# board.net
KiCad netlist of a schematic drawn in EAGLE
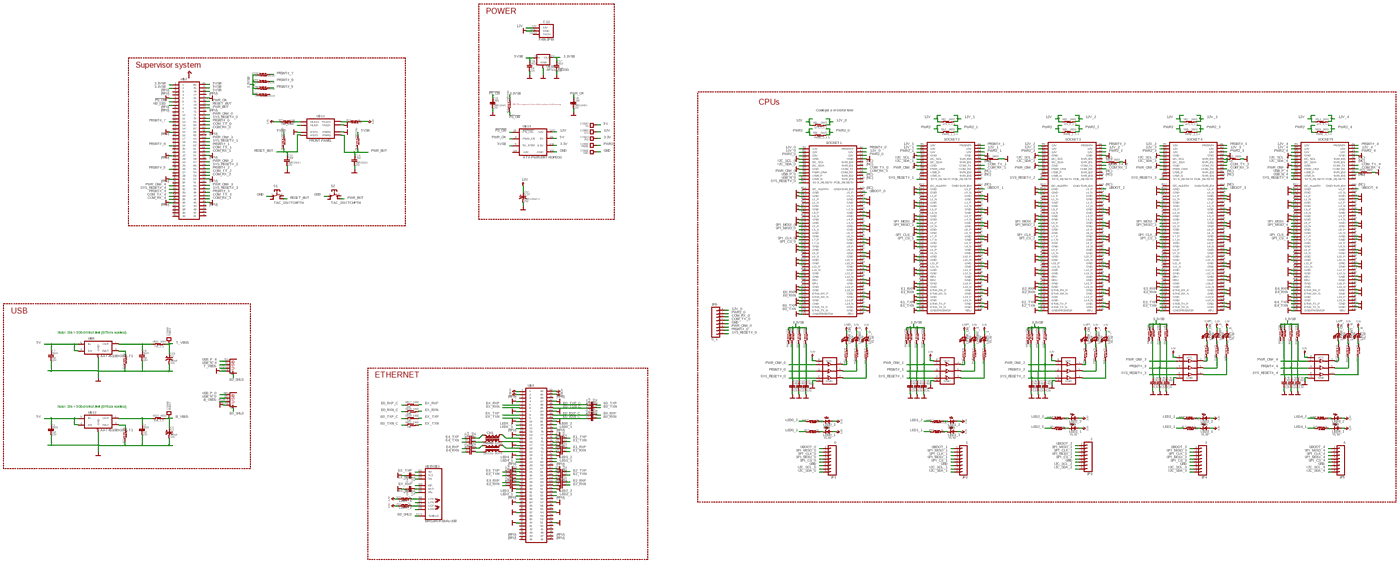
[diagram p0: schematic, sheet 1, overview]
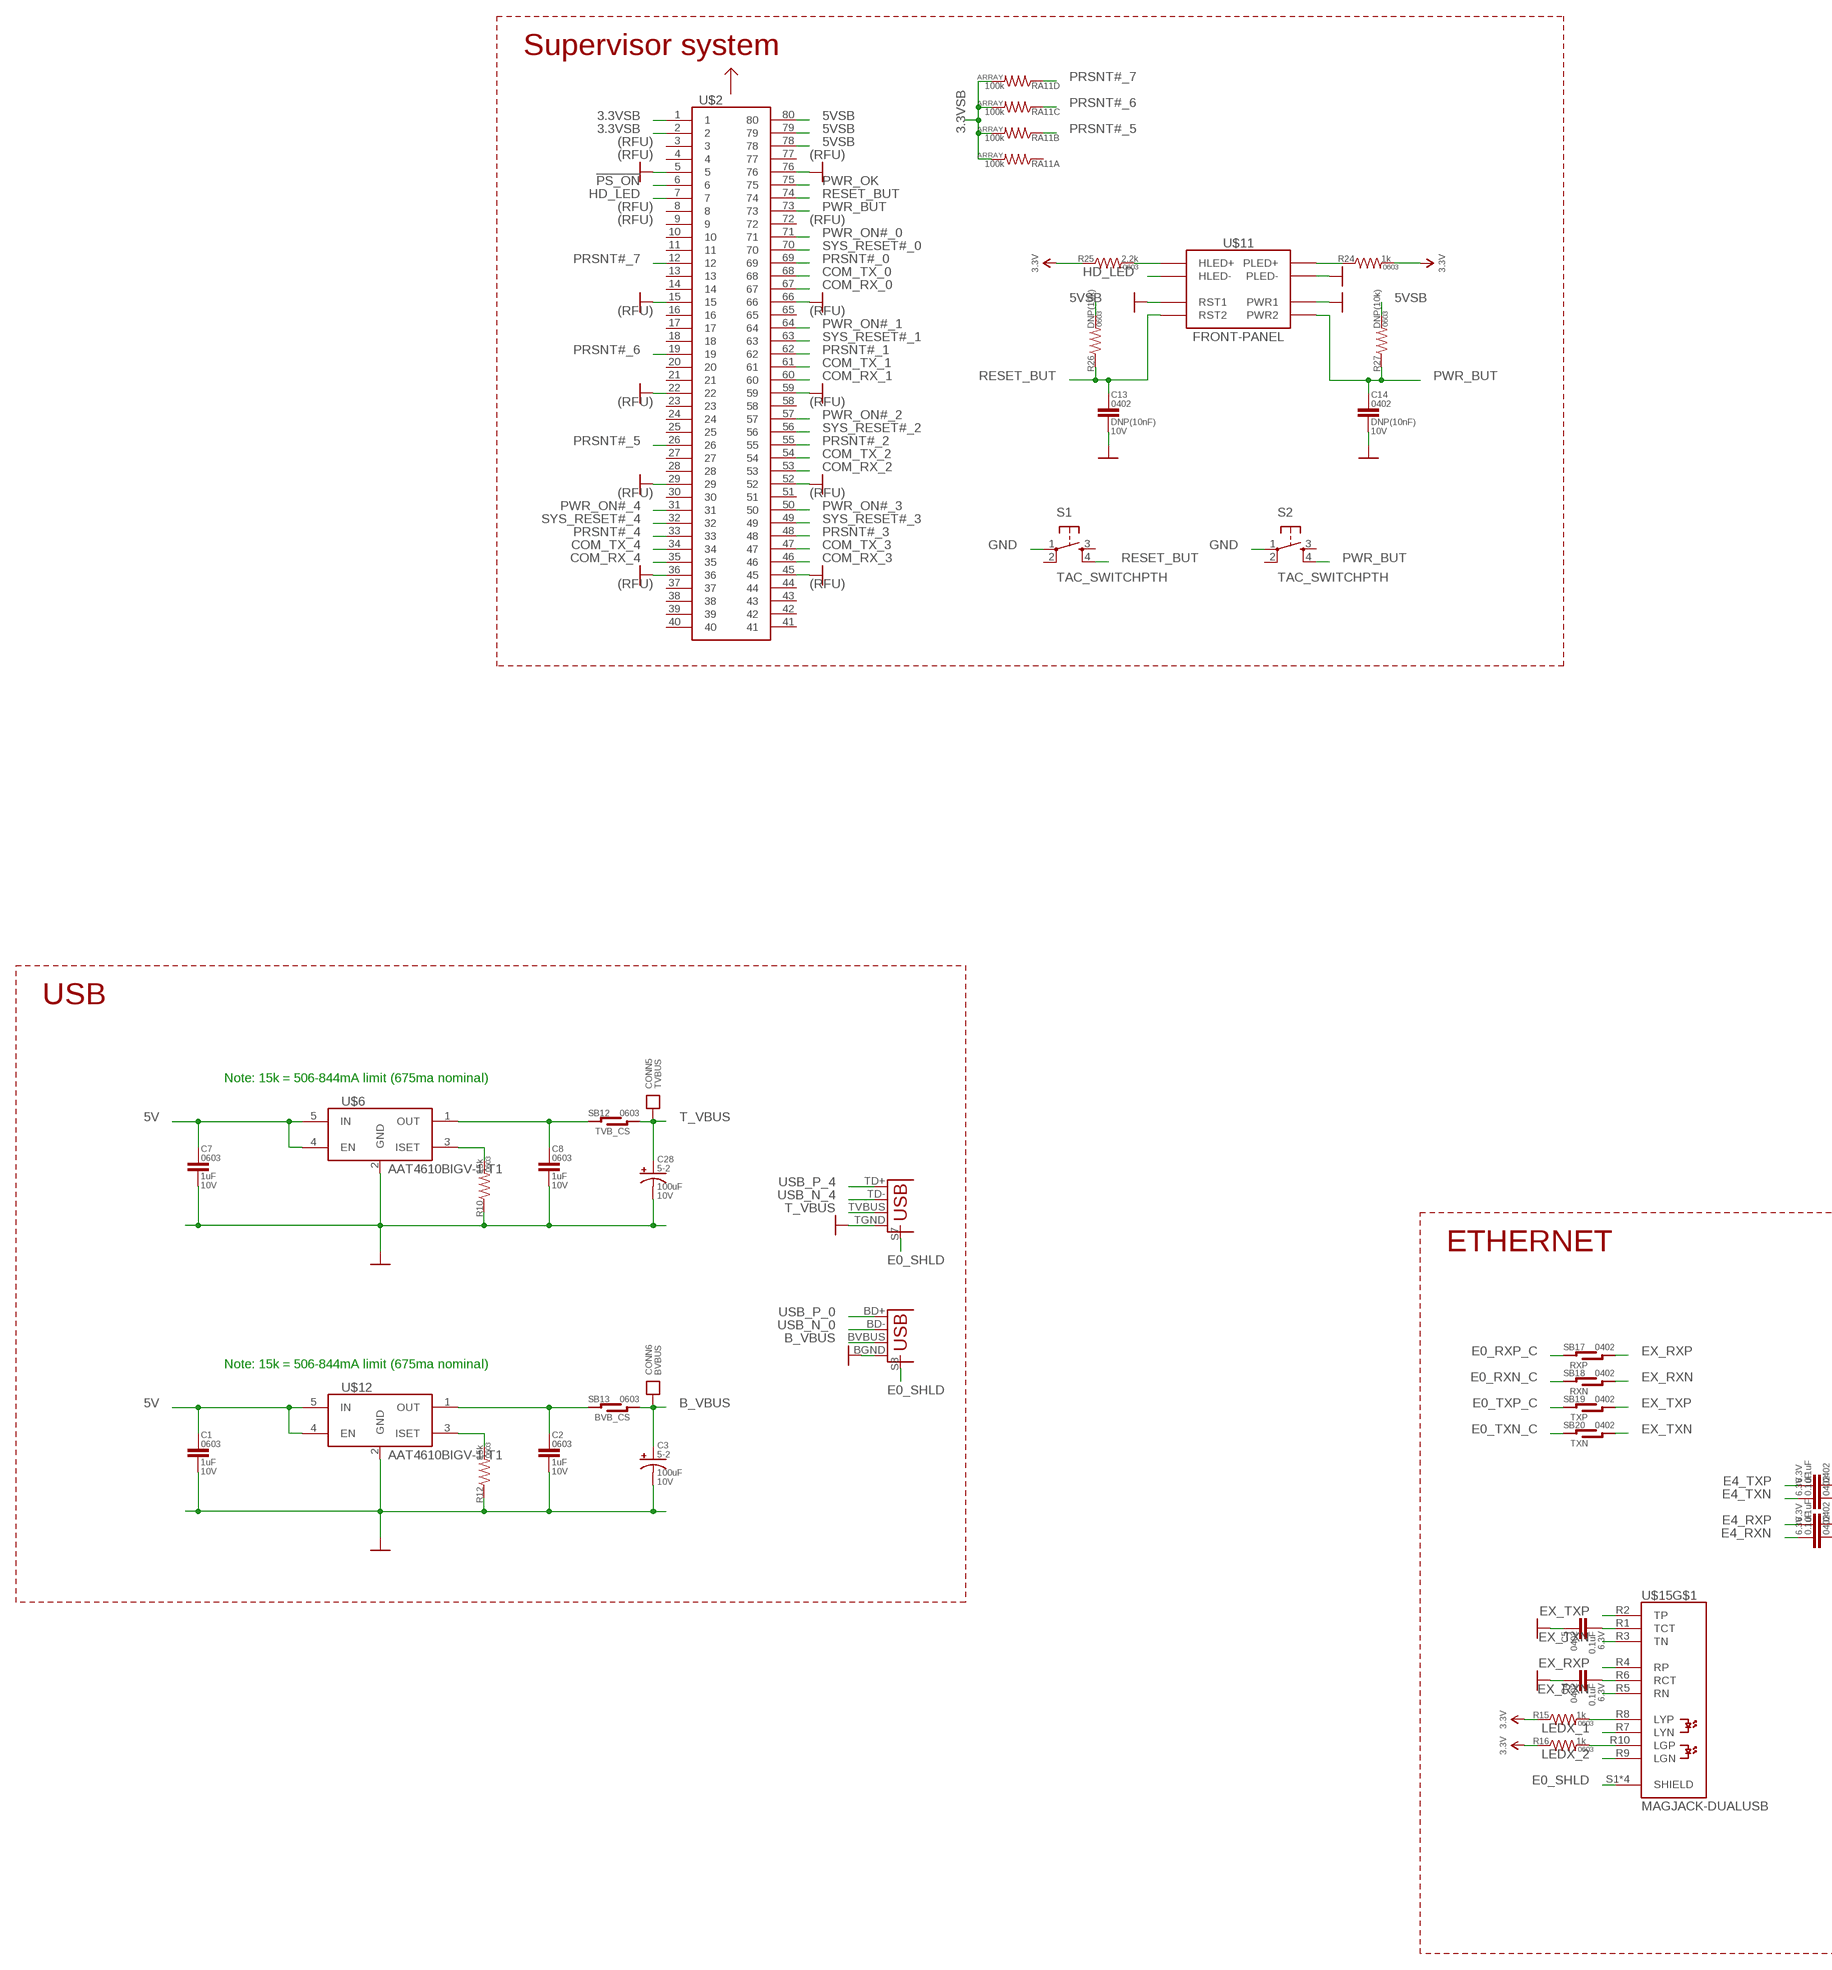
[diagram p1: schematic, sheet 1, part 1 of 4]
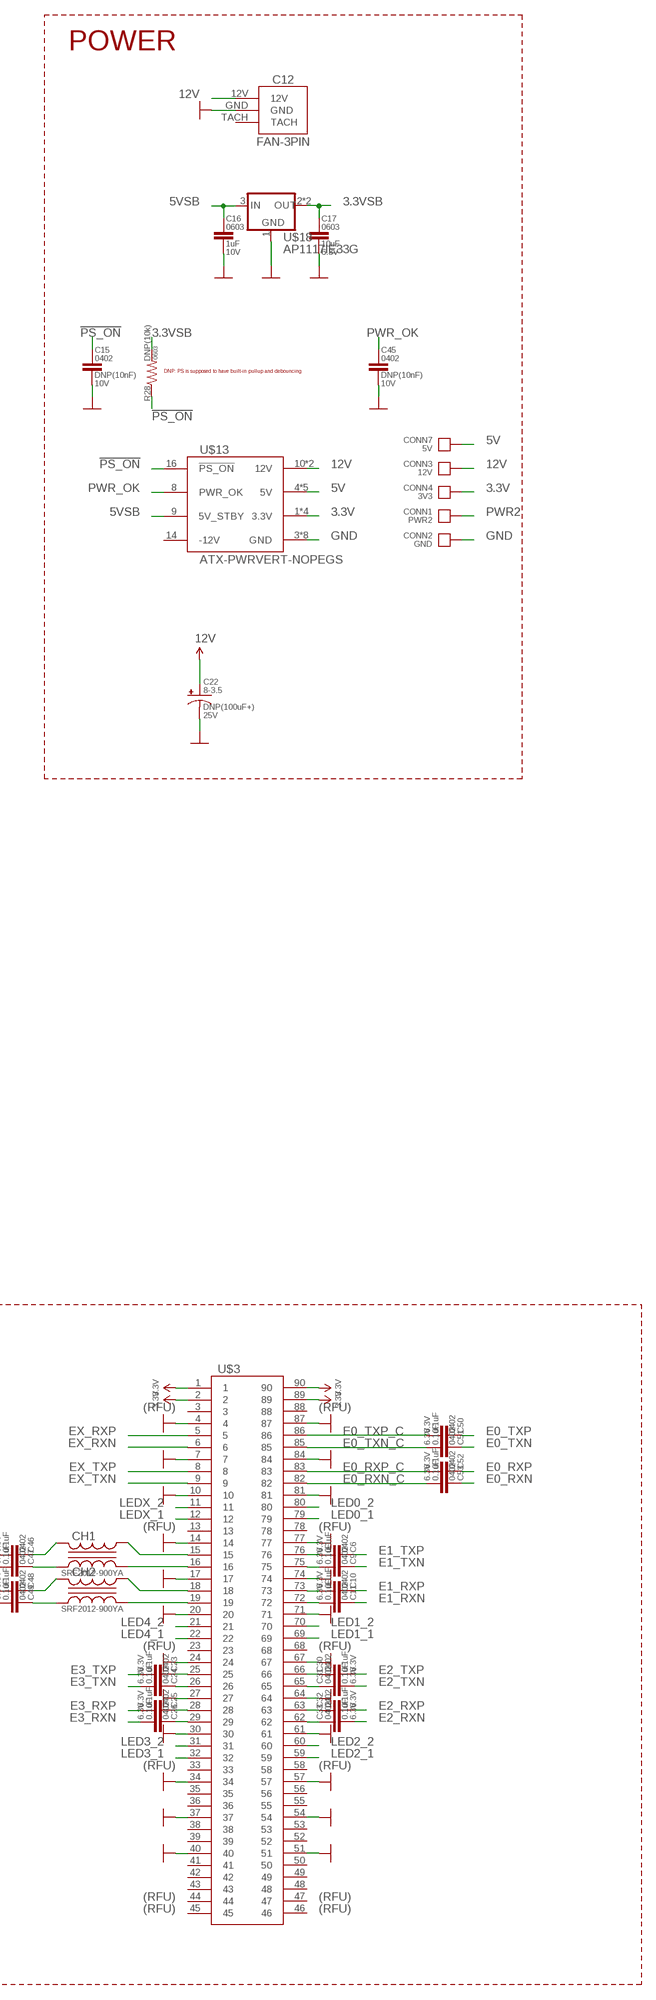
[diagram p2: schematic, sheet 1, part 2 of 4]
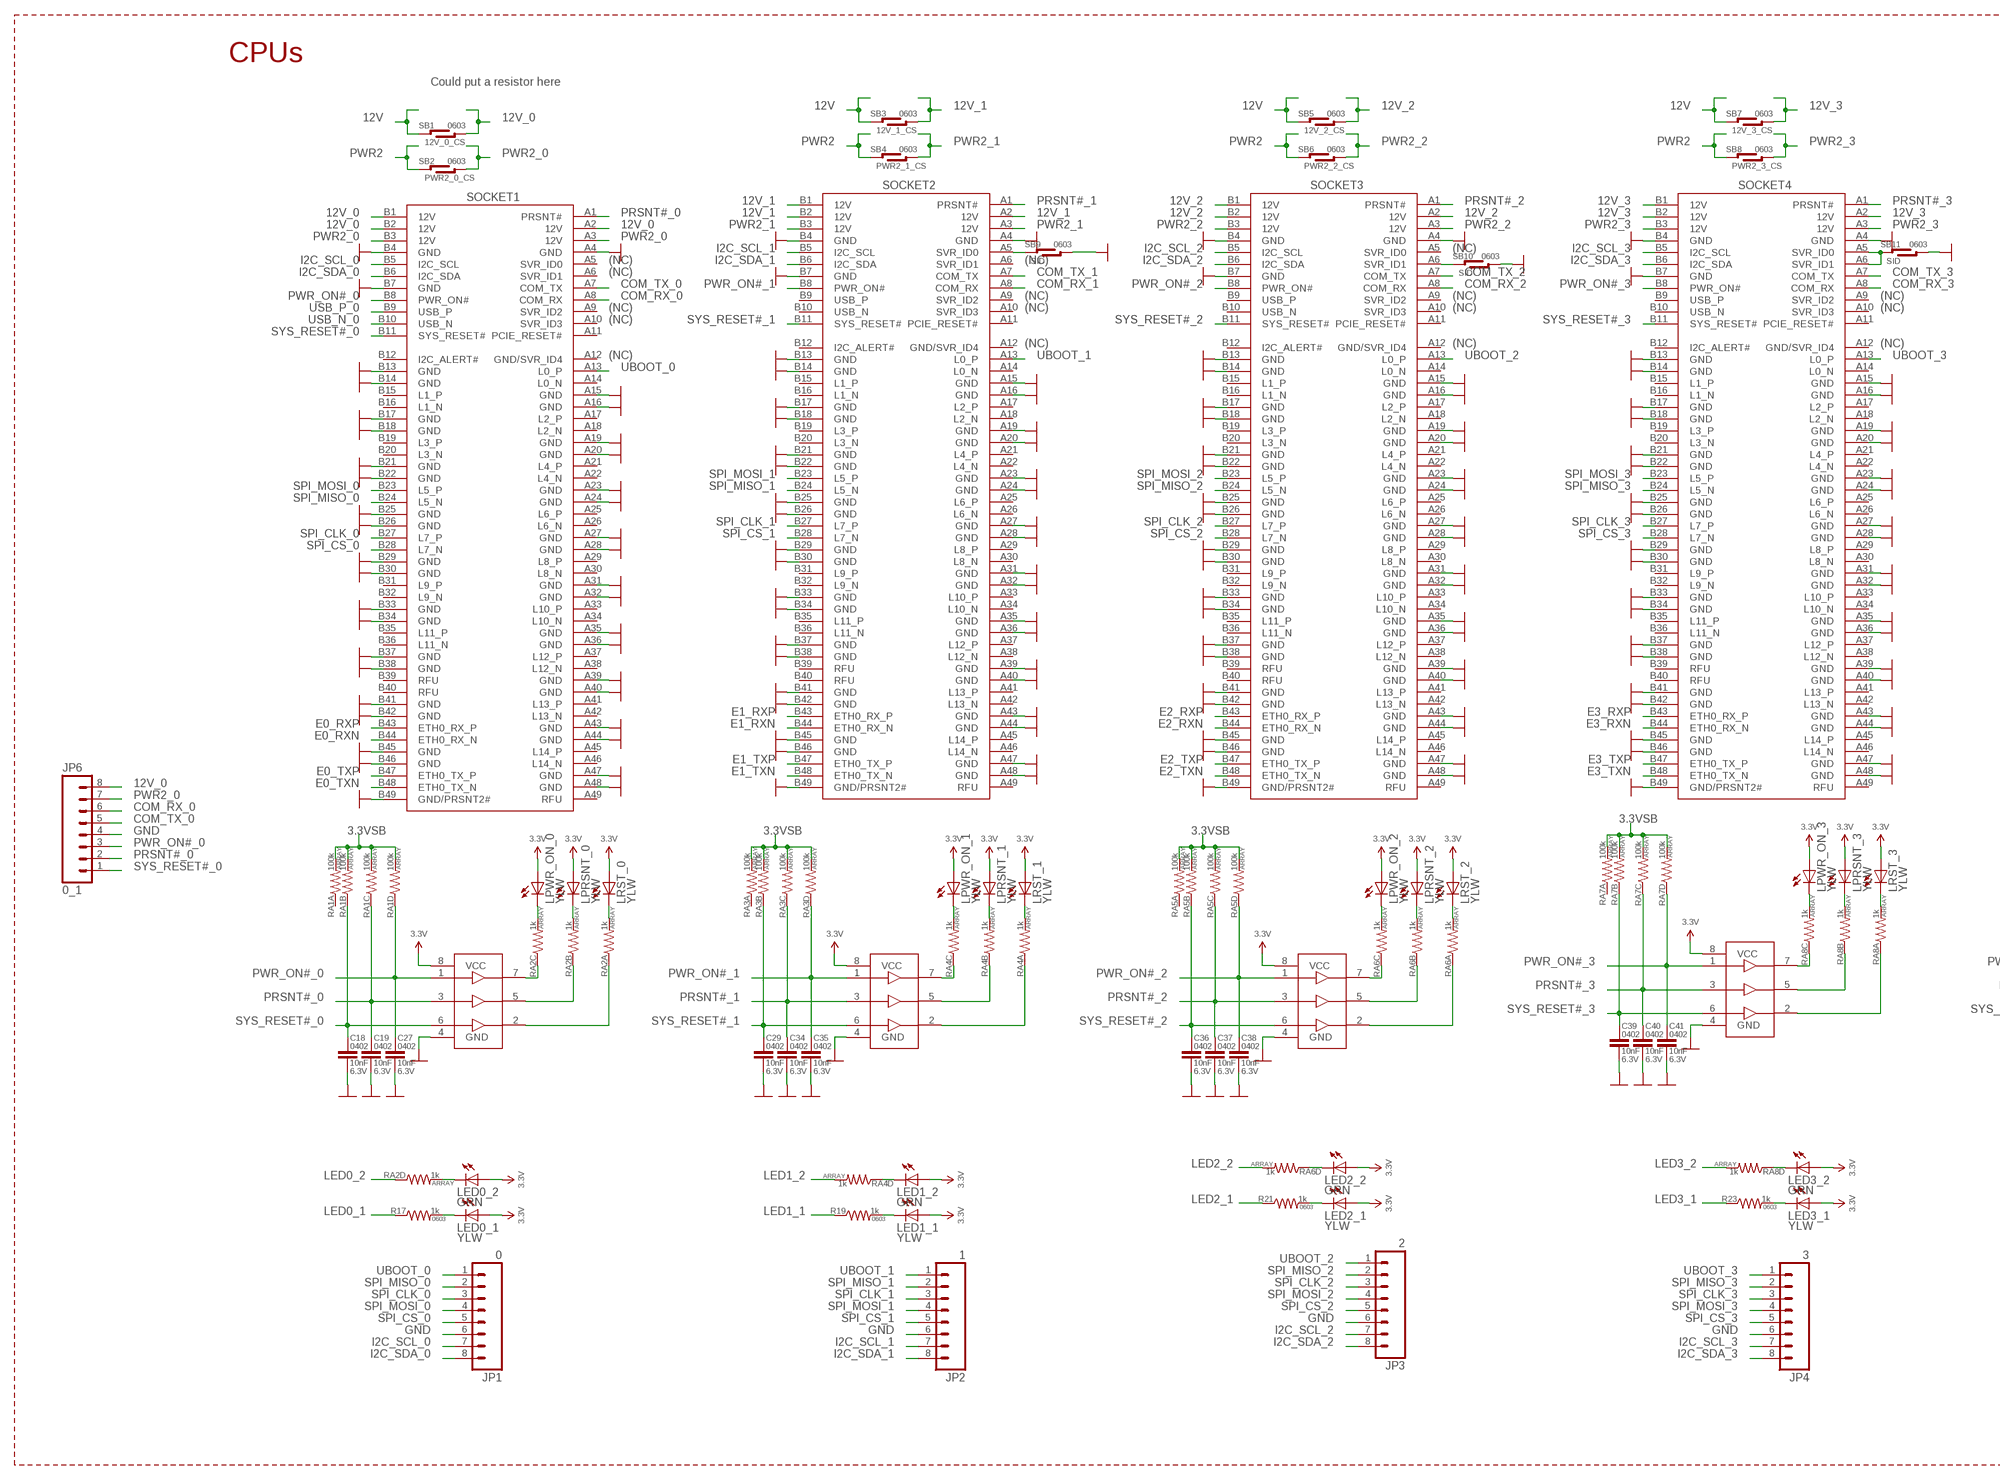
[diagram p3: schematic, sheet 1, part 3 of 4]
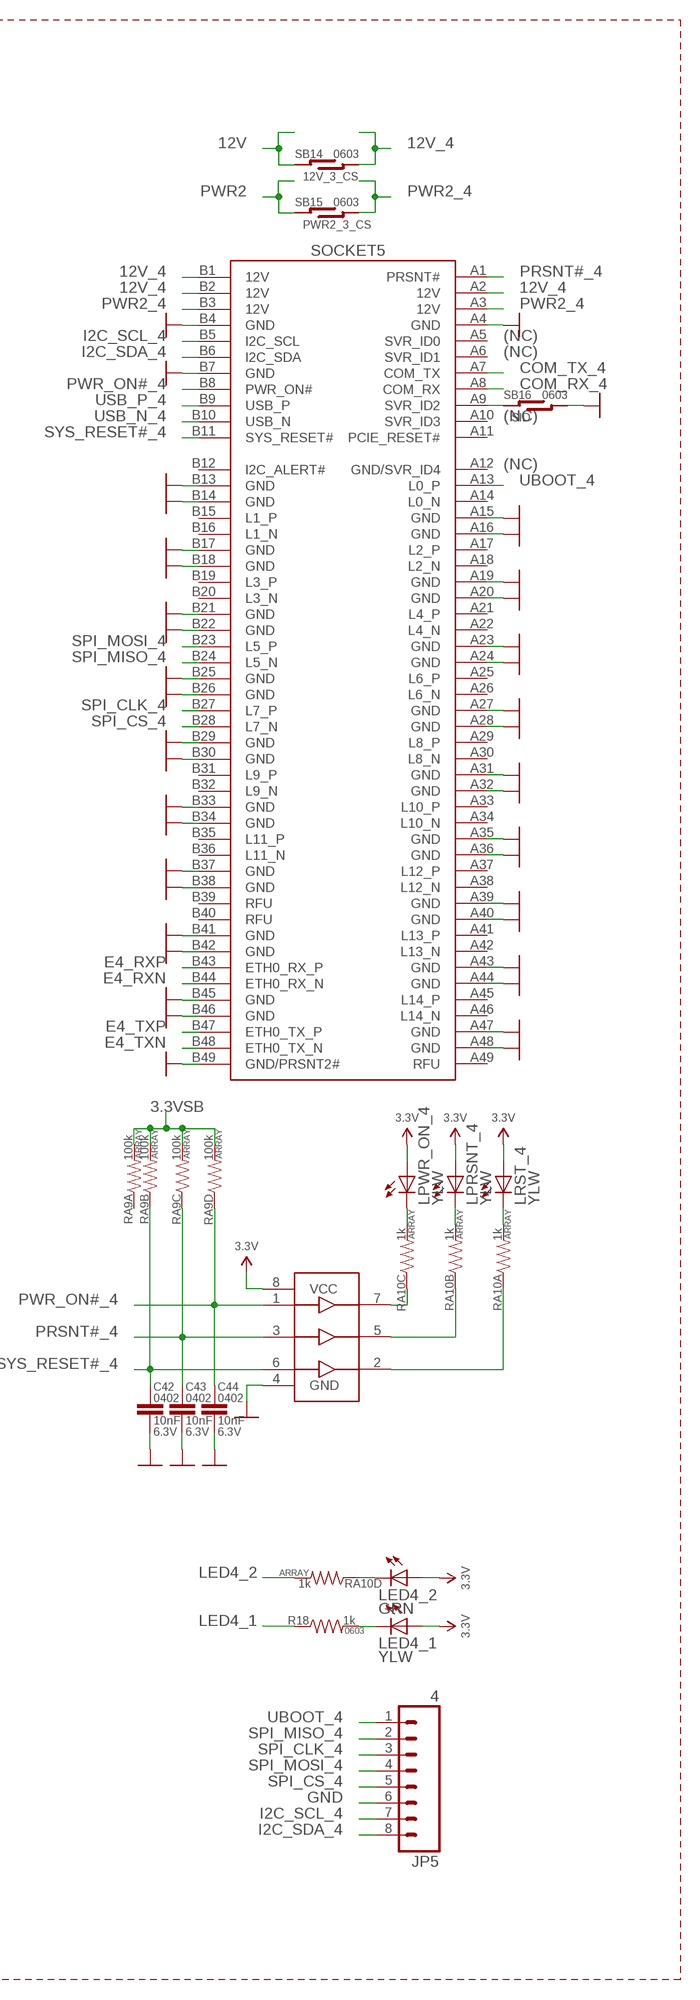
[diagram p4: schematic, sheet 1, part 4 of 4]

(export (version "E")
  (design (tool "Eeschema 10.0.6"))
  (components
    (comp (ref "C1")
      (value "1uF")
      (footprint "eagle-import:0603-CAP")
      (fields (field (name "VOLTAGE") "6.3V") (field (name "VOLTAGE_1") "10V"))
      (libsource (lib "eagle-import") (part "CAP0603"))
    )
    (comp (ref "C2")
      (value "1uF")
      (footprint "eagle-import:0603-CAP")
      (fields (field (name "VOLTAGE") "6.3V") (field (name "VOLTAGE_1") "10V"))
      (libsource (lib "eagle-import") (part "CAP0603"))
    )
    (comp (ref "C3")
      (value "100uF")
      (footprint "eagle-import:CAP-5-2")
      (fields (field (name "VOLTAGE") "6.3V") (field (name "VOLTAGE_1") "10V"))
      (libsource (lib "eagle-import") (part "CAP_POLPTH-5-2"))
    )
    (comp (ref "C4")
      (value "0.1uF")
      (footprint "eagle-import:0402-CAP")
      (fields (field (name "VOLTAGE") "6.3V"))
      (libsource (lib "eagle-import") (part "CAP0402-CAP"))
    )
    (comp (ref "C5")
      (value "0.1uF")
      (footprint "eagle-import:0402-CAP")
      (fields (field (name "VOLTAGE") "6.3V"))
      (libsource (lib "eagle-import") (part "CAP0402-CAP"))
    )
    (comp (ref "C6")
      (value "0.1uF")
      (footprint "eagle-import:0402-CAP")
      (fields (field (name "VOLTAGE") "6.3V"))
      (libsource (lib "eagle-import") (part "CAP0402-CAP"))
    )
    (comp (ref "C7")
      (value "1uF")
      (footprint "eagle-import:0603-CAP")
      (fields (field (name "VOLTAGE") "6.3V") (field (name "VOLTAGE_1") "10V"))
      (libsource (lib "eagle-import") (part "CAP0603"))
    )
    (comp (ref "C8")
      (value "1uF")
      (footprint "eagle-import:0603-CAP")
      (fields (field (name "VOLTAGE") "6.3V") (field (name "VOLTAGE_1") "10V"))
      (libsource (lib "eagle-import") (part "CAP0603"))
    )
    (comp (ref "C9")
      (value "0.1uF")
      (footprint "eagle-import:0402-CAP")
      (fields (field (name "VOLTAGE") "6.3V"))
      (libsource (lib "eagle-import") (part "CAP0402-CAP"))
    )
    (comp (ref "C10")
      (value "0.1uF")
      (footprint "eagle-import:0402-CAP")
      (fields (field (name "VOLTAGE") "6.3V"))
      (libsource (lib "eagle-import") (part "CAP0402-CAP"))
    )
    (comp (ref "C11")
      (value "0.1uF")
      (footprint "eagle-import:0402-CAP")
      (fields (field (name "VOLTAGE") "6.3V"))
      (libsource (lib "eagle-import") (part "CAP0402-CAP"))
    )
    (comp (ref "C12")
      (value "FAN-3PIN")
      (footprint "eagle-import:FAN-3PIN")
      (libsource (lib "eagle-import") (part "FAN-3PIN"))
    )
    (comp (ref "C13")
      (value "DNP(10nF)")
      (footprint "eagle-import:0402-CAP")
      (fields (field (name "VOLTAGE") "6.3V") (field (name "VOLTAGE_1") "10V"))
      (libsource (lib "eagle-import") (part "CAP0402-CAP"))
    )
    (comp (ref "C14")
      (value "DNP(10nF)")
      (footprint "eagle-import:0402-CAP")
      (fields (field (name "VOLTAGE") "6.3V") (field (name "VOLTAGE_1") "10V"))
      (libsource (lib "eagle-import") (part "CAP0402-CAP"))
    )
    (comp (ref "C15")
      (value "DNP(10nF)")
      (footprint "eagle-import:0402-CAP")
      (fields (field (name "VOLTAGE") "6.3V") (field (name "VOLTAGE_1") "10V"))
      (libsource (lib "eagle-import") (part "CAP0402-CAP"))
    )
    (comp (ref "C16")
      (value "1uF")
      (footprint "eagle-import:0603-CAP")
      (fields (field (name "VOLTAGE") "6.3V") (field (name "VOLTAGE_1") "10V"))
      (libsource (lib "eagle-import") (part "CAP0603"))
    )
    (comp (ref "C17")
      (value "10uF")
      (footprint "eagle-import:0603-CAP")
      (fields (field (name "VOLTAGE") "6.3V"))
      (libsource (lib "eagle-import") (part "CAP0603"))
    )
    (comp (ref "C18")
      (value "10nF")
      (footprint "eagle-import:0402-CAP")
      (fields (field (name "VOLTAGE") "6.3V"))
      (libsource (lib "eagle-import") (part "CAP0402-CAP"))
    )
    (comp (ref "C19")
      (value "10nF")
      (footprint "eagle-import:0402-CAP")
      (fields (field (name "VOLTAGE") "6.3V"))
      (libsource (lib "eagle-import") (part "CAP0402-CAP"))
    )
    (comp (ref "C22")
      (value "DNP(100uF+)")
      (footprint "eagle-import:CAP-8-3.5")
      (fields (field (name "VOLTAGE") "6.3V") (field (name "VOLTAGE_1") "25V"))
      (libsource (lib "eagle-import") (part "CAP_POLPTH-8-3.5"))
    )
    (comp (ref "C23")
      (value "0.1uF")
      (footprint "eagle-import:0402-CAP")
      (fields (field (name "VOLTAGE") "6.3V"))
      (libsource (lib "eagle-import") (part "CAP0402-CAP"))
    )
    (comp (ref "C24")
      (value "0.1uF")
      (footprint "eagle-import:0402-CAP")
      (fields (field (name "VOLTAGE") "6.3V"))
      (libsource (lib "eagle-import") (part "CAP0402-CAP"))
    )
    (comp (ref "C25")
      (value "0.1uF")
      (footprint "eagle-import:0402-CAP")
      (fields (field (name "VOLTAGE") "6.3V"))
      (libsource (lib "eagle-import") (part "CAP0402-CAP"))
    )
    (comp (ref "C26")
      (value "0.1uF")
      (footprint "eagle-import:0402-CAP")
      (fields (field (name "VOLTAGE") "6.3V"))
      (libsource (lib "eagle-import") (part "CAP0402-CAP"))
    )
    (comp (ref "C27")
      (value "10nF")
      (footprint "eagle-import:0402-CAP")
      (fields (field (name "VOLTAGE") "6.3V"))
      (libsource (lib "eagle-import") (part "CAP0402-CAP"))
    )
    (comp (ref "C28")
      (value "100uF")
      (footprint "eagle-import:CAP-5-2")
      (fields (field (name "VOLTAGE") "6.3V") (field (name "VOLTAGE_1") "10V"))
      (libsource (lib "eagle-import") (part "CAP_POLPTH-5-2"))
    )
    (comp (ref "C29")
      (value "10nF")
      (footprint "eagle-import:0402-CAP")
      (fields (field (name "VOLTAGE") "6.3V"))
      (libsource (lib "eagle-import") (part "CAP0402-CAP"))
    )
    (comp (ref "C30")
      (value "0.1uF")
      (footprint "eagle-import:0402-CAP")
      (fields (field (name "VOLTAGE") "6.3V"))
      (libsource (lib "eagle-import") (part "CAP0402-CAP"))
    )
    (comp (ref "C31")
      (value "0.1uF")
      (footprint "eagle-import:0402-CAP")
      (fields (field (name "VOLTAGE") "6.3V"))
      (libsource (lib "eagle-import") (part "CAP0402-CAP"))
    )
    (comp (ref "C32")
      (value "0.1uF")
      (footprint "eagle-import:0402-CAP")
      (fields (field (name "VOLTAGE") "6.3V"))
      (libsource (lib "eagle-import") (part "CAP0402-CAP"))
    )
    (comp (ref "C33")
      (value "0.1uF")
      (footprint "eagle-import:0402-CAP")
      (fields (field (name "VOLTAGE") "6.3V"))
      (libsource (lib "eagle-import") (part "CAP0402-CAP"))
    )
    (comp (ref "C34")
      (value "10nF")
      (footprint "eagle-import:0402-CAP")
      (fields (field (name "VOLTAGE") "6.3V"))
      (libsource (lib "eagle-import") (part "CAP0402-CAP"))
    )
    (comp (ref "C35")
      (value "10nF")
      (footprint "eagle-import:0402-CAP")
      (fields (field (name "VOLTAGE") "6.3V"))
      (libsource (lib "eagle-import") (part "CAP0402-CAP"))
    )
    (comp (ref "C36")
      (value "10nF")
      (footprint "eagle-import:0402-CAP")
      (fields (field (name "VOLTAGE") "6.3V"))
      (libsource (lib "eagle-import") (part "CAP0402-CAP"))
    )
    (comp (ref "C37")
      (value "10nF")
      (footprint "eagle-import:0402-CAP")
      (fields (field (name "VOLTAGE") "6.3V"))
      (libsource (lib "eagle-import") (part "CAP0402-CAP"))
    )
    (comp (ref "C38")
      (value "10nF")
      (footprint "eagle-import:0402-CAP")
      (fields (field (name "VOLTAGE") "6.3V"))
      (libsource (lib "eagle-import") (part "CAP0402-CAP"))
    )
    (comp (ref "C39")
      (value "10nF")
      (footprint "eagle-import:0402-CAP")
      (fields (field (name "VOLTAGE") "6.3V"))
      (libsource (lib "eagle-import") (part "CAP0402-CAP"))
    )
    (comp (ref "C40")
      (value "10nF")
      (footprint "eagle-import:0402-CAP")
      (fields (field (name "VOLTAGE") "6.3V"))
      (libsource (lib "eagle-import") (part "CAP0402-CAP"))
    )
    (comp (ref "C41")
      (value "10nF")
      (footprint "eagle-import:0402-CAP")
      (fields (field (name "VOLTAGE") "6.3V"))
      (libsource (lib "eagle-import") (part "CAP0402-CAP"))
    )
    (comp (ref "C42")
      (value "10nF")
      (footprint "eagle-import:0402-CAP")
      (fields (field (name "VOLTAGE") "6.3V"))
      (libsource (lib "eagle-import") (part "CAP0402-CAP"))
    )
    (comp (ref "C43")
      (value "10nF")
      (footprint "eagle-import:0402-CAP")
      (fields (field (name "VOLTAGE") "6.3V"))
      (libsource (lib "eagle-import") (part "CAP0402-CAP"))
    )
    (comp (ref "C44")
      (value "10nF")
      (footprint "eagle-import:0402-CAP")
      (fields (field (name "VOLTAGE") "6.3V"))
      (libsource (lib "eagle-import") (part "CAP0402-CAP"))
    )
    (comp (ref "C45")
      (value "DNP(10nF)")
      (footprint "eagle-import:0402-CAP")
      (fields (field (name "VOLTAGE") "6.3V") (field (name "VOLTAGE_1") "10V"))
      (libsource (lib "eagle-import") (part "CAP0402-CAP"))
    )
    (comp (ref "C46")
      (value "0.1uF")
      (footprint "eagle-import:0402-CAP")
      (fields (field (name "VOLTAGE") "6.3V"))
      (libsource (lib "eagle-import") (part "CAP0402-CAP"))
    )
    (comp (ref "C47")
      (value "0.1uF")
      (footprint "eagle-import:0402-CAP")
      (fields (field (name "VOLTAGE") "6.3V"))
      (libsource (lib "eagle-import") (part "CAP0402-CAP"))
    )
    (comp (ref "C48")
      (value "0.1uF")
      (footprint "eagle-import:0402-CAP")
      (fields (field (name "VOLTAGE") "6.3V"))
      (libsource (lib "eagle-import") (part "CAP0402-CAP"))
    )
    (comp (ref "C49")
      (value "0.1uF")
      (footprint "eagle-import:0402-CAP")
      (fields (field (name "VOLTAGE") "6.3V"))
      (libsource (lib "eagle-import") (part "CAP0402-CAP"))
    )
    (comp (ref "C50")
      (value "0.1uF")
      (footprint "eagle-import:0402-CAP")
      (fields (field (name "VOLTAGE") "6.3V"))
      (libsource (lib "eagle-import") (part "CAP0402-CAP"))
    )
    (comp (ref "C51")
      (value "0.1uF")
      (footprint "eagle-import:0402-CAP")
      (fields (field (name "VOLTAGE") "6.3V"))
      (libsource (lib "eagle-import") (part "CAP0402-CAP"))
    )
    (comp (ref "C52")
      (value "0.1uF")
      (footprint "eagle-import:0402-CAP")
      (fields (field (name "VOLTAGE") "6.3V"))
      (libsource (lib "eagle-import") (part "CAP0402-CAP"))
    )
    (comp (ref "C53")
      (value "0.1uF")
      (footprint "eagle-import:0402-CAP")
      (fields (field (name "VOLTAGE") "6.3V"))
      (libsource (lib "eagle-import") (part "CAP0402-CAP"))
    )
    (comp (ref "CH1")
      (value "SRF2012-900YA")
      (footprint "eagle-import:SRF2012A")
      (libsource (lib "eagle-import") (part "COMMON_MODE_CHOKE"))
    )
    (comp (ref "CH2")
      (value "SRF2012-900YA")
      (footprint "eagle-import:SRF2012A")
      (libsource (lib "eagle-import") (part "COMMON_MODE_CHOKE"))
    )
    (comp (ref "CONN1")
      (value "PWR2")
      (footprint "eagle-import:HOLE_18AWG")
      (libsource (lib "eagle-import") (part "CONNECTOR18AWG"))
    )
    (comp (ref "CONN2")
      (value "GND")
      (footprint "eagle-import:HOLE_18AWG")
      (libsource (lib "eagle-import") (part "CONNECTOR18AWG"))
    )
    (comp (ref "CONN3")
      (value "12V")
      (footprint "eagle-import:HOLE_18AWG")
      (libsource (lib "eagle-import") (part "CONNECTOR18AWG"))
    )
    (comp (ref "CONN4")
      (value "3V3")
      (footprint "eagle-import:HOLE_18AWG")
      (libsource (lib "eagle-import") (part "CONNECTOR18AWG"))
    )
    (comp (ref "CONN5")
      (value "TVBUS")
      (footprint "eagle-import:HOLE_22AWG")
      (libsource (lib "eagle-import") (part "CONNECTOR22AWG"))
    )
    (comp (ref "CONN6")
      (value "BVBUS")
      (footprint "eagle-import:HOLE_22AWG")
      (libsource (lib "eagle-import") (part "CONNECTOR22AWG"))
    )
    (comp (ref "CONN7")
      (value "5V")
      (footprint "eagle-import:HOLE_18AWG")
      (libsource (lib "eagle-import") (part "CONNECTOR18AWG"))
    )
    (comp (ref "IC1")
      (value "74X3G34")
      (footprint "eagle-import:TSSOP8")
      (libsource (lib "eagle-import") (part "74X3G34"))
    )
    (comp (ref "IC2")
      (value "74X3G34")
      (footprint "eagle-import:TSSOP8")
      (libsource (lib "eagle-import") (part "74X3G34"))
    )
    (comp (ref "IC3")
      (value "74X3G34")
      (footprint "eagle-import:TSSOP8")
      (libsource (lib "eagle-import") (part "74X3G34"))
    )
    (comp (ref "IC4")
      (value "74X3G34")
      (footprint "eagle-import:TSSOP8")
      (libsource (lib "eagle-import") (part "74X3G34"))
    )
    (comp (ref "IC5")
      (value "74X3G34")
      (footprint "eagle-import:TSSOP8")
      (libsource (lib "eagle-import") (part "74X3G34"))
    )
    (comp (ref "JP1")
      (value "0")
      (footprint "eagle-import:1X08")
      (libsource (lib "eagle-import") (part "M081X08"))
    )
    (comp (ref "JP2")
      (value "1")
      (footprint "eagle-import:1X08")
      (libsource (lib "eagle-import") (part "M081X08"))
    )
    (comp (ref "JP3")
      (value "2")
      (footprint "eagle-import:1X08")
      (libsource (lib "eagle-import") (part "M081X08"))
    )
    (comp (ref "JP4")
      (value "3")
      (footprint "eagle-import:1X08")
      (libsource (lib "eagle-import") (part "M081X08"))
    )
    (comp (ref "JP5")
      (value "4")
      (footprint "eagle-import:1X08")
      (libsource (lib "eagle-import") (part "M081X08"))
    )
    (comp (ref "JP6")
      (value "0_1")
      (footprint "eagle-import:1X08")
      (libsource (lib "eagle-import") (part "M081X08"))
    )
    (comp (ref "LED0_1")
      (value "YLW")
      (footprint "eagle-import:0603_LED")
      (libsource (lib "eagle-import") (part "LED0603"))
    )
    (comp (ref "LED0_2")
      (value "GRN")
      (footprint "eagle-import:0603_LED")
      (libsource (lib "eagle-import") (part "LED0603"))
    )
    (comp (ref "LED1_1")
      (value "YLW")
      (footprint "eagle-import:0603_LED")
      (libsource (lib "eagle-import") (part "LED0603"))
    )
    (comp (ref "LED1_2")
      (value "GRN")
      (footprint "eagle-import:0603_LED")
      (libsource (lib "eagle-import") (part "LED0603"))
    )
    (comp (ref "LED2_1")
      (value "YLW")
      (footprint "eagle-import:0603_LED")
      (libsource (lib "eagle-import") (part "LED0603"))
    )
    (comp (ref "LED2_2")
      (value "GRN")
      (footprint "eagle-import:0603_LED")
      (libsource (lib "eagle-import") (part "LED0603"))
    )
    (comp (ref "LED3_1")
      (value "YLW")
      (footprint "eagle-import:0603_LED")
      (libsource (lib "eagle-import") (part "LED0603"))
    )
    (comp (ref "LED3_2")
      (value "GRN")
      (footprint "eagle-import:0603_LED")
      (libsource (lib "eagle-import") (part "LED0603"))
    )
    (comp (ref "LED4_1")
      (value "YLW")
      (footprint "eagle-import:0603_LED")
      (libsource (lib "eagle-import") (part "LED0603"))
    )
    (comp (ref "LED4_2")
      (value "GRN")
      (footprint "eagle-import:0603_LED")
      (libsource (lib "eagle-import") (part "LED0603"))
    )
    (comp (ref "LPRSNT_0")
      (value "YLW")
      (footprint "eagle-import:0603_LED")
      (libsource (lib "eagle-import") (part "LED0603"))
    )
    (comp (ref "LPRSNT_1")
      (value "YLW")
      (footprint "eagle-import:0603_LED")
      (libsource (lib "eagle-import") (part "LED0603"))
    )
    (comp (ref "LPRSNT_2")
      (value "YLW")
      (footprint "eagle-import:0603_LED")
      (libsource (lib "eagle-import") (part "LED0603"))
    )
    (comp (ref "LPRSNT_3")
      (value "YLW")
      (footprint "eagle-import:0603_LED")
      (libsource (lib "eagle-import") (part "LED0603"))
    )
    (comp (ref "LPRSNT_4")
      (value "YLW")
      (footprint "eagle-import:0603_LED")
      (libsource (lib "eagle-import") (part "LED0603"))
    )
    (comp (ref "LPWR_ON_0")
      (value "YLW")
      (footprint "eagle-import:0603_LED")
      (libsource (lib "eagle-import") (part "LED0603"))
    )
    (comp (ref "LPWR_ON_1")
      (value "YLW")
      (footprint "eagle-import:0603_LED")
      (libsource (lib "eagle-import") (part "LED0603"))
    )
    (comp (ref "LPWR_ON_2")
      (value "YLW")
      (footprint "eagle-import:0603_LED")
      (libsource (lib "eagle-import") (part "LED0603"))
    )
    (comp (ref "LPWR_ON_3")
      (value "YLW")
      (footprint "eagle-import:0603_LED")
      (libsource (lib "eagle-import") (part "LED0603"))
    )
    (comp (ref "LPWR_ON_4")
      (value "YLW")
      (footprint "eagle-import:0603_LED")
      (libsource (lib "eagle-import") (part "LED0603"))
    )
    (comp (ref "LRST_0")
      (value "YLW")
      (footprint "eagle-import:0603_LED")
      (libsource (lib "eagle-import") (part "LED0603"))
    )
    (comp (ref "LRST_1")
      (value "YLW")
      (footprint "eagle-import:0603_LED")
      (libsource (lib "eagle-import") (part "LED0603"))
    )
    (comp (ref "LRST_2")
      (value "YLW")
      (footprint "eagle-import:0603_LED")
      (libsource (lib "eagle-import") (part "LED0603"))
    )
    (comp (ref "LRST_3")
      (value "YLW")
      (footprint "eagle-import:0603_LED")
      (libsource (lib "eagle-import") (part "LED0603"))
    )
    (comp (ref "LRST_4")
      (value "YLW")
      (footprint "eagle-import:0603_LED")
      (libsource (lib "eagle-import") (part "LED0603"))
    )
    (comp (ref "R10")
      (value "15k")
      (footprint "eagle-import:0603-RES")
      (libsource (lib "eagle-import") (part "RESISTOR0603"))
    )
    (comp (ref "R12")
      (value "15k")
      (footprint "eagle-import:0603-RES")
      (libsource (lib "eagle-import") (part "RESISTOR0603"))
    )
    (comp (ref "R15")
      (value "1k")
      (footprint "eagle-import:0603-RES")
      (libsource (lib "eagle-import") (part "RESISTOR0603"))
    )
    (comp (ref "R16")
      (value "1k")
      (footprint "eagle-import:0603-RES")
      (libsource (lib "eagle-import") (part "RESISTOR0603"))
    )
    (comp (ref "R17")
      (value "1k")
      (footprint "eagle-import:0603-RES")
      (libsource (lib "eagle-import") (part "RESISTOR0603"))
    )
    (comp (ref "R18")
      (value "1k")
      (footprint "eagle-import:0603-RES")
      (libsource (lib "eagle-import") (part "RESISTOR0603"))
    )
    (comp (ref "R19")
      (value "1k")
      (footprint "eagle-import:0603-RES")
      (libsource (lib "eagle-import") (part "RESISTOR0603"))
    )
    (comp (ref "R21")
      (value "1k")
      (footprint "eagle-import:0603-RES")
      (libsource (lib "eagle-import") (part "RESISTOR0603"))
    )
    (comp (ref "R23")
      (value "1k")
      (footprint "eagle-import:0603-RES")
      (libsource (lib "eagle-import") (part "RESISTOR0603"))
    )
    (comp (ref "R24")
      (value "1k")
      (footprint "eagle-import:0603-RES")
      (libsource (lib "eagle-import") (part "RESISTOR0603"))
    )
    (comp (ref "R25")
      (value "2.2k")
      (footprint "eagle-import:0603-RES")
      (libsource (lib "eagle-import") (part "RESISTOR0603"))
    )
    (comp (ref "R26")
      (value "DNP(10k)")
      (footprint "eagle-import:0603-RES")
      (libsource (lib "eagle-import") (part "RESISTOR0603"))
    )
    (comp (ref "R27")
      (value "DNP(10k)")
      (footprint "eagle-import:0603-RES")
      (libsource (lib "eagle-import") (part "RESISTOR0603"))
    )
    (comp (ref "R28")
      (value "DNP(10k)")
      (footprint "eagle-import:0603-RES")
      (libsource (lib "eagle-import") (part "RESISTOR0603"))
    )
    (comp (ref "RA1")
      (value "100k")
      (footprint "eagle-import:0603-ARV")
      (libsource (lib "eagle-import") (part "RESISTOR_ARRAY0603_X4"))
    )
    (comp (ref "RA2")
      (value "1k")
      (footprint "eagle-import:0603-ARV")
      (libsource (lib "eagle-import") (part "RESISTOR_ARRAY0603_X4"))
    )
    (comp (ref "RA3")
      (value "100k")
      (footprint "eagle-import:0603-ARV")
      (libsource (lib "eagle-import") (part "RESISTOR_ARRAY0603_X4"))
    )
    (comp (ref "RA4")
      (value "1k")
      (footprint "eagle-import:0603-ARV")
      (libsource (lib "eagle-import") (part "RESISTOR_ARRAY0603_X4"))
    )
    (comp (ref "RA5")
      (value "100k")
      (footprint "eagle-import:0603-ARV")
      (libsource (lib "eagle-import") (part "RESISTOR_ARRAY0603_X4"))
    )
    (comp (ref "RA6")
      (value "1k")
      (footprint "eagle-import:0603-ARV")
      (libsource (lib "eagle-import") (part "RESISTOR_ARRAY0603_X4"))
    )
    (comp (ref "RA7")
      (value "100k")
      (footprint "eagle-import:0603-ARV")
      (libsource (lib "eagle-import") (part "RESISTOR_ARRAY0603_X4"))
    )
    (comp (ref "RA8")
      (value "1k")
      (footprint "eagle-import:0603-ARV")
      (libsource (lib "eagle-import") (part "RESISTOR_ARRAY0603_X4"))
    )
    (comp (ref "RA9")
      (value "100k")
      (footprint "eagle-import:0603-ARV")
      (libsource (lib "eagle-import") (part "RESISTOR_ARRAY0603_X4"))
    )
    (comp (ref "RA10")
      (value "1k")
      (footprint "eagle-import:0603-ARV")
      (libsource (lib "eagle-import") (part "RESISTOR_ARRAY0603_X4"))
    )
    (comp (ref "RA11")
      (value "100k")
      (footprint "eagle-import:0603-ARV")
      (libsource (lib "eagle-import") (part "RESISTOR_ARRAY0603_X4"))
    )
    (comp (ref "S1")
      (value "TAC_SWITCHPTH")
      (footprint "eagle-import:TACTILE-PTH")
      (libsource (lib "eagle-import") (part "TAC_SWITCHPTH"))
    )
    (comp (ref "S2")
      (value "TAC_SWITCHPTH")
      (footprint "eagle-import:TACTILE-PTH")
      (libsource (lib "eagle-import") (part "TAC_SWITCHPTH"))
    )
    (comp (ref "SB1")
      (value "12V_0_CS")
      (footprint "eagle-import:SB-0603")
      (libsource (lib "eagle-import") (part "SOLDER-BRIDGE0603"))
    )
    (comp (ref "SB2")
      (value "PWR2_0_CS")
      (footprint "eagle-import:SB-0603")
      (libsource (lib "eagle-import") (part "SOLDER-BRIDGE0603"))
    )
    (comp (ref "SB3")
      (value "12V_1_CS")
      (footprint "eagle-import:SB-0603")
      (libsource (lib "eagle-import") (part "SOLDER-BRIDGE0603"))
    )
    (comp (ref "SB4")
      (value "PWR2_1_CS")
      (footprint "eagle-import:SB-0603")
      (libsource (lib "eagle-import") (part "SOLDER-BRIDGE0603"))
    )
    (comp (ref "SB5")
      (value "12V_2_CS")
      (footprint "eagle-import:SB-0603")
      (libsource (lib "eagle-import") (part "SOLDER-BRIDGE0603"))
    )
    (comp (ref "SB6")
      (value "PWR2_2_CS")
      (footprint "eagle-import:SB-0603")
      (libsource (lib "eagle-import") (part "SOLDER-BRIDGE0603"))
    )
    (comp (ref "SB7")
      (value "12V_3_CS")
      (footprint "eagle-import:SB-0603")
      (libsource (lib "eagle-import") (part "SOLDER-BRIDGE0603"))
    )
    (comp (ref "SB8")
      (value "PWR2_3_CS")
      (footprint "eagle-import:SB-0603")
      (libsource (lib "eagle-import") (part "SOLDER-BRIDGE0603"))
    )
    (comp (ref "SB9")
      (value "SID")
      (footprint "eagle-import:SB-0603")
      (libsource (lib "eagle-import") (part "SOLDER-BRIDGE0603"))
    )
    (comp (ref "SB10")
      (value "SID")
      (footprint "eagle-import:SB-0603")
      (libsource (lib "eagle-import") (part "SOLDER-BRIDGE0603"))
    )
    (comp (ref "SB11")
      (value "SID")
      (footprint "eagle-import:SB-0603")
      (libsource (lib "eagle-import") (part "SOLDER-BRIDGE0603"))
    )
    (comp (ref "SB12")
      (value "TVB_CS")
      (footprint "eagle-import:SB-0603")
      (libsource (lib "eagle-import") (part "SOLDER-BRIDGE0603"))
    )
    (comp (ref "SB13")
      (value "BVB_CS")
      (footprint "eagle-import:SB-0603")
      (libsource (lib "eagle-import") (part "SOLDER-BRIDGE0603"))
    )
    (comp (ref "SB14")
      (value "12V_3_CS")
      (footprint "eagle-import:SB-0603")
      (libsource (lib "eagle-import") (part "SOLDER-BRIDGE0603"))
    )
    (comp (ref "SB15")
      (value "PWR2_3_CS")
      (footprint "eagle-import:SB-0603")
      (libsource (lib "eagle-import") (part "SOLDER-BRIDGE0603"))
    )
    (comp (ref "SB16")
      (value "SID")
      (footprint "eagle-import:SB-0603")
      (libsource (lib "eagle-import") (part "SOLDER-BRIDGE0603"))
    )
    (comp (ref "SB17")
      (value "RXP")
      (footprint "eagle-import:SB-0402")
      (libsource (lib "eagle-import") (part "SOLDER-BRIDGE0402"))
    )
    (comp (ref "SB18")
      (value "RXN")
      (footprint "eagle-import:SB-0402")
      (libsource (lib "eagle-import") (part "SOLDER-BRIDGE0402"))
    )
    (comp (ref "SB19")
      (value "TXP")
      (footprint "eagle-import:SB-0402")
      (libsource (lib "eagle-import") (part "SOLDER-BRIDGE0402"))
    )
    (comp (ref "SB20")
      (value "TXN")
      (footprint "eagle-import:SB-0402")
      (libsource (lib "eagle-import") (part "SOLDER-BRIDGE0402"))
    )
    (comp (ref "SOCKET1")
      (value "COVEN-V1CONN")
      (footprint "eagle-import:CVN-V1-CONN")
      (libsource (lib "eagle-import") (part "COVEN-V1CONN"))
    )
    (comp (ref "SOCKET2")
      (value "COVEN-V1CONN")
      (footprint "eagle-import:CVN-V1-CONN")
      (libsource (lib "eagle-import") (part "COVEN-V1CONN"))
    )
    (comp (ref "SOCKET3")
      (value "COVEN-V1CONN")
      (footprint "eagle-import:CVN-V1-CONN")
      (libsource (lib "eagle-import") (part "COVEN-V1CONN"))
    )
    (comp (ref "SOCKET4")
      (value "COVEN-V1CONN")
      (footprint "eagle-import:CVN-V1-CONN")
      (libsource (lib "eagle-import") (part "COVEN-V1CONN"))
    )
    (comp (ref "SOCKET5")
      (value "COVEN-V1CONN")
      (footprint "eagle-import:CVN-V1-CONN")
      (libsource (lib "eagle-import") (part "COVEN-V1CONN"))
    )
    (comp (ref "U$2")
      (value "DF40-80RCP")
      (footprint "eagle-import:DF40-RCP-80")
      (libsource (lib "eagle-import") (part "DF40-80RCP"))
    )
    (comp (ref "U$3")
      (value "DF40-90RCP")
      (footprint "eagle-import:DF40-RCP-90")
      (libsource (lib "eagle-import") (part "DF40-90RCP"))
    )
    (comp (ref "U$6")
      (value "AAT4610BIGV-1-T1")
      (footprint "eagle-import:SOT23-5")
      (libsource (lib "eagle-import") (part "LOAD_SWITCH_ILIMIT"))
    )
    (comp (ref "U$11")
      (value "FRONT-PANEL")
      (footprint "eagle-import:FRONT-PANEL")
      (libsource (lib "eagle-import") (part "FRONT-PANEL"))
    )
    (comp (ref "U$12")
      (value "AAT4610BIGV-1-T1")
      (footprint "eagle-import:SOT23-5")
      (libsource (lib "eagle-import") (part "LOAD_SWITCH_ILIMIT"))
    )
    (comp (ref "U$13")
      (value "ATX-PWRVERT-NOPEGS")
      (footprint "eagle-import:ATX-24-VERT-NOPEGS")
      (libsource (lib "eagle-import") (part "ATX-PWRVERT-NOPEGS"))
    )
    (comp (ref "U$15")
      (value "MAGJACK-DUALUSB")
      (footprint "eagle-import:MAGJACK-DUALUSB")
      (libsource (lib "eagle-import") (part "MAGJACK-DUALUSB"))
    )
    (comp (ref "U$18")
      (value "AP1117IE33G")
      (footprint "eagle-import:SOT223")
      (libsource (lib "eagle-import") (part "VREGSOT223"))
    )
  )
  (nets
    (net (code "1") (name "/3.3VSB") (class "Default")
      (node (ref "C17") (pin "1") (pinfunction "1_1") (pintype "passive"))
      (node (ref "R28") (pin "2") (pinfunction "2_2") (pintype "passive"))
      (node (ref "RA1") (pin "5") (pinfunction "2_5") (pintype "passive"))
      (node (ref "RA1") (pin "6") (pinfunction "2_6") (pintype "passive"))
      (node (ref "RA1") (pin "7") (pinfunction "2_7") (pintype "passive"))
      (node (ref "RA1") (pin "8") (pinfunction "2_8") (pintype "passive"))
      (node (ref "RA11") (pin "5") (pinfunction "2_5") (pintype "passive"))
      (node (ref "RA11") (pin "6") (pinfunction "2_6") (pintype "passive"))
      (node (ref "RA11") (pin "7") (pinfunction "2_7") (pintype "passive"))
      (node (ref "RA11") (pin "8") (pinfunction "2_8") (pintype "passive"))
      (node (ref "RA3") (pin "5") (pinfunction "2_5") (pintype "passive"))
      (node (ref "RA3") (pin "6") (pinfunction "2_6") (pintype "passive"))
      (node (ref "RA3") (pin "7") (pinfunction "2_7") (pintype "passive"))
      (node (ref "RA3") (pin "8") (pinfunction "2_8") (pintype "passive"))
      (node (ref "RA5") (pin "5") (pinfunction "2_5") (pintype "passive"))
      (node (ref "RA5") (pin "6") (pinfunction "2_6") (pintype "passive"))
      (node (ref "RA5") (pin "7") (pinfunction "2_7") (pintype "passive"))
      (node (ref "RA5") (pin "8") (pinfunction "2_8") (pintype "passive"))
      (node (ref "RA7") (pin "5") (pinfunction "2_5") (pintype "passive"))
      (node (ref "RA7") (pin "6") (pinfunction "2_6") (pintype "passive"))
      (node (ref "RA7") (pin "7") (pinfunction "2_7") (pintype "passive"))
      (node (ref "RA7") (pin "8") (pinfunction "2_8") (pintype "passive"))
      (node (ref "RA9") (pin "5") (pinfunction "2_5") (pintype "passive"))
      (node (ref "RA9") (pin "6") (pinfunction "2_6") (pintype "passive"))
      (node (ref "RA9") (pin "7") (pinfunction "2_7") (pintype "passive"))
      (node (ref "RA9") (pin "8") (pinfunction "2_8") (pintype "passive"))
      (node (ref "U$18") (pin "2") (pinfunction "OUT_2") (pintype "passive"))
      (node (ref "U$18") (pin "4") (pinfunction "OUT_4") (pintype "passive"))
      (node (ref "U$2") (pin "1") (pinfunction "1_1") (pintype "bidirectional"))
      (node (ref "U$2") (pin "2") (pinfunction "2_2") (pintype "bidirectional"))
    )
    (net (code "2") (name "/5V") (class "Default")
      (node (ref "C1") (pin "1") (pinfunction "1_1") (pintype "passive"))
      (node (ref "C7") (pin "1") (pinfunction "1_1") (pintype "passive"))
      (node (ref "CONN7") (pin "P$1") (pinfunction "P_P$1") (pintype "bidirectional"))
      (node (ref "U$12") (pin "4") (pinfunction "EN_4") (pintype "bidirectional"))
      (node (ref "U$12") (pin "5") (pinfunction "IN_5") (pintype "bidirectional"))
      (node (ref "U$13") (pin "21") (pinfunction "5V_21") (pintype "bidirectional"))
      (node (ref "U$13") (pin "22") (pinfunction "5V_22") (pintype "bidirectional"))
      (node (ref "U$13") (pin "23") (pinfunction "5V_23") (pintype "bidirectional"))
      (node (ref "U$13") (pin "4") (pinfunction "5V_4") (pintype "bidirectional"))
      (node (ref "U$13") (pin "6") (pinfunction "5V_6") (pintype "bidirectional"))
      (node (ref "U$6") (pin "4") (pinfunction "EN_4") (pintype "bidirectional"))
      (node (ref "U$6") (pin "5") (pinfunction "IN_5") (pintype "bidirectional"))
    )
    (net (code "3") (name "/5VSB") (class "Default")
      (node (ref "C16") (pin "1") (pinfunction "1_1") (pintype "passive"))
      (node (ref "R26") (pin "2") (pinfunction "2_2") (pintype "passive"))
      (node (ref "R27") (pin "2") (pinfunction "2_2") (pintype "passive"))
      (node (ref "U$13") (pin "9") (pinfunction "5V_STBY_9") (pintype "bidirectional"))
      (node (ref "U$18") (pin "3") (pinfunction "IN_3") (pintype "input"))
      (node (ref "U$2") (pin "78") (pinfunction "78_78") (pintype "bidirectional"))
      (node (ref "U$2") (pin "79") (pinfunction "79_79") (pintype "bidirectional"))
      (node (ref "U$2") (pin "80") (pinfunction "80_80") (pintype "bidirectional"))
    )
    (net (code "4") (name "/12V_0") (class "Default")
      (node (ref "JP6") (pin "8") (pinfunction "8_8") (pintype "passive"))
      (node (ref "SB1") (pin "R1") (pinfunction "P$2_R1") (pintype "passive"))
      (node (ref "SB1") (pin "R2") (pinfunction "P$2_R2") (pintype "passive"))
      (node (ref "SOCKET1") (pin "A2") (pinfunction "12V_A2") (pintype "input"))
      (node (ref "SOCKET1") (pin "B1") (pinfunction "12V_B1") (pintype "input"))
      (node (ref "SOCKET1") (pin "B2") (pinfunction "12V_B2") (pintype "input"))
    )
    (net (code "5") (name "/12V_1") (class "Default")
      (node (ref "SB3") (pin "R1") (pinfunction "P$2_R1") (pintype "passive"))
      (node (ref "SB3") (pin "R2") (pinfunction "P$2_R2") (pintype "passive"))
      (node (ref "SOCKET2") (pin "A2") (pinfunction "12V_A2") (pintype "input"))
      (node (ref "SOCKET2") (pin "B1") (pinfunction "12V_B1") (pintype "input"))
      (node (ref "SOCKET2") (pin "B2") (pinfunction "12V_B2") (pintype "input"))
    )
    (net (code "6") (name "/12V_2") (class "Default")
      (node (ref "SB5") (pin "R1") (pinfunction "P$2_R1") (pintype "passive"))
      (node (ref "SB5") (pin "R2") (pinfunction "P$2_R2") (pintype "passive"))
      (node (ref "SOCKET3") (pin "A2") (pinfunction "12V_A2") (pintype "input"))
      (node (ref "SOCKET3") (pin "B1") (pinfunction "12V_B1") (pintype "input"))
      (node (ref "SOCKET3") (pin "B2") (pinfunction "12V_B2") (pintype "input"))
    )
    (net (code "7") (name "/12V_3") (class "Default")
      (node (ref "SB7") (pin "R1") (pinfunction "P$2_R1") (pintype "passive"))
      (node (ref "SB7") (pin "R2") (pinfunction "P$2_R2") (pintype "passive"))
      (node (ref "SOCKET4") (pin "A2") (pinfunction "12V_A2") (pintype "input"))
      (node (ref "SOCKET4") (pin "B1") (pinfunction "12V_B1") (pintype "input"))
      (node (ref "SOCKET4") (pin "B2") (pinfunction "12V_B2") (pintype "input"))
    )
    (net (code "8") (name "/12V_4") (class "Default")
      (node (ref "SB14") (pin "R1") (pinfunction "P$2_R1") (pintype "passive"))
      (node (ref "SB14") (pin "R2") (pinfunction "P$2_R2") (pintype "passive"))
      (node (ref "SOCKET5") (pin "A2") (pinfunction "12V_A2") (pintype "input"))
      (node (ref "SOCKET5") (pin "B1") (pinfunction "12V_B1") (pintype "input"))
      (node (ref "SOCKET5") (pin "B2") (pinfunction "12V_B2") (pintype "input"))
    )
    (net (code "9") (name "/B_VBUS") (class "Default")
      (node (ref "C3") (pin "1") (pinfunction "+_1") (pintype "passive"))
      (node (ref "CONN6") (pin "P") (pinfunction "P_P") (pintype "bidirectional"))
      (node (ref "SB13") (pin "R1") (pinfunction "P$2_R1") (pintype "passive"))
      (node (ref "SB13") (pin "R2") (pinfunction "P$2_R2") (pintype "passive"))
      (node (ref "U$15") (pin "BVBUS") (pinfunction "VBUS_BVBUS") (pintype "bidirectional"))
    )
    (net (code "10") (name "/COM_RX_0") (class "Default")
      (node (ref "JP6") (pin "6") (pinfunction "6_6") (pintype "passive"))
      (node (ref "SOCKET1") (pin "A8") (pinfunction "COM_RX_A8") (pintype "bidirectional"))
      (node (ref "U$2") (pin "67") (pinfunction "67_67") (pintype "bidirectional"))
    )
    (net (code "11") (name "/COM_RX_1") (class "Default")
      (node (ref "SOCKET2") (pin "A8") (pinfunction "COM_RX_A8") (pintype "bidirectional"))
      (node (ref "U$2") (pin "60") (pinfunction "60_60") (pintype "bidirectional"))
    )
    (net (code "12") (name "/COM_RX_2") (class "Default")
      (node (ref "SOCKET3") (pin "A8") (pinfunction "COM_RX_A8") (pintype "bidirectional"))
      (node (ref "U$2") (pin "53") (pinfunction "53_53") (pintype "bidirectional"))
    )
    (net (code "13") (name "/COM_RX_3") (class "Default")
      (node (ref "SOCKET4") (pin "A8") (pinfunction "COM_RX_A8") (pintype "bidirectional"))
      (node (ref "U$2") (pin "46") (pinfunction "46_46") (pintype "bidirectional"))
    )
    (net (code "14") (name "/COM_RX_4") (class "Default")
      (node (ref "SOCKET5") (pin "A8") (pinfunction "COM_RX_A8") (pintype "bidirectional"))
      (node (ref "U$2") (pin "35") (pinfunction "35_35") (pintype "bidirectional"))
    )
    (net (code "15") (name "/COM_TX_0") (class "Default")
      (node (ref "JP6") (pin "5") (pinfunction "5_5") (pintype "passive"))
      (node (ref "SOCKET1") (pin "A7") (pinfunction "COM_TX_A7") (pintype "bidirectional"))
      (node (ref "U$2") (pin "68") (pinfunction "68_68") (pintype "bidirectional"))
    )
    (net (code "16") (name "/COM_TX_1") (class "Default")
      (node (ref "SOCKET2") (pin "A7") (pinfunction "COM_TX_A7") (pintype "bidirectional"))
      (node (ref "U$2") (pin "61") (pinfunction "61_61") (pintype "bidirectional"))
    )
    (net (code "17") (name "/COM_TX_2") (class "Default")
      (node (ref "SOCKET3") (pin "A7") (pinfunction "COM_TX_A7") (pintype "bidirectional"))
      (node (ref "U$2") (pin "54") (pinfunction "54_54") (pintype "bidirectional"))
    )
    (net (code "18") (name "/COM_TX_3") (class "Default")
      (node (ref "SOCKET4") (pin "A7") (pinfunction "COM_TX_A7") (pintype "bidirectional"))
      (node (ref "U$2") (pin "47") (pinfunction "47_47") (pintype "bidirectional"))
    )
    (net (code "19") (name "/COM_TX_4") (class "Default")
      (node (ref "SOCKET5") (pin "A7") (pinfunction "COM_TX_A7") (pintype "bidirectional"))
      (node (ref "U$2") (pin "34") (pinfunction "34_34") (pintype "bidirectional"))
    )
    (net (code "20") (name "/E0_RXN") (class "Default")
      (node (ref "C53") (pin "1") (pinfunction "1_1") (pintype "passive"))
      (node (ref "SOCKET1") (pin "B44") (pinfunction "ETH0_RX_N_B44") (pintype "bidirectional"))
    )
    (net (code "21") (name "/E0_RXN_C") (class "Default")
      (node (ref "C53") (pin "2") (pinfunction "2_2") (pintype "passive"))
      (node (ref "SB18") (pin "L1") (pinfunction "P$1_L1") (pintype "passive"))
      (node (ref "SB18") (pin "L2") (pinfunction "P$1_L2") (pintype "passive"))
      (node (ref "U$3") (pin "82") (pinfunction "82_82") (pintype "bidirectional"))
    )
    (net (code "22") (name "/E0_RXP") (class "Default")
      (node (ref "C52") (pin "1") (pinfunction "1_1") (pintype "passive"))
      (node (ref "SOCKET1") (pin "B43") (pinfunction "ETH0_RX_P_B43") (pintype "bidirectional"))
    )
    (net (code "23") (name "/E0_RXP_C") (class "Default")
      (node (ref "C52") (pin "2") (pinfunction "2_2") (pintype "passive"))
      (node (ref "SB17") (pin "L1") (pinfunction "P$1_L1") (pintype "passive"))
      (node (ref "SB17") (pin "L2") (pinfunction "P$1_L2") (pintype "passive"))
      (node (ref "U$3") (pin "83") (pinfunction "83_83") (pintype "bidirectional"))
    )
    (net (code "24") (name "/E0_SHLD") (class "Default")
      (node (ref "U$15") (pin "S1") (pinfunction "SHIELD_S1") (pintype "bidirectional"))
      (node (ref "U$15") (pin "S2") (pinfunction "SHIELD_S2") (pintype "bidirectional"))
      (node (ref "U$15") (pin "S3") (pinfunction "SHIELD_S3") (pintype "bidirectional"))
      (node (ref "U$15") (pin "S4") (pinfunction "SHIELD_S4") (pintype "bidirectional"))
      (node (ref "U$15") (pin "S7") (pinfunction "SHELL_S7") (pintype "bidirectional"))
      (node (ref "U$15") (pin "S8") (pinfunction "SHELL_S8") (pintype "bidirectional"))
    )
    (net (code "25") (name "/E0_TXN") (class "Default")
      (node (ref "C51") (pin "1") (pinfunction "1_1") (pintype "passive"))
      (node (ref "SOCKET1") (pin "B48") (pinfunction "ETH0_TX_N_B48") (pintype "bidirectional"))
    )
    (net (code "26") (name "/E0_TXN_C") (class "Default")
      (node (ref "C51") (pin "2") (pinfunction "2_2") (pintype "passive"))
      (node (ref "SB20") (pin "L1") (pinfunction "P$1_L1") (pintype "passive"))
      (node (ref "SB20") (pin "L2") (pinfunction "P$1_L2") (pintype "passive"))
      (node (ref "U$3") (pin "85") (pinfunction "85_85") (pintype "bidirectional"))
    )
    (net (code "27") (name "/E0_TXP") (class "Default")
      (node (ref "C50") (pin "1") (pinfunction "1_1") (pintype "passive"))
      (node (ref "SOCKET1") (pin "B47") (pinfunction "ETH0_TX_P_B47") (pintype "bidirectional"))
    )
    (net (code "28") (name "/E0_TXP_C") (class "Default")
      (node (ref "C50") (pin "2") (pinfunction "2_2") (pintype "passive"))
      (node (ref "SB19") (pin "L1") (pinfunction "P$1_L1") (pintype "passive"))
      (node (ref "SB19") (pin "L2") (pinfunction "P$1_L2") (pintype "passive"))
      (node (ref "U$3") (pin "86") (pinfunction "86_86") (pintype "bidirectional"))
    )
    (net (code "29") (name "/E1_RXN") (class "Default")
      (node (ref "C11") (pin "1") (pinfunction "1_1") (pintype "passive"))
      (node (ref "SOCKET2") (pin "B44") (pinfunction "ETH0_RX_N_B44") (pintype "bidirectional"))
    )
    (net (code "30") (name "/E1_RXP") (class "Default")
      (node (ref "C10") (pin "1") (pinfunction "1_1") (pintype "passive"))
      (node (ref "SOCKET2") (pin "B43") (pinfunction "ETH0_RX_P_B43") (pintype "bidirectional"))
    )
    (net (code "31") (name "/E1_TXN") (class "Default")
      (node (ref "C9") (pin "1") (pinfunction "1_1") (pintype "passive"))
      (node (ref "SOCKET2") (pin "B48") (pinfunction "ETH0_TX_N_B48") (pintype "bidirectional"))
    )
    (net (code "32") (name "/E1_TXP") (class "Default")
      (node (ref "C6") (pin "1") (pinfunction "1_1") (pintype "passive"))
      (node (ref "SOCKET2") (pin "B47") (pinfunction "ETH0_TX_P_B47") (pintype "bidirectional"))
    )
    (net (code "33") (name "/E2_RXN") (class "Default")
      (node (ref "C33") (pin "2") (pinfunction "2_2") (pintype "passive"))
      (node (ref "SOCKET3") (pin "B44") (pinfunction "ETH0_RX_N_B44") (pintype "bidirectional"))
    )
    (net (code "34") (name "/E2_RXP") (class "Default")
      (node (ref "C32") (pin "2") (pinfunction "2_2") (pintype "passive"))
      (node (ref "SOCKET3") (pin "B43") (pinfunction "ETH0_RX_P_B43") (pintype "bidirectional"))
    )
    (net (code "35") (name "/E2_TXN") (class "Default")
      (node (ref "C31") (pin "2") (pinfunction "2_2") (pintype "passive"))
      (node (ref "SOCKET3") (pin "B48") (pinfunction "ETH0_TX_N_B48") (pintype "bidirectional"))
    )
    (net (code "36") (name "/E2_TXP") (class "Default")
      (node (ref "C30") (pin "2") (pinfunction "2_2") (pintype "passive"))
      (node (ref "SOCKET3") (pin "B47") (pinfunction "ETH0_TX_P_B47") (pintype "bidirectional"))
    )
    (net (code "37") (name "/E3_RXN") (class "Default")
      (node (ref "C26") (pin "2") (pinfunction "2_2") (pintype "passive"))
      (node (ref "SOCKET4") (pin "B44") (pinfunction "ETH0_RX_N_B44") (pintype "bidirectional"))
    )
    (net (code "38") (name "/E3_RXP") (class "Default")
      (node (ref "C25") (pin "2") (pinfunction "2_2") (pintype "passive"))
      (node (ref "SOCKET4") (pin "B43") (pinfunction "ETH0_RX_P_B43") (pintype "bidirectional"))
    )
    (net (code "39") (name "/E3_TXN") (class "Default")
      (node (ref "C24") (pin "2") (pinfunction "2_2") (pintype "passive"))
      (node (ref "SOCKET4") (pin "B48") (pinfunction "ETH0_TX_N_B48") (pintype "bidirectional"))
    )
    (net (code "40") (name "/E3_TXP") (class "Default")
      (node (ref "C23") (pin "2") (pinfunction "2_2") (pintype "passive"))
      (node (ref "SOCKET4") (pin "B47") (pinfunction "ETH0_TX_P_B47") (pintype "bidirectional"))
    )
    (net (code "41") (name "/E4_RXN") (class "Default")
      (node (ref "C49") (pin "2") (pinfunction "2_2") (pintype "passive"))
      (node (ref "SOCKET5") (pin "B44") (pinfunction "ETH0_RX_N_B44") (pintype "bidirectional"))
    )
    (net (code "42") (name "/E4_RXP") (class "Default")
      (node (ref "C48") (pin "2") (pinfunction "2_2") (pintype "passive"))
      (node (ref "SOCKET5") (pin "B43") (pinfunction "ETH0_RX_P_B43") (pintype "bidirectional"))
    )
    (net (code "43") (name "/E4_TXN") (class "Default")
      (node (ref "C47") (pin "2") (pinfunction "2_2") (pintype "passive"))
      (node (ref "SOCKET5") (pin "B48") (pinfunction "ETH0_TX_N_B48") (pintype "bidirectional"))
    )
    (net (code "44") (name "/E4_TXP") (class "Default")
      (node (ref "C46") (pin "2") (pinfunction "2_2") (pintype "passive"))
      (node (ref "SOCKET5") (pin "B47") (pinfunction "ETH0_TX_P_B47") (pintype "bidirectional"))
    )
    (net (code "45") (name "/EX_RXN") (class "Default")
      (node (ref "SB18") (pin "R1") (pinfunction "P$2_R1") (pintype "passive"))
      (node (ref "SB18") (pin "R2") (pinfunction "P$2_R2") (pintype "passive"))
      (node (ref "U$15") (pin "R5") (pinfunction "RN_R5") (pintype "bidirectional"))
      (node (ref "U$3") (pin "6") (pinfunction "6_6") (pintype "bidirectional"))
    )
    (net (code "46") (name "/EX_RXP") (class "Default")
      (node (ref "SB17") (pin "R1") (pinfunction "P$2_R1") (pintype "passive"))
      (node (ref "SB17") (pin "R2") (pinfunction "P$2_R2") (pintype "passive"))
      (node (ref "U$15") (pin "R4") (pinfunction "RP_R4") (pintype "bidirectional"))
      (node (ref "U$3") (pin "5") (pinfunction "5_5") (pintype "bidirectional"))
    )
    (net (code "47") (name "/EX_TXN") (class "Default")
      (node (ref "SB20") (pin "R1") (pinfunction "P$2_R1") (pintype "passive"))
      (node (ref "SB20") (pin "R2") (pinfunction "P$2_R2") (pintype "passive"))
      (node (ref "U$15") (pin "R3") (pinfunction "TN_R3") (pintype "bidirectional"))
      (node (ref "U$3") (pin "9") (pinfunction "9_9") (pintype "bidirectional"))
    )
    (net (code "48") (name "/EX_TXP") (class "Default")
      (node (ref "SB19") (pin "R1") (pinfunction "P$2_R1") (pintype "passive"))
      (node (ref "SB19") (pin "R2") (pinfunction "P$2_R2") (pintype "passive"))
      (node (ref "U$15") (pin "R2") (pinfunction "TP_R2") (pintype "bidirectional"))
      (node (ref "U$3") (pin "8") (pinfunction "8_8") (pintype "bidirectional"))
    )
    (net (code "49") (name "/HD_LED") (class "Default")
      (node (ref "U$11") (pin "HDLED-") (pinfunction "HLED-_HDLED-") (pintype "bidirectional"))
      (node (ref "U$2") (pin "7") (pinfunction "7_7") (pintype "bidirectional"))
    )
    (net (code "50") (name "/I2C_SCL_0") (class "Default")
      (node (ref "JP1") (pin "7") (pinfunction "7_7") (pintype "passive"))
      (node (ref "SOCKET1") (pin "B5") (pinfunction "I2C_SCL_B5") (pintype "bidirectional"))
    )
    (net (code "51") (name "/I2C_SCL_1") (class "Default")
      (node (ref "JP2") (pin "7") (pinfunction "7_7") (pintype "passive"))
      (node (ref "SOCKET2") (pin "B5") (pinfunction "I2C_SCL_B5") (pintype "bidirectional"))
    )
    (net (code "52") (name "/I2C_SCL_2") (class "Default")
      (node (ref "JP3") (pin "7") (pinfunction "7_7") (pintype "passive"))
      (node (ref "SOCKET3") (pin "B5") (pinfunction "I2C_SCL_B5") (pintype "bidirectional"))
    )
    (net (code "53") (name "/I2C_SCL_3") (class "Default")
      (node (ref "JP4") (pin "7") (pinfunction "7_7") (pintype "passive"))
      (node (ref "SOCKET4") (pin "B5") (pinfunction "I2C_SCL_B5") (pintype "bidirectional"))
    )
    (net (code "54") (name "/I2C_SCL_4") (class "Default")
      (node (ref "JP5") (pin "7") (pinfunction "7_7") (pintype "passive"))
      (node (ref "SOCKET5") (pin "B5") (pinfunction "I2C_SCL_B5") (pintype "bidirectional"))
    )
    (net (code "55") (name "/I2C_SDA_0") (class "Default")
      (node (ref "JP1") (pin "8") (pinfunction "8_8") (pintype "passive"))
      (node (ref "SOCKET1") (pin "B6") (pinfunction "I2C_SDA_B6") (pintype "bidirectional"))
    )
    (net (code "56") (name "/I2C_SDA_1") (class "Default")
      (node (ref "JP2") (pin "8") (pinfunction "8_8") (pintype "passive"))
      (node (ref "SOCKET2") (pin "B6") (pinfunction "I2C_SDA_B6") (pintype "bidirectional"))
    )
    (net (code "57") (name "/I2C_SDA_2") (class "Default")
      (node (ref "JP3") (pin "8") (pinfunction "8_8") (pintype "passive"))
      (node (ref "SOCKET3") (pin "B6") (pinfunction "I2C_SDA_B6") (pintype "bidirectional"))
    )
    (net (code "58") (name "/I2C_SDA_3") (class "Default")
      (node (ref "JP4") (pin "8") (pinfunction "8_8") (pintype "passive"))
      (node (ref "SOCKET4") (pin "B6") (pinfunction "I2C_SDA_B6") (pintype "bidirectional"))
    )
    (net (code "59") (name "/I2C_SDA_4") (class "Default")
      (node (ref "JP5") (pin "8") (pinfunction "8_8") (pintype "passive"))
      (node (ref "SOCKET5") (pin "B6") (pinfunction "I2C_SDA_B6") (pintype "bidirectional"))
    )
    (net (code "60") (name "/LED0_1") (class "Default")
      (node (ref "R17") (pin "1") (pinfunction "1_1") (pintype "passive"))
      (node (ref "U$3") (pin "79") (pinfunction "79_79") (pintype "bidirectional"))
    )
    (net (code "61") (name "/LED0_2") (class "Default")
      (node (ref "RA2") (pin "4") (pinfunction "1_4") (pintype "passive"))
      (node (ref "U$3") (pin "80") (pinfunction "80_80") (pintype "bidirectional"))
    )
    (net (code "62") (name "/LED1_1") (class "Default")
      (node (ref "R19") (pin "1") (pinfunction "1_1") (pintype "passive"))
      (node (ref "U$3") (pin "69") (pinfunction "69_69") (pintype "bidirectional"))
    )
    (net (code "63") (name "/LED1_2") (class "Default")
      (node (ref "RA4") (pin "5") (pinfunction "2_5") (pintype "passive"))
      (node (ref "U$3") (pin "70") (pinfunction "70_70") (pintype "bidirectional"))
    )
    (net (code "64") (name "/LED2_1") (class "Default")
      (node (ref "R21") (pin "1") (pinfunction "1_1") (pintype "passive"))
      (node (ref "U$3") (pin "59") (pinfunction "59_59") (pintype "bidirectional"))
    )
    (net (code "65") (name "/LED2_2") (class "Default")
      (node (ref "RA6") (pin "5") (pinfunction "2_5") (pintype "passive"))
      (node (ref "U$3") (pin "60") (pinfunction "60_60") (pintype "bidirectional"))
    )
    (net (code "66") (name "/LED3_1") (class "Default")
      (node (ref "R23") (pin "1") (pinfunction "1_1") (pintype "passive"))
      (node (ref "U$3") (pin "32") (pinfunction "32_32") (pintype "bidirectional"))
    )
    (net (code "67") (name "/LED3_2") (class "Default")
      (node (ref "RA8") (pin "5") (pinfunction "2_5") (pintype "passive"))
      (node (ref "U$3") (pin "31") (pinfunction "31_31") (pintype "bidirectional"))
    )
    (net (code "68") (name "/LED4_1") (class "Default")
      (node (ref "R18") (pin "1") (pinfunction "1_1") (pintype "passive"))
      (node (ref "U$3") (pin "22") (pinfunction "22_22") (pintype "bidirectional"))
    )
    (net (code "69") (name "/LED4_2") (class "Default")
      (node (ref "RA10") (pin "5") (pinfunction "2_5") (pintype "passive"))
      (node (ref "U$3") (pin "21") (pinfunction "21_21") (pintype "bidirectional"))
    )
    (net (code "70") (name "/LEDX_1") (class "Default")
      (node (ref "U$15") (pin "R7") (pinfunction "LYN_R7") (pintype "bidirectional"))
      (node (ref "U$3") (pin "12") (pinfunction "12_12") (pintype "bidirectional"))
    )
    (net (code "71") (name "/LEDX_2") (class "Default")
      (node (ref "U$15") (pin "R9") (pinfunction "LGN_R9") (pintype "bidirectional"))
      (node (ref "U$3") (pin "11") (pinfunction "11_11") (pintype "bidirectional"))
    )
    (net (code "72") (name "/PRSNT#_0") (class "Default")
      (node (ref "C19") (pin "1") (pinfunction "1_1") (pintype "passive"))
      (node (ref "IC1") (pin "3") (pinfunction "2A_3") (pintype "bidirectional"))
      (node (ref "JP6") (pin "2") (pinfunction "2_2") (pintype "passive"))
      (node (ref "RA1") (pin "3") (pinfunction "1_3") (pintype "passive"))
      (node (ref "SOCKET1") (pin "A1") (pinfunction "PRSNT#_A1") (pintype "bidirectional"))
      (node (ref "U$2") (pin "69") (pinfunction "69_69") (pintype "bidirectional"))
    )
    (net (code "73") (name "/PRSNT#_1") (class "Default")
      (node (ref "C34") (pin "1") (pinfunction "1_1") (pintype "passive"))
      (node (ref "IC2") (pin "3") (pinfunction "2A_3") (pintype "bidirectional"))
      (node (ref "RA3") (pin "3") (pinfunction "1_3") (pintype "passive"))
      (node (ref "SOCKET2") (pin "A1") (pinfunction "PRSNT#_A1") (pintype "bidirectional"))
      (node (ref "U$2") (pin "62") (pinfunction "62_62") (pintype "bidirectional"))
    )
    (net (code "74") (name "/PRSNT#_2") (class "Default")
      (node (ref "C37") (pin "1") (pinfunction "1_1") (pintype "passive"))
      (node (ref "IC3") (pin "3") (pinfunction "2A_3") (pintype "bidirectional"))
      (node (ref "RA5") (pin "3") (pinfunction "1_3") (pintype "passive"))
      (node (ref "SOCKET3") (pin "A1") (pinfunction "PRSNT#_A1") (pintype "bidirectional"))
      (node (ref "U$2") (pin "55") (pinfunction "55_55") (pintype "bidirectional"))
    )
    (net (code "75") (name "/PRSNT#_3") (class "Default")
      (node (ref "C40") (pin "1") (pinfunction "1_1") (pintype "passive"))
      (node (ref "IC4") (pin "3") (pinfunction "2A_3") (pintype "bidirectional"))
      (node (ref "RA7") (pin "3") (pinfunction "1_3") (pintype "passive"))
      (node (ref "SOCKET4") (pin "A1") (pinfunction "PRSNT#_A1") (pintype "bidirectional"))
      (node (ref "U$2") (pin "48") (pinfunction "48_48") (pintype "bidirectional"))
    )
    (net (code "76") (name "/PRSNT#_4") (class "Default")
      (node (ref "C43") (pin "1") (pinfunction "1_1") (pintype "passive"))
      (node (ref "IC5") (pin "3") (pinfunction "2A_3") (pintype "bidirectional"))
      (node (ref "RA9") (pin "3") (pinfunction "1_3") (pintype "passive"))
      (node (ref "SOCKET5") (pin "A1") (pinfunction "PRSNT#_A1") (pintype "bidirectional"))
      (node (ref "U$2") (pin "33") (pinfunction "33_33") (pintype "bidirectional"))
    )
    (net (code "77") (name "/PRSNT#_5") (class "Default")
      (node (ref "RA11") (pin "2") (pinfunction "1_2") (pintype "passive"))
      (node (ref "U$2") (pin "26") (pinfunction "26_26") (pintype "bidirectional"))
    )
    (net (code "78") (name "/PRSNT#_6") (class "Default")
      (node (ref "RA11") (pin "3") (pinfunction "1_3") (pintype "passive"))
      (node (ref "U$2") (pin "19") (pinfunction "19_19") (pintype "bidirectional"))
    )
    (net (code "79") (name "/PRSNT#_7") (class "Default")
      (node (ref "RA11") (pin "4") (pinfunction "1_4") (pintype "passive"))
      (node (ref "U$2") (pin "12") (pinfunction "12_12") (pintype "bidirectional"))
    )
    (net (code "80") (name "/PWR2") (class "Default")
      (node (ref "CONN1") (pin "P$1") (pinfunction "P_P$1") (pintype "bidirectional"))
      (node (ref "SB15") (pin "L1") (pinfunction "P$1_L1") (pintype "passive"))
      (node (ref "SB15") (pin "L2") (pinfunction "P$1_L2") (pintype "passive"))
      (node (ref "SB2") (pin "L1") (pinfunction "P$1_L1") (pintype "passive"))
      (node (ref "SB2") (pin "L2") (pinfunction "P$1_L2") (pintype "passive"))
      (node (ref "SB4") (pin "L1") (pinfunction "P$1_L1") (pintype "passive"))
      (node (ref "SB4") (pin "L2") (pinfunction "P$1_L2") (pintype "passive"))
      (node (ref "SB6") (pin "L1") (pinfunction "P$1_L1") (pintype "passive"))
      (node (ref "SB6") (pin "L2") (pinfunction "P$1_L2") (pintype "passive"))
      (node (ref "SB8") (pin "L1") (pinfunction "P$1_L1") (pintype "passive"))
      (node (ref "SB8") (pin "L2") (pinfunction "P$1_L2") (pintype "passive"))
    )
    (net (code "81") (name "/PWR2_0") (class "Default")
      (node (ref "JP6") (pin "7") (pinfunction "7_7") (pintype "passive"))
      (node (ref "SB2") (pin "R1") (pinfunction "P$2_R1") (pintype "passive"))
      (node (ref "SB2") (pin "R2") (pinfunction "P$2_R2") (pintype "passive"))
      (node (ref "SOCKET1") (pin "A3") (pinfunction "12V_A3") (pintype "input"))
      (node (ref "SOCKET1") (pin "B3") (pinfunction "12V_B3") (pintype "input"))
    )
    (net (code "82") (name "/PWR2_1") (class "Default")
      (node (ref "SB4") (pin "R1") (pinfunction "P$2_R1") (pintype "passive"))
      (node (ref "SB4") (pin "R2") (pinfunction "P$2_R2") (pintype "passive"))
      (node (ref "SOCKET2") (pin "A3") (pinfunction "12V_A3") (pintype "input"))
      (node (ref "SOCKET2") (pin "B3") (pinfunction "12V_B3") (pintype "input"))
    )
    (net (code "83") (name "/PWR2_2") (class "Default")
      (node (ref "SB6") (pin "R1") (pinfunction "P$2_R1") (pintype "passive"))
      (node (ref "SB6") (pin "R2") (pinfunction "P$2_R2") (pintype "passive"))
      (node (ref "SOCKET3") (pin "A3") (pinfunction "12V_A3") (pintype "input"))
      (node (ref "SOCKET3") (pin "B3") (pinfunction "12V_B3") (pintype "input"))
    )
    (net (code "84") (name "/PWR2_3") (class "Default")
      (node (ref "SB8") (pin "R1") (pinfunction "P$2_R1") (pintype "passive"))
      (node (ref "SB8") (pin "R2") (pinfunction "P$2_R2") (pintype "passive"))
      (node (ref "SOCKET4") (pin "A3") (pinfunction "12V_A3") (pintype "input"))
      (node (ref "SOCKET4") (pin "B3") (pinfunction "12V_B3") (pintype "input"))
    )
    (net (code "85") (name "/PWR2_4") (class "Default")
      (node (ref "SB15") (pin "R1") (pinfunction "P$2_R1") (pintype "passive"))
      (node (ref "SB15") (pin "R2") (pinfunction "P$2_R2") (pintype "passive"))
      (node (ref "SOCKET5") (pin "A3") (pinfunction "12V_A3") (pintype "input"))
      (node (ref "SOCKET5") (pin "B3") (pinfunction "12V_B3") (pintype "input"))
    )
    (net (code "86") (name "/PWR_BUT") (class "Default")
      (node (ref "C14") (pin "1") (pinfunction "1_1") (pintype "passive"))
      (node (ref "R27") (pin "1") (pinfunction "1_1") (pintype "passive"))
      (node (ref "S2") (pin "4") (pinfunction "4_4") (pintype "passive"))
      (node (ref "U$11") (pin "PWR_2") (pinfunction "PWR2_PWR_2") (pintype "bidirectional"))
      (node (ref "U$2") (pin "73") (pinfunction "73_73") (pintype "bidirectional"))
    )
    (net (code "87") (name "/PWR_OK") (class "Default")
      (node (ref "C45") (pin "1") (pinfunction "1_1") (pintype "passive"))
      (node (ref "U$13") (pin "8") (pinfunction "PWR_OK_8") (pintype "bidirectional"))
      (node (ref "U$2") (pin "75") (pinfunction "75_75") (pintype "bidirectional"))
    )
    (net (code "88") (name "/PWR_ON#_0") (class "Default")
      (node (ref "C27") (pin "1") (pinfunction "1_1") (pintype "passive"))
      (node (ref "IC1") (pin "1") (pinfunction "1A_1") (pintype "bidirectional"))
      (node (ref "JP6") (pin "3") (pinfunction "3_3") (pintype "passive"))
      (node (ref "RA1") (pin "4") (pinfunction "1_4") (pintype "passive"))
      (node (ref "SOCKET1") (pin "B8") (pinfunction "PWR_ON#_B8") (pintype "bidirectional"))
      (node (ref "U$2") (pin "71") (pinfunction "71_71") (pintype "bidirectional"))
    )
    (net (code "89") (name "/PWR_ON#_1") (class "Default")
      (node (ref "C35") (pin "1") (pinfunction "1_1") (pintype "passive"))
      (node (ref "IC2") (pin "1") (pinfunction "1A_1") (pintype "bidirectional"))
      (node (ref "RA3") (pin "4") (pinfunction "1_4") (pintype "passive"))
      (node (ref "SOCKET2") (pin "B8") (pinfunction "PWR_ON#_B8") (pintype "bidirectional"))
      (node (ref "U$2") (pin "64") (pinfunction "64_64") (pintype "bidirectional"))
    )
    (net (code "90") (name "/PWR_ON#_2") (class "Default")
      (node (ref "C38") (pin "1") (pinfunction "1_1") (pintype "passive"))
      (node (ref "IC3") (pin "1") (pinfunction "1A_1") (pintype "bidirectional"))
      (node (ref "RA5") (pin "4") (pinfunction "1_4") (pintype "passive"))
      (node (ref "SOCKET3") (pin "B8") (pinfunction "PWR_ON#_B8") (pintype "bidirectional"))
      (node (ref "U$2") (pin "57") (pinfunction "57_57") (pintype "bidirectional"))
    )
    (net (code "91") (name "/PWR_ON#_3") (class "Default")
      (node (ref "C41") (pin "1") (pinfunction "1_1") (pintype "passive"))
      (node (ref "IC4") (pin "1") (pinfunction "1A_1") (pintype "bidirectional"))
      (node (ref "RA7") (pin "4") (pinfunction "1_4") (pintype "passive"))
      (node (ref "SOCKET4") (pin "B8") (pinfunction "PWR_ON#_B8") (pintype "bidirectional"))
      (node (ref "U$2") (pin "50") (pinfunction "50_50") (pintype "bidirectional"))
    )
    (net (code "92") (name "/PWR_ON#_4") (class "Default")
      (node (ref "C44") (pin "1") (pinfunction "1_1") (pintype "passive"))
      (node (ref "IC5") (pin "1") (pinfunction "1A_1") (pintype "bidirectional"))
      (node (ref "RA9") (pin "4") (pinfunction "1_4") (pintype "passive"))
      (node (ref "SOCKET5") (pin "B8") (pinfunction "PWR_ON#_B8") (pintype "bidirectional"))
      (node (ref "U$2") (pin "31") (pinfunction "31_31") (pintype "bidirectional"))
    )
    (net (code "93") (name "/RESET_BUT") (class "Default")
      (node (ref "C13") (pin "1") (pinfunction "1_1") (pintype "passive"))
      (node (ref "R26") (pin "1") (pinfunction "1_1") (pintype "passive"))
      (node (ref "S1") (pin "4") (pinfunction "4_4") (pintype "passive"))
      (node (ref "U$11") (pin "RST_2") (pinfunction "RST2_RST_2") (pintype "bidirectional"))
      (node (ref "U$2") (pin "74") (pinfunction "74_74") (pintype "bidirectional"))
    )
    (net (code "94") (name "/SPI_CLK_0") (class "Default")
      (node (ref "JP1") (pin "3") (pinfunction "3_3") (pintype "passive"))
      (node (ref "SOCKET1") (pin "B27") (pinfunction "L7_P_B27") (pintype "bidirectional"))
    )
    (net (code "95") (name "/SPI_CLK_1") (class "Default")
      (node (ref "JP2") (pin "3") (pinfunction "3_3") (pintype "passive"))
      (node (ref "SOCKET2") (pin "B27") (pinfunction "L7_P_B27") (pintype "bidirectional"))
    )
    (net (code "96") (name "/SPI_CLK_2") (class "Default")
      (node (ref "JP3") (pin "3") (pinfunction "3_3") (pintype "passive"))
      (node (ref "SOCKET3") (pin "B27") (pinfunction "L7_P_B27") (pintype "bidirectional"))
    )
    (net (code "97") (name "/SPI_CLK_3") (class "Default")
      (node (ref "JP4") (pin "3") (pinfunction "3_3") (pintype "passive"))
      (node (ref "SOCKET4") (pin "B27") (pinfunction "L7_P_B27") (pintype "bidirectional"))
    )
    (net (code "98") (name "/SPI_CLK_4") (class "Default")
      (node (ref "JP5") (pin "3") (pinfunction "3_3") (pintype "passive"))
      (node (ref "SOCKET5") (pin "B27") (pinfunction "L7_P_B27") (pintype "bidirectional"))
    )
    (net (code "99") (name "/SPI_CS_0") (class "Default")
      (node (ref "JP1") (pin "5") (pinfunction "5_5") (pintype "passive"))
      (node (ref "SOCKET1") (pin "B28") (pinfunction "L7_N_B28") (pintype "bidirectional"))
    )
    (net (code "100") (name "/SPI_CS_1") (class "Default")
      (node (ref "JP2") (pin "5") (pinfunction "5_5") (pintype "passive"))
      (node (ref "SOCKET2") (pin "B28") (pinfunction "L7_N_B28") (pintype "bidirectional"))
    )
    (net (code "101") (name "/SPI_CS_2") (class "Default")
      (node (ref "JP3") (pin "5") (pinfunction "5_5") (pintype "passive"))
      (node (ref "SOCKET3") (pin "B28") (pinfunction "L7_N_B28") (pintype "bidirectional"))
    )
    (net (code "102") (name "/SPI_CS_3") (class "Default")
      (node (ref "JP4") (pin "5") (pinfunction "5_5") (pintype "passive"))
      (node (ref "SOCKET4") (pin "B28") (pinfunction "L7_N_B28") (pintype "bidirectional"))
    )
    (net (code "103") (name "/SPI_CS_4") (class "Default")
      (node (ref "JP5") (pin "5") (pinfunction "5_5") (pintype "passive"))
      (node (ref "SOCKET5") (pin "B28") (pinfunction "L7_N_B28") (pintype "bidirectional"))
    )
    (net (code "104") (name "/SPI_MISO_0") (class "Default")
      (node (ref "JP1") (pin "2") (pinfunction "2_2") (pintype "passive"))
      (node (ref "SOCKET1") (pin "B24") (pinfunction "L5_N_B24") (pintype "bidirectional"))
    )
    (net (code "105") (name "/SPI_MISO_1") (class "Default")
      (node (ref "JP2") (pin "2") (pinfunction "2_2") (pintype "passive"))
      (node (ref "SOCKET2") (pin "B24") (pinfunction "L5_N_B24") (pintype "bidirectional"))
    )
    (net (code "106") (name "/SPI_MISO_2") (class "Default")
      (node (ref "JP3") (pin "2") (pinfunction "2_2") (pintype "passive"))
      (node (ref "SOCKET3") (pin "B24") (pinfunction "L5_N_B24") (pintype "bidirectional"))
    )
    (net (code "107") (name "/SPI_MISO_3") (class "Default")
      (node (ref "JP4") (pin "2") (pinfunction "2_2") (pintype "passive"))
      (node (ref "SOCKET4") (pin "B24") (pinfunction "L5_N_B24") (pintype "bidirectional"))
    )
    (net (code "108") (name "/SPI_MISO_4") (class "Default")
      (node (ref "JP5") (pin "2") (pinfunction "2_2") (pintype "passive"))
      (node (ref "SOCKET5") (pin "B24") (pinfunction "L5_N_B24") (pintype "bidirectional"))
    )
    (net (code "109") (name "/SPI_MOSI_0") (class "Default")
      (node (ref "JP1") (pin "4") (pinfunction "4_4") (pintype "passive"))
      (node (ref "SOCKET1") (pin "B23") (pinfunction "L5_P_B23") (pintype "bidirectional"))
    )
    (net (code "110") (name "/SPI_MOSI_1") (class "Default")
      (node (ref "JP2") (pin "4") (pinfunction "4_4") (pintype "passive"))
      (node (ref "SOCKET2") (pin "B23") (pinfunction "L5_P_B23") (pintype "bidirectional"))
    )
    (net (code "111") (name "/SPI_MOSI_2") (class "Default")
      (node (ref "JP3") (pin "4") (pinfunction "4_4") (pintype "passive"))
      (node (ref "SOCKET3") (pin "B23") (pinfunction "L5_P_B23") (pintype "bidirectional"))
    )
    (net (code "112") (name "/SPI_MOSI_3") (class "Default")
      (node (ref "JP4") (pin "4") (pinfunction "4_4") (pintype "passive"))
      (node (ref "SOCKET4") (pin "B23") (pinfunction "L5_P_B23") (pintype "bidirectional"))
    )
    (net (code "113") (name "/SPI_MOSI_4") (class "Default")
      (node (ref "JP5") (pin "4") (pinfunction "4_4") (pintype "passive"))
      (node (ref "SOCKET5") (pin "B23") (pinfunction "L5_P_B23") (pintype "bidirectional"))
    )
    (net (code "114") (name "/SYS_RESET#_0") (class "Default")
      (node (ref "C18") (pin "1") (pinfunction "1_1") (pintype "passive"))
      (node (ref "IC1") (pin "6") (pinfunction "3A_6") (pintype "bidirectional"))
      (node (ref "JP6") (pin "1") (pinfunction "1_1") (pintype "passive"))
      (node (ref "RA1") (pin "2") (pinfunction "1_2") (pintype "passive"))
      (node (ref "SOCKET1") (pin "B11") (pinfunction "SYS_RESET#_B11") (pintype "bidirectional"))
      (node (ref "U$2") (pin "70") (pinfunction "70_70") (pintype "bidirectional"))
    )
    (net (code "115") (name "/SYS_RESET#_1") (class "Default")
      (node (ref "C29") (pin "1") (pinfunction "1_1") (pintype "passive"))
      (node (ref "IC2") (pin "6") (pinfunction "3A_6") (pintype "bidirectional"))
      (node (ref "RA3") (pin "2") (pinfunction "1_2") (pintype "passive"))
      (node (ref "SOCKET2") (pin "B11") (pinfunction "SYS_RESET#_B11") (pintype "bidirectional"))
      (node (ref "U$2") (pin "63") (pinfunction "63_63") (pintype "bidirectional"))
    )
    (net (code "116") (name "/SYS_RESET#_2") (class "Default")
      (node (ref "C36") (pin "1") (pinfunction "1_1") (pintype "passive"))
      (node (ref "IC3") (pin "6") (pinfunction "3A_6") (pintype "bidirectional"))
      (node (ref "RA5") (pin "2") (pinfunction "1_2") (pintype "passive"))
      (node (ref "SOCKET3") (pin "B11") (pinfunction "SYS_RESET#_B11") (pintype "bidirectional"))
      (node (ref "U$2") (pin "56") (pinfunction "56_56") (pintype "bidirectional"))
    )
    (net (code "117") (name "/SYS_RESET#_3") (class "Default")
      (node (ref "C39") (pin "1") (pinfunction "1_1") (pintype "passive"))
      (node (ref "IC4") (pin "6") (pinfunction "3A_6") (pintype "bidirectional"))
      (node (ref "RA7") (pin "2") (pinfunction "1_2") (pintype "passive"))
      (node (ref "SOCKET4") (pin "B11") (pinfunction "SYS_RESET#_B11") (pintype "bidirectional"))
      (node (ref "U$2") (pin "49") (pinfunction "49_49") (pintype "bidirectional"))
    )
    (net (code "118") (name "/SYS_RESET#_4") (class "Default")
      (node (ref "C42") (pin "1") (pinfunction "1_1") (pintype "passive"))
      (node (ref "IC5") (pin "6") (pinfunction "3A_6") (pintype "bidirectional"))
      (node (ref "RA9") (pin "2") (pinfunction "1_2") (pintype "passive"))
      (node (ref "SOCKET5") (pin "B11") (pinfunction "SYS_RESET#_B11") (pintype "bidirectional"))
      (node (ref "U$2") (pin "32") (pinfunction "32_32") (pintype "bidirectional"))
    )
    (net (code "119") (name "/T_VBUS") (class "Default")
      (node (ref "C28") (pin "1") (pinfunction "+_1") (pintype "passive"))
      (node (ref "CONN5") (pin "P") (pinfunction "P_P") (pintype "bidirectional"))
      (node (ref "SB12") (pin "R1") (pinfunction "P$2_R1") (pintype "passive"))
      (node (ref "SB12") (pin "R2") (pinfunction "P$2_R2") (pintype "passive"))
      (node (ref "U$15") (pin "TVBUS") (pinfunction "VBUS_TVBUS") (pintype "bidirectional"))
    )
    (net (code "120") (name "/UBOOT_0") (class "Default")
      (node (ref "JP1") (pin "1") (pinfunction "1_1") (pintype "passive"))
      (node (ref "SOCKET1") (pin "A13") (pinfunction "L0_P_A13") (pintype "bidirectional"))
    )
    (net (code "121") (name "/UBOOT_1") (class "Default")
      (node (ref "JP2") (pin "1") (pinfunction "1_1") (pintype "passive"))
      (node (ref "SOCKET2") (pin "A13") (pinfunction "L0_P_A13") (pintype "bidirectional"))
    )
    (net (code "122") (name "/UBOOT_2") (class "Default")
      (node (ref "JP3") (pin "1") (pinfunction "1_1") (pintype "passive"))
      (node (ref "SOCKET3") (pin "A13") (pinfunction "L0_P_A13") (pintype "bidirectional"))
    )
    (net (code "123") (name "/UBOOT_3") (class "Default")
      (node (ref "JP4") (pin "1") (pinfunction "1_1") (pintype "passive"))
      (node (ref "SOCKET4") (pin "A13") (pinfunction "L0_P_A13") (pintype "bidirectional"))
    )
    (net (code "124") (name "/UBOOT_4") (class "Default")
      (node (ref "JP5") (pin "1") (pinfunction "1_1") (pintype "passive"))
      (node (ref "SOCKET5") (pin "A13") (pinfunction "L0_P_A13") (pintype "bidirectional"))
    )
    (net (code "125") (name "/USB_N_0") (class "Default")
      (node (ref "SOCKET1") (pin "B10") (pinfunction "USB_N_B10") (pintype "bidirectional"))
      (node (ref "U$15") (pin "BD-") (pinfunction "D-_BD-") (pintype "bidirectional"))
    )
    (net (code "126") (name "/USB_N_4") (class "Default")
      (node (ref "SOCKET5") (pin "B10") (pinfunction "USB_N_B10") (pintype "bidirectional"))
      (node (ref "U$15") (pin "TD-") (pinfunction "D-_TD-") (pintype "bidirectional"))
    )
    (net (code "127") (name "/USB_P_0") (class "Default")
      (node (ref "SOCKET1") (pin "B9") (pinfunction "USB_P_B9") (pintype "bidirectional"))
      (node (ref "U$15") (pin "BD+") (pinfunction "D+_BD+") (pintype "bidirectional"))
    )
    (net (code "128") (name "/USB_P_4") (class "Default")
      (node (ref "SOCKET5") (pin "B9") (pinfunction "USB_P_B9") (pintype "bidirectional"))
      (node (ref "U$15") (pin "TD+") (pinfunction "D+_TD+") (pintype "bidirectional"))
    )
    (net (code "129") (name "/~{PS_ON}") (class "Default")
      (node (ref "C15") (pin "1") (pinfunction "1_1") (pintype "passive"))
      (node (ref "R28") (pin "1") (pinfunction "1_1") (pintype "passive"))
      (node (ref "U$13") (pin "16") (pinfunction "~{PS_ON}_16") (pintype "bidirectional"))
      (node (ref "U$2") (pin "6") (pinfunction "6_6") (pintype "bidirectional"))
    )
    (net (code "130") (name "3.3V") (class "Default")
      (node (ref "CONN4") (pin "P$1") (pinfunction "P_P$1") (pintype "bidirectional"))
      (node (ref "IC1") (pin "8") (pinfunction "VCC_8") (pintype "bidirectional"))
      (node (ref "IC2") (pin "8") (pinfunction "VCC_8") (pintype "bidirectional"))
      (node (ref "IC3") (pin "8") (pinfunction "VCC_8") (pintype "bidirectional"))
      (node (ref "IC4") (pin "8") (pinfunction "VCC_8") (pintype "bidirectional"))
      (node (ref "IC5") (pin "8") (pinfunction "VCC_8") (pintype "bidirectional"))
      (node (ref "LED0_1") (pin "A") (pinfunction "A_A") (pintype "passive"))
      (node (ref "LED0_2") (pin "A") (pinfunction "A_A") (pintype "passive"))
      (node (ref "LED1_1") (pin "A") (pinfunction "A_A") (pintype "passive"))
      (node (ref "LED1_2") (pin "A") (pinfunction "A_A") (pintype "passive"))
      (node (ref "LED2_1") (pin "A") (pinfunction "A_A") (pintype "passive"))
      (node (ref "LED2_2") (pin "A") (pinfunction "A_A") (pintype "passive"))
      (node (ref "LED3_1") (pin "A") (pinfunction "A_A") (pintype "passive"))
      (node (ref "LED3_2") (pin "A") (pinfunction "A_A") (pintype "passive"))
      (node (ref "LED4_1") (pin "A") (pinfunction "A_A") (pintype "passive"))
      (node (ref "LED4_2") (pin "A") (pinfunction "A_A") (pintype "passive"))
      (node (ref "LPRSNT_0") (pin "A") (pinfunction "A_A") (pintype "passive"))
      (node (ref "LPRSNT_1") (pin "A") (pinfunction "A_A") (pintype "passive"))
      (node (ref "LPRSNT_2") (pin "A") (pinfunction "A_A") (pintype "passive"))
      (node (ref "LPRSNT_3") (pin "A") (pinfunction "A_A") (pintype "passive"))
      (node (ref "LPRSNT_4") (pin "A") (pinfunction "A_A") (pintype "passive"))
      (node (ref "LPWR_ON_0") (pin "A") (pinfunction "A_A") (pintype "passive"))
      (node (ref "LPWR_ON_1") (pin "A") (pinfunction "A_A") (pintype "passive"))
      (node (ref "LPWR_ON_2") (pin "A") (pinfunction "A_A") (pintype "passive"))
      (node (ref "LPWR_ON_3") (pin "A") (pinfunction "A_A") (pintype "passive"))
      (node (ref "LPWR_ON_4") (pin "A") (pinfunction "A_A") (pintype "passive"))
      (node (ref "LRST_0") (pin "A") (pinfunction "A_A") (pintype "passive"))
      (node (ref "LRST_1") (pin "A") (pinfunction "A_A") (pintype "passive"))
      (node (ref "LRST_2") (pin "A") (pinfunction "A_A") (pintype "passive"))
      (node (ref "LRST_3") (pin "A") (pinfunction "A_A") (pintype "passive"))
      (node (ref "LRST_4") (pin "A") (pinfunction "A_A") (pintype "passive"))
      (node (ref "R15") (pin "1") (pinfunction "1_1") (pintype "passive"))
      (node (ref "R16") (pin "1") (pinfunction "1_1") (pintype "passive"))
      (node (ref "R24") (pin "2") (pinfunction "2_2") (pintype "passive"))
      (node (ref "R25") (pin "1") (pinfunction "1_1") (pintype "passive"))
      (node (ref "U$13") (pin "1") (pinfunction "3.3V_1") (pintype "bidirectional"))
      (node (ref "U$13") (pin "12") (pinfunction "3.3V_12") (pintype "bidirectional"))
      (node (ref "U$13") (pin "13") (pinfunction "3.3V_13") (pintype "bidirectional"))
      (node (ref "U$13") (pin "2") (pinfunction "3.3V_2") (pintype "bidirectional"))
      (node (ref "U$3") (pin "1") (pinfunction "1_1") (pintype "bidirectional"))
      (node (ref "U$3") (pin "2") (pinfunction "2_2") (pintype "bidirectional"))
      (node (ref "U$3") (pin "89") (pinfunction "89_89") (pintype "bidirectional"))
      (node (ref "U$3") (pin "90") (pinfunction "90_90") (pintype "bidirectional"))
    )
    (net (code "131") (name "12V") (class "Default")
      (node (ref "C12") (pin "12V") (pinfunction "12V_12V") (pintype "bidirectional"))
      (node (ref "C22") (pin "1") (pinfunction "+_1") (pintype "passive"))
      (node (ref "CONN3") (pin "P$1") (pinfunction "P_P$1") (pintype "bidirectional"))
      (node (ref "SB1") (pin "L1") (pinfunction "P$1_L1") (pintype "passive"))
      (node (ref "SB1") (pin "L2") (pinfunction "P$1_L2") (pintype "passive"))
      (node (ref "SB14") (pin "L1") (pinfunction "P$1_L1") (pintype "passive"))
      (node (ref "SB14") (pin "L2") (pinfunction "P$1_L2") (pintype "passive"))
      (node (ref "SB3") (pin "L1") (pinfunction "P$1_L1") (pintype "passive"))
      (node (ref "SB3") (pin "L2") (pinfunction "P$1_L2") (pintype "passive"))
      (node (ref "SB5") (pin "L1") (pinfunction "P$1_L1") (pintype "passive"))
      (node (ref "SB5") (pin "L2") (pinfunction "P$1_L2") (pintype "passive"))
      (node (ref "SB7") (pin "L1") (pinfunction "P$1_L1") (pintype "passive"))
      (node (ref "SB7") (pin "L2") (pinfunction "P$1_L2") (pintype "passive"))
      (node (ref "U$13") (pin "10") (pinfunction "12V_10") (pintype "bidirectional"))
      (node (ref "U$13") (pin "11") (pinfunction "12V_11") (pintype "bidirectional"))
    )
    (net (code "132") (name "GND") (class "Default")
      (node (ref "C1") (pin "2") (pinfunction "2_2") (pintype "passive"))
      (node (ref "C12") (pin "GND") (pinfunction "GND_GND") (pintype "bidirectional"))
      (node (ref "C13") (pin "2") (pinfunction "2_2") (pintype "passive"))
      (node (ref "C14") (pin "2") (pinfunction "2_2") (pintype "passive"))
      (node (ref "C15") (pin "2") (pinfunction "2_2") (pintype "passive"))
      (node (ref "C16") (pin "2") (pinfunction "2_2") (pintype "passive"))
      (node (ref "C17") (pin "2") (pinfunction "2_2") (pintype "passive"))
      (node (ref "C18") (pin "2") (pinfunction "2_2") (pintype "passive"))
      (node (ref "C19") (pin "2") (pinfunction "2_2") (pintype "passive"))
      (node (ref "C2") (pin "2") (pinfunction "2_2") (pintype "passive"))
      (node (ref "C22") (pin "2") (pinfunction "-_2") (pintype "passive"))
      (node (ref "C27") (pin "2") (pinfunction "2_2") (pintype "passive"))
      (node (ref "C28") (pin "2") (pinfunction "-_2") (pintype "passive"))
      (node (ref "C29") (pin "2") (pinfunction "2_2") (pintype "passive"))
      (node (ref "C3") (pin "2") (pinfunction "-_2") (pintype "passive"))
      (node (ref "C34") (pin "2") (pinfunction "2_2") (pintype "passive"))
      (node (ref "C35") (pin "2") (pinfunction "2_2") (pintype "passive"))
      (node (ref "C36") (pin "2") (pinfunction "2_2") (pintype "passive"))
      (node (ref "C37") (pin "2") (pinfunction "2_2") (pintype "passive"))
      (node (ref "C38") (pin "2") (pinfunction "2_2") (pintype "passive"))
      (node (ref "C39") (pin "2") (pinfunction "2_2") (pintype "passive"))
      (node (ref "C4") (pin "1") (pinfunction "1_1") (pintype "passive"))
      (node (ref "C40") (pin "2") (pinfunction "2_2") (pintype "passive"))
      (node (ref "C41") (pin "2") (pinfunction "2_2") (pintype "passive"))
      (node (ref "C42") (pin "2") (pinfunction "2_2") (pintype "passive"))
      (node (ref "C43") (pin "2") (pinfunction "2_2") (pintype "passive"))
      (node (ref "C44") (pin "2") (pinfunction "2_2") (pintype "passive"))
      (node (ref "C45") (pin "2") (pinfunction "2_2") (pintype "passive"))
      (node (ref "C5") (pin "1") (pinfunction "1_1") (pintype "passive"))
      (node (ref "C7") (pin "2") (pinfunction "2_2") (pintype "passive"))
      (node (ref "C8") (pin "2") (pinfunction "2_2") (pintype "passive"))
      (node (ref "CONN2") (pin "P$1") (pinfunction "P_P$1") (pintype "bidirectional"))
      (node (ref "IC1") (pin "4") (pinfunction "GND_4") (pintype "bidirectional"))
      (node (ref "IC2") (pin "4") (pinfunction "GND_4") (pintype "bidirectional"))
      (node (ref "IC3") (pin "4") (pinfunction "GND_4") (pintype "bidirectional"))
      (node (ref "IC4") (pin "4") (pinfunction "GND_4") (pintype "bidirectional"))
      (node (ref "IC5") (pin "4") (pinfunction "GND_4") (pintype "bidirectional"))
      (node (ref "JP1") (pin "6") (pinfunction "6_6") (pintype "passive"))
      (node (ref "JP2") (pin "6") (pinfunction "6_6") (pintype "passive"))
      (node (ref "JP3") (pin "6") (pinfunction "6_6") (pintype "passive"))
      (node (ref "JP4") (pin "6") (pinfunction "6_6") (pintype "passive"))
      (node (ref "JP5") (pin "6") (pinfunction "6_6") (pintype "passive"))
      (node (ref "JP6") (pin "4") (pinfunction "4_4") (pintype "passive"))
      (node (ref "R10") (pin "1") (pinfunction "1_1") (pintype "passive"))
      (node (ref "R12") (pin "1") (pinfunction "1_1") (pintype "passive"))
      (node (ref "S1") (pin "1") (pinfunction "1_1") (pintype "passive"))
      (node (ref "S2") (pin "1") (pinfunction "1_1") (pintype "passive"))
      (node (ref "SB10") (pin "R1") (pinfunction "P$2_R1") (pintype "passive"))
      (node (ref "SB10") (pin "R2") (pinfunction "P$2_R2") (pintype "passive"))
      (node (ref "SB11") (pin "R1") (pinfunction "P$2_R1") (pintype "passive"))
      (node (ref "SB11") (pin "R2") (pinfunction "P$2_R2") (pintype "passive"))
      (node (ref "SB16") (pin "R1") (pinfunction "P$2_R1") (pintype "passive"))
      (node (ref "SB16") (pin "R2") (pinfunction "P$2_R2") (pintype "passive"))
      (node (ref "SB9") (pin "R1") (pinfunction "P$2_R1") (pintype "passive"))
      (node (ref "SB9") (pin "R2") (pinfunction "P$2_R2") (pintype "passive"))
      (node (ref "SOCKET1") (pin "A15") (pinfunction "GND_A15") (pintype "input"))
      (node (ref "SOCKET1") (pin "A16") (pinfunction "GND_A16") (pintype "input"))
      (node (ref "SOCKET1") (pin "A19") (pinfunction "GND_A19") (pintype "input"))
      (node (ref "SOCKET1") (pin "A20") (pinfunction "GND_A20") (pintype "input"))
      (node (ref "SOCKET1") (pin "A23") (pinfunction "GND_A23") (pintype "input"))
      (node (ref "SOCKET1") (pin "A24") (pinfunction "GND_A24") (pintype "input"))
      (node (ref "SOCKET1") (pin "A27") (pinfunction "GND_A27") (pintype "input"))
      (node (ref "SOCKET1") (pin "A28") (pinfunction "GND_A28") (pintype "input"))
      (node (ref "SOCKET1") (pin "A31") (pinfunction "GND_A31") (pintype "input"))
      (node (ref "SOCKET1") (pin "A32") (pinfunction "GND_A32") (pintype "input"))
      (node (ref "SOCKET1") (pin "A35") (pinfunction "GND_A35") (pintype "input"))
      (node (ref "SOCKET1") (pin "A36") (pinfunction "GND_A36") (pintype "input"))
      (node (ref "SOCKET1") (pin "A39") (pinfunction "GND_A39") (pintype "input"))
      (node (ref "SOCKET1") (pin "A4") (pinfunction "GND_A4") (pintype "input"))
      (node (ref "SOCKET1") (pin "A40") (pinfunction "GND_A40") (pintype "input"))
      (node (ref "SOCKET1") (pin "A43") (pinfunction "GND_A43") (pintype "input"))
      (node (ref "SOCKET1") (pin "A44") (pinfunction "GND_A44") (pintype "input"))
      (node (ref "SOCKET1") (pin "A47") (pinfunction "GND_A47") (pintype "input"))
      (node (ref "SOCKET1") (pin "A48") (pinfunction "GND_A48") (pintype "input"))
      (node (ref "SOCKET1") (pin "B13") (pinfunction "GND_B13") (pintype "input"))
      (node (ref "SOCKET1") (pin "B14") (pinfunction "GND_B14") (pintype "input"))
      (node (ref "SOCKET1") (pin "B17") (pinfunction "GND_B17") (pintype "input"))
      (node (ref "SOCKET1") (pin "B18") (pinfunction "GND_B18") (pintype "input"))
      (node (ref "SOCKET1") (pin "B21") (pinfunction "GND_B21") (pintype "input"))
      (node (ref "SOCKET1") (pin "B22") (pinfunction "GND_B22") (pintype "input"))
      (node (ref "SOCKET1") (pin "B25") (pinfunction "GND_B25") (pintype "input"))
      (node (ref "SOCKET1") (pin "B26") (pinfunction "GND_B26") (pintype "input"))
      (node (ref "SOCKET1") (pin "B29") (pinfunction "GND_B29") (pintype "input"))
      (node (ref "SOCKET1") (pin "B30") (pinfunction "GND_B30") (pintype "input"))
      (node (ref "SOCKET1") (pin "B33") (pinfunction "GND_B33") (pintype "input"))
      (node (ref "SOCKET1") (pin "B34") (pinfunction "GND_B34") (pintype "input"))
      (node (ref "SOCKET1") (pin "B37") (pinfunction "GND_B37") (pintype "input"))
      (node (ref "SOCKET1") (pin "B38") (pinfunction "GND_B38") (pintype "input"))
      (node (ref "SOCKET1") (pin "B4") (pinfunction "GND_B4") (pintype "input"))
      (node (ref "SOCKET1") (pin "B41") (pinfunction "GND_B41") (pintype "input"))
      (node (ref "SOCKET1") (pin "B42") (pinfunction "GND_B42") (pintype "input"))
      (node (ref "SOCKET1") (pin "B45") (pinfunction "GND_B45") (pintype "input"))
      (node (ref "SOCKET1") (pin "B46") (pinfunction "GND_B46") (pintype "input"))
      (node (ref "SOCKET1") (pin "B49") (pinfunction "GND/PRSNT2#_B49") (pintype "input"))
      (node (ref "SOCKET1") (pin "B7") (pinfunction "GND_B7") (pintype "input"))
      (node (ref "SOCKET2") (pin "A15") (pinfunction "GND_A15") (pintype "input"))
      (node (ref "SOCKET2") (pin "A16") (pinfunction "GND_A16") (pintype "input"))
      (node (ref "SOCKET2") (pin "A19") (pinfunction "GND_A19") (pintype "input"))
      (node (ref "SOCKET2") (pin "A20") (pinfunction "GND_A20") (pintype "input"))
      (node (ref "SOCKET2") (pin "A23") (pinfunction "GND_A23") (pintype "input"))
      (node (ref "SOCKET2") (pin "A24") (pinfunction "GND_A24") (pintype "input"))
      (node (ref "SOCKET2") (pin "A27") (pinfunction "GND_A27") (pintype "input"))
      (node (ref "SOCKET2") (pin "A28") (pinfunction "GND_A28") (pintype "input"))
      (node (ref "SOCKET2") (pin "A31") (pinfunction "GND_A31") (pintype "input"))
      (node (ref "SOCKET2") (pin "A32") (pinfunction "GND_A32") (pintype "input"))
      (node (ref "SOCKET2") (pin "A35") (pinfunction "GND_A35") (pintype "input"))
      (node (ref "SOCKET2") (pin "A36") (pinfunction "GND_A36") (pintype "input"))
      (node (ref "SOCKET2") (pin "A39") (pinfunction "GND_A39") (pintype "input"))
      (node (ref "SOCKET2") (pin "A4") (pinfunction "GND_A4") (pintype "input"))
      (node (ref "SOCKET2") (pin "A40") (pinfunction "GND_A40") (pintype "input"))
      (node (ref "SOCKET2") (pin "A43") (pinfunction "GND_A43") (pintype "input"))
      (node (ref "SOCKET2") (pin "A44") (pinfunction "GND_A44") (pintype "input"))
      (node (ref "SOCKET2") (pin "A47") (pinfunction "GND_A47") (pintype "input"))
      (node (ref "SOCKET2") (pin "A48") (pinfunction "GND_A48") (pintype "input"))
      (node (ref "SOCKET2") (pin "B13") (pinfunction "GND_B13") (pintype "input"))
      (node (ref "SOCKET2") (pin "B14") (pinfunction "GND_B14") (pintype "input"))
      (node (ref "SOCKET2") (pin "B17") (pinfunction "GND_B17") (pintype "input"))
      (node (ref "SOCKET2") (pin "B18") (pinfunction "GND_B18") (pintype "input"))
      (node (ref "SOCKET2") (pin "B21") (pinfunction "GND_B21") (pintype "input"))
      (node (ref "SOCKET2") (pin "B22") (pinfunction "GND_B22") (pintype "input"))
      (node (ref "SOCKET2") (pin "B25") (pinfunction "GND_B25") (pintype "input"))
      (node (ref "SOCKET2") (pin "B26") (pinfunction "GND_B26") (pintype "input"))
      (node (ref "SOCKET2") (pin "B29") (pinfunction "GND_B29") (pintype "input"))
      (node (ref "SOCKET2") (pin "B30") (pinfunction "GND_B30") (pintype "input"))
      (node (ref "SOCKET2") (pin "B33") (pinfunction "GND_B33") (pintype "input"))
      (node (ref "SOCKET2") (pin "B34") (pinfunction "GND_B34") (pintype "input"))
      (node (ref "SOCKET2") (pin "B37") (pinfunction "GND_B37") (pintype "input"))
      (node (ref "SOCKET2") (pin "B38") (pinfunction "GND_B38") (pintype "input"))
      (node (ref "SOCKET2") (pin "B4") (pinfunction "GND_B4") (pintype "input"))
      (node (ref "SOCKET2") (pin "B41") (pinfunction "GND_B41") (pintype "input"))
      (node (ref "SOCKET2") (pin "B42") (pinfunction "GND_B42") (pintype "input"))
      (node (ref "SOCKET2") (pin "B45") (pinfunction "GND_B45") (pintype "input"))
      (node (ref "SOCKET2") (pin "B46") (pinfunction "GND_B46") (pintype "input"))
      (node (ref "SOCKET2") (pin "B49") (pinfunction "GND/PRSNT2#_B49") (pintype "input"))
      (node (ref "SOCKET2") (pin "B7") (pinfunction "GND_B7") (pintype "input"))
      (node (ref "SOCKET3") (pin "A15") (pinfunction "GND_A15") (pintype "input"))
      (node (ref "SOCKET3") (pin "A16") (pinfunction "GND_A16") (pintype "input"))
      (node (ref "SOCKET3") (pin "A19") (pinfunction "GND_A19") (pintype "input"))
      (node (ref "SOCKET3") (pin "A20") (pinfunction "GND_A20") (pintype "input"))
      (node (ref "SOCKET3") (pin "A23") (pinfunction "GND_A23") (pintype "input"))
      (node (ref "SOCKET3") (pin "A24") (pinfunction "GND_A24") (pintype "input"))
      (node (ref "SOCKET3") (pin "A27") (pinfunction "GND_A27") (pintype "input"))
      (node (ref "SOCKET3") (pin "A28") (pinfunction "GND_A28") (pintype "input"))
      (node (ref "SOCKET3") (pin "A31") (pinfunction "GND_A31") (pintype "input"))
      (node (ref "SOCKET3") (pin "A32") (pinfunction "GND_A32") (pintype "input"))
      (node (ref "SOCKET3") (pin "A35") (pinfunction "GND_A35") (pintype "input"))
      (node (ref "SOCKET3") (pin "A36") (pinfunction "GND_A36") (pintype "input"))
      (node (ref "SOCKET3") (pin "A39") (pinfunction "GND_A39") (pintype "input"))
      (node (ref "SOCKET3") (pin "A4") (pinfunction "GND_A4") (pintype "input"))
      (node (ref "SOCKET3") (pin "A40") (pinfunction "GND_A40") (pintype "input"))
      (node (ref "SOCKET3") (pin "A43") (pinfunction "GND_A43") (pintype "input"))
      (node (ref "SOCKET3") (pin "A44") (pinfunction "GND_A44") (pintype "input"))
      (node (ref "SOCKET3") (pin "A47") (pinfunction "GND_A47") (pintype "input"))
      (node (ref "SOCKET3") (pin "A48") (pinfunction "GND_A48") (pintype "input"))
      (node (ref "SOCKET3") (pin "B13") (pinfunction "GND_B13") (pintype "input"))
      (node (ref "SOCKET3") (pin "B14") (pinfunction "GND_B14") (pintype "input"))
      (node (ref "SOCKET3") (pin "B17") (pinfunction "GND_B17") (pintype "input"))
      (node (ref "SOCKET3") (pin "B18") (pinfunction "GND_B18") (pintype "input"))
      (node (ref "SOCKET3") (pin "B21") (pinfunction "GND_B21") (pintype "input"))
      (node (ref "SOCKET3") (pin "B22") (pinfunction "GND_B22") (pintype "input"))
      (node (ref "SOCKET3") (pin "B25") (pinfunction "GND_B25") (pintype "input"))
      (node (ref "SOCKET3") (pin "B26") (pinfunction "GND_B26") (pintype "input"))
      (node (ref "SOCKET3") (pin "B29") (pinfunction "GND_B29") (pintype "input"))
      (node (ref "SOCKET3") (pin "B30") (pinfunction "GND_B30") (pintype "input"))
      (node (ref "SOCKET3") (pin "B33") (pinfunction "GND_B33") (pintype "input"))
      (node (ref "SOCKET3") (pin "B34") (pinfunction "GND_B34") (pintype "input"))
      (node (ref "SOCKET3") (pin "B37") (pinfunction "GND_B37") (pintype "input"))
      (node (ref "SOCKET3") (pin "B38") (pinfunction "GND_B38") (pintype "input"))
      (node (ref "SOCKET3") (pin "B4") (pinfunction "GND_B4") (pintype "input"))
      (node (ref "SOCKET3") (pin "B41") (pinfunction "GND_B41") (pintype "input"))
      (node (ref "SOCKET3") (pin "B42") (pinfunction "GND_B42") (pintype "input"))
      (node (ref "SOCKET3") (pin "B45") (pinfunction "GND_B45") (pintype "input"))
      (node (ref "SOCKET3") (pin "B46") (pinfunction "GND_B46") (pintype "input"))
      (node (ref "SOCKET3") (pin "B49") (pinfunction "GND/PRSNT2#_B49") (pintype "input"))
      (node (ref "SOCKET3") (pin "B7") (pinfunction "GND_B7") (pintype "input"))
      (node (ref "SOCKET4") (pin "A15") (pinfunction "GND_A15") (pintype "input"))
      (node (ref "SOCKET4") (pin "A16") (pinfunction "GND_A16") (pintype "input"))
      (node (ref "SOCKET4") (pin "A19") (pinfunction "GND_A19") (pintype "input"))
      (node (ref "SOCKET4") (pin "A20") (pinfunction "GND_A20") (pintype "input"))
      (node (ref "SOCKET4") (pin "A23") (pinfunction "GND_A23") (pintype "input"))
      (node (ref "SOCKET4") (pin "A24") (pinfunction "GND_A24") (pintype "input"))
      (node (ref "SOCKET4") (pin "A27") (pinfunction "GND_A27") (pintype "input"))
      (node (ref "SOCKET4") (pin "A28") (pinfunction "GND_A28") (pintype "input"))
      (node (ref "SOCKET4") (pin "A31") (pinfunction "GND_A31") (pintype "input"))
      (node (ref "SOCKET4") (pin "A32") (pinfunction "GND_A32") (pintype "input"))
      (node (ref "SOCKET4") (pin "A35") (pinfunction "GND_A35") (pintype "input"))
      (node (ref "SOCKET4") (pin "A36") (pinfunction "GND_A36") (pintype "input"))
      (node (ref "SOCKET4") (pin "A39") (pinfunction "GND_A39") (pintype "input"))
      (node (ref "SOCKET4") (pin "A4") (pinfunction "GND_A4") (pintype "input"))
      (node (ref "SOCKET4") (pin "A40") (pinfunction "GND_A40") (pintype "input"))
      (node (ref "SOCKET4") (pin "A43") (pinfunction "GND_A43") (pintype "input"))
      (node (ref "SOCKET4") (pin "A44") (pinfunction "GND_A44") (pintype "input"))
      (node (ref "SOCKET4") (pin "A47") (pinfunction "GND_A47") (pintype "input"))
      (node (ref "SOCKET4") (pin "A48") (pinfunction "GND_A48") (pintype "input"))
      (node (ref "SOCKET4") (pin "B13") (pinfunction "GND_B13") (pintype "input"))
      (node (ref "SOCKET4") (pin "B14") (pinfunction "GND_B14") (pintype "input"))
      (node (ref "SOCKET4") (pin "B17") (pinfunction "GND_B17") (pintype "input"))
      (node (ref "SOCKET4") (pin "B18") (pinfunction "GND_B18") (pintype "input"))
      (node (ref "SOCKET4") (pin "B21") (pinfunction "GND_B21") (pintype "input"))
      (node (ref "SOCKET4") (pin "B22") (pinfunction "GND_B22") (pintype "input"))
      (node (ref "SOCKET4") (pin "B25") (pinfunction "GND_B25") (pintype "input"))
      (node (ref "SOCKET4") (pin "B26") (pinfunction "GND_B26") (pintype "input"))
      (node (ref "SOCKET4") (pin "B29") (pinfunction "GND_B29") (pintype "input"))
      (node (ref "SOCKET4") (pin "B30") (pinfunction "GND_B30") (pintype "input"))
      (node (ref "SOCKET4") (pin "B33") (pinfunction "GND_B33") (pintype "input"))
      (node (ref "SOCKET4") (pin "B34") (pinfunction "GND_B34") (pintype "input"))
      (node (ref "SOCKET4") (pin "B37") (pinfunction "GND_B37") (pintype "input"))
      (node (ref "SOCKET4") (pin "B38") (pinfunction "GND_B38") (pintype "input"))
      (node (ref "SOCKET4") (pin "B4") (pinfunction "GND_B4") (pintype "input"))
      (node (ref "SOCKET4") (pin "B41") (pinfunction "GND_B41") (pintype "input"))
      (node (ref "SOCKET4") (pin "B42") (pinfunction "GND_B42") (pintype "input"))
      (node (ref "SOCKET4") (pin "B45") (pinfunction "GND_B45") (pintype "input"))
      (node (ref "SOCKET4") (pin "B46") (pinfunction "GND_B46") (pintype "input"))
      (node (ref "SOCKET4") (pin "B49") (pinfunction "GND/PRSNT2#_B49") (pintype "input"))
      (node (ref "SOCKET4") (pin "B7") (pinfunction "GND_B7") (pintype "input"))
      (node (ref "SOCKET5") (pin "A15") (pinfunction "GND_A15") (pintype "input"))
      (node (ref "SOCKET5") (pin "A16") (pinfunction "GND_A16") (pintype "input"))
      (node (ref "SOCKET5") (pin "A19") (pinfunction "GND_A19") (pintype "input"))
      (node (ref "SOCKET5") (pin "A20") (pinfunction "GND_A20") (pintype "input"))
      (node (ref "SOCKET5") (pin "A23") (pinfunction "GND_A23") (pintype "input"))
      (node (ref "SOCKET5") (pin "A24") (pinfunction "GND_A24") (pintype "input"))
      (node (ref "SOCKET5") (pin "A27") (pinfunction "GND_A27") (pintype "input"))
      (node (ref "SOCKET5") (pin "A28") (pinfunction "GND_A28") (pintype "input"))
      (node (ref "SOCKET5") (pin "A31") (pinfunction "GND_A31") (pintype "input"))
      (node (ref "SOCKET5") (pin "A32") (pinfunction "GND_A32") (pintype "input"))
      (node (ref "SOCKET5") (pin "A35") (pinfunction "GND_A35") (pintype "input"))
      (node (ref "SOCKET5") (pin "A36") (pinfunction "GND_A36") (pintype "input"))
      (node (ref "SOCKET5") (pin "A39") (pinfunction "GND_A39") (pintype "input"))
      (node (ref "SOCKET5") (pin "A4") (pinfunction "GND_A4") (pintype "input"))
      (node (ref "SOCKET5") (pin "A40") (pinfunction "GND_A40") (pintype "input"))
      (node (ref "SOCKET5") (pin "A43") (pinfunction "GND_A43") (pintype "input"))
      (node (ref "SOCKET5") (pin "A44") (pinfunction "GND_A44") (pintype "input"))
      (node (ref "SOCKET5") (pin "A47") (pinfunction "GND_A47") (pintype "input"))
      (node (ref "SOCKET5") (pin "A48") (pinfunction "GND_A48") (pintype "input"))
      (node (ref "SOCKET5") (pin "B13") (pinfunction "GND_B13") (pintype "input"))
      (node (ref "SOCKET5") (pin "B14") (pinfunction "GND_B14") (pintype "input"))
      (node (ref "SOCKET5") (pin "B17") (pinfunction "GND_B17") (pintype "input"))
      (node (ref "SOCKET5") (pin "B18") (pinfunction "GND_B18") (pintype "input"))
      (node (ref "SOCKET5") (pin "B21") (pinfunction "GND_B21") (pintype "input"))
      (node (ref "SOCKET5") (pin "B22") (pinfunction "GND_B22") (pintype "input"))
      (node (ref "SOCKET5") (pin "B25") (pinfunction "GND_B25") (pintype "input"))
      (node (ref "SOCKET5") (pin "B26") (pinfunction "GND_B26") (pintype "input"))
      (node (ref "SOCKET5") (pin "B29") (pinfunction "GND_B29") (pintype "input"))
      (node (ref "SOCKET5") (pin "B30") (pinfunction "GND_B30") (pintype "input"))
      (node (ref "SOCKET5") (pin "B33") (pinfunction "GND_B33") (pintype "input"))
      (node (ref "SOCKET5") (pin "B34") (pinfunction "GND_B34") (pintype "input"))
      (node (ref "SOCKET5") (pin "B37") (pinfunction "GND_B37") (pintype "input"))
      (node (ref "SOCKET5") (pin "B38") (pinfunction "GND_B38") (pintype "input"))
      (node (ref "SOCKET5") (pin "B4") (pinfunction "GND_B4") (pintype "input"))
      (node (ref "SOCKET5") (pin "B41") (pinfunction "GND_B41") (pintype "input"))
      (node (ref "SOCKET5") (pin "B42") (pinfunction "GND_B42") (pintype "input"))
      (node (ref "SOCKET5") (pin "B45") (pinfunction "GND_B45") (pintype "input"))
      (node (ref "SOCKET5") (pin "B46") (pinfunction "GND_B46") (pintype "input"))
      (node (ref "SOCKET5") (pin "B49") (pinfunction "GND/PRSNT2#_B49") (pintype "input"))
      (node (ref "SOCKET5") (pin "B7") (pinfunction "GND_B7") (pintype "input"))
      (node (ref "U$11") (pin "PLED-") (pinfunction "PLED-_PLED-") (pintype "bidirectional"))
      (node (ref "U$11") (pin "PWR_1") (pinfunction "PWR1_PWR_1") (pintype "bidirectional"))
      (node (ref "U$11") (pin "RST_1") (pinfunction "RST1_RST_1") (pintype "bidirectional"))
      (node (ref "U$12") (pin "2") (pinfunction "GND_2") (pintype "bidirectional"))
      (node (ref "U$13") (pin "15") (pinfunction "GND_15") (pintype "bidirectional"))
      (node (ref "U$13") (pin "17") (pinfunction "GND_17") (pintype "bidirectional"))
      (node (ref "U$13") (pin "18") (pinfunction "GND_18") (pintype "bidirectional"))
      (node (ref "U$13") (pin "19") (pinfunction "GND_19") (pintype "bidirectional"))
      (node (ref "U$13") (pin "24") (pinfunction "GND_24") (pintype "bidirectional"))
      (node (ref "U$13") (pin "3") (pinfunction "GND_3") (pintype "bidirectional"))
      (node (ref "U$13") (pin "5") (pinfunction "GND_5") (pintype "bidirectional"))
      (node (ref "U$13") (pin "7") (pinfunction "GND_7") (pintype "bidirectional"))
      (node (ref "U$15") (pin "BGND") (pinfunction "GND_BGND") (pintype "bidirectional"))
      (node (ref "U$15") (pin "TGND") (pinfunction "GND_TGND") (pintype "bidirectional"))
      (node (ref "U$18") (pin "1") (pinfunction "GND_1") (pintype "input"))
      (node (ref "U$2") (pin "15") (pinfunction "15_15") (pintype "bidirectional"))
      (node (ref "U$2") (pin "22") (pinfunction "22_22") (pintype "bidirectional"))
      (node (ref "U$2") (pin "29") (pinfunction "29_29") (pintype "bidirectional"))
      (node (ref "U$2") (pin "36") (pinfunction "36_36") (pintype "bidirectional"))
      (node (ref "U$2") (pin "45") (pinfunction "45_45") (pintype "bidirectional"))
      (node (ref "U$2") (pin "5") (pinfunction "5_5") (pintype "bidirectional"))
      (node (ref "U$2") (pin "52") (pinfunction "52_52") (pintype "bidirectional"))
      (node (ref "U$2") (pin "59") (pinfunction "59_59") (pintype "bidirectional"))
      (node (ref "U$2") (pin "66") (pinfunction "66_66") (pintype "bidirectional"))
      (node (ref "U$2") (pin "76") (pinfunction "76_76") (pintype "bidirectional"))
      (node (ref "U$3") (pin "10") (pinfunction "10_10") (pintype "bidirectional"))
      (node (ref "U$3") (pin "14") (pinfunction "14_14") (pintype "bidirectional"))
      (node (ref "U$3") (pin "17") (pinfunction "17_17") (pintype "bidirectional"))
      (node (ref "U$3") (pin "20") (pinfunction "20_20") (pintype "bidirectional"))
      (node (ref "U$3") (pin "24") (pinfunction "24_24") (pintype "bidirectional"))
      (node (ref "U$3") (pin "27") (pinfunction "27_27") (pintype "bidirectional"))
      (node (ref "U$3") (pin "30") (pinfunction "30_30") (pintype "bidirectional"))
      (node (ref "U$3") (pin "34") (pinfunction "34_34") (pintype "bidirectional"))
      (node (ref "U$3") (pin "37") (pinfunction "37_37") (pintype "bidirectional"))
      (node (ref "U$3") (pin "4") (pinfunction "4_4") (pintype "bidirectional"))
      (node (ref "U$3") (pin "40") (pinfunction "40_40") (pintype "bidirectional"))
      (node (ref "U$3") (pin "51") (pinfunction "51_51") (pintype "bidirectional"))
      (node (ref "U$3") (pin "54") (pinfunction "54_54") (pintype "bidirectional"))
      (node (ref "U$3") (pin "57") (pinfunction "57_57") (pintype "bidirectional"))
      (node (ref "U$3") (pin "61") (pinfunction "61_61") (pintype "bidirectional"))
      (node (ref "U$3") (pin "64") (pinfunction "64_64") (pintype "bidirectional"))
      (node (ref "U$3") (pin "67") (pinfunction "67_67") (pintype "bidirectional"))
      (node (ref "U$3") (pin "7") (pinfunction "7_7") (pintype "bidirectional"))
      (node (ref "U$3") (pin "71") (pinfunction "71_71") (pintype "bidirectional"))
      (node (ref "U$3") (pin "74") (pinfunction "74_74") (pintype "bidirectional"))
      (node (ref "U$3") (pin "77") (pinfunction "77_77") (pintype "bidirectional"))
      (node (ref "U$3") (pin "81") (pinfunction "81_81") (pintype "bidirectional"))
      (node (ref "U$3") (pin "84") (pinfunction "84_84") (pintype "bidirectional"))
      (node (ref "U$3") (pin "87") (pinfunction "87_87") (pintype "bidirectional"))
      (node (ref "U$6") (pin "2") (pinfunction "GND_2") (pintype "bidirectional"))
    )
    (net (code "133") (name "Net-(C6-Pad2)") (class "Default")
      (node (ref "C6") (pin "2") (pinfunction "2_2") (pintype "passive"))
      (node (ref "U$3") (pin "76") (pinfunction "76_76") (pintype "bidirectional"))
    )
    (net (code "134") (name "Net-(C9-Pad2)") (class "Default")
      (node (ref "C9") (pin "2") (pinfunction "2_2") (pintype "passive"))
      (node (ref "U$3") (pin "75") (pinfunction "75_75") (pintype "bidirectional"))
    )
    (net (code "135") (name "Net-(C10-Pad2)") (class "Default")
      (node (ref "C10") (pin "2") (pinfunction "2_2") (pintype "passive"))
      (node (ref "U$3") (pin "73") (pinfunction "73_73") (pintype "bidirectional"))
    )
    (net (code "136") (name "Net-(C11-Pad2)") (class "Default")
      (node (ref "C11") (pin "2") (pinfunction "2_2") (pintype "passive"))
      (node (ref "U$3") (pin "72") (pinfunction "72_72") (pintype "bidirectional"))
    )
    (net (code "137") (name "Net-(C23-Pad1)") (class "Default")
      (node (ref "C23") (pin "1") (pinfunction "1_1") (pintype "passive"))
      (node (ref "U$3") (pin "25") (pinfunction "25_25") (pintype "bidirectional"))
    )
    (net (code "138") (name "Net-(C24-Pad1)") (class "Default")
      (node (ref "C24") (pin "1") (pinfunction "1_1") (pintype "passive"))
      (node (ref "U$3") (pin "26") (pinfunction "26_26") (pintype "bidirectional"))
    )
    (net (code "139") (name "Net-(C25-Pad1)") (class "Default")
      (node (ref "C25") (pin "1") (pinfunction "1_1") (pintype "passive"))
      (node (ref "U$3") (pin "28") (pinfunction "28_28") (pintype "bidirectional"))
    )
    (net (code "140") (name "Net-(C26-Pad1)") (class "Default")
      (node (ref "C26") (pin "1") (pinfunction "1_1") (pintype "passive"))
      (node (ref "U$3") (pin "29") (pinfunction "29_29") (pintype "bidirectional"))
    )
    (net (code "141") (name "Net-(C30-Pad1)") (class "Default")
      (node (ref "C30") (pin "1") (pinfunction "1_1") (pintype "passive"))
      (node (ref "U$3") (pin "66") (pinfunction "66_66") (pintype "bidirectional"))
    )
    (net (code "142") (name "Net-(C31-Pad1)") (class "Default")
      (node (ref "C31") (pin "1") (pinfunction "1_1") (pintype "passive"))
      (node (ref "U$3") (pin "65") (pinfunction "65_65") (pintype "bidirectional"))
    )
    (net (code "143") (name "Net-(C32-Pad1)") (class "Default")
      (node (ref "C32") (pin "1") (pinfunction "1_1") (pintype "passive"))
      (node (ref "U$3") (pin "63") (pinfunction "63_63") (pintype "bidirectional"))
    )
    (net (code "144") (name "Net-(C33-Pad1)") (class "Default")
      (node (ref "C33") (pin "1") (pinfunction "1_1") (pintype "passive"))
      (node (ref "U$3") (pin "62") (pinfunction "62_62") (pintype "bidirectional"))
    )
    (net (code "145") (name "Net-(C46-Pad1)") (class "Default")
      (node (ref "C46") (pin "1") (pinfunction "1_1") (pintype "passive"))
      (node (ref "CH1") (pin "1") (pinfunction "1_1") (pintype "passive"))
    )
    (net (code "146") (name "Net-(C47-Pad1)") (class "Default")
      (node (ref "C47") (pin "1") (pinfunction "1_1") (pintype "passive"))
      (node (ref "CH1") (pin "4") (pinfunction "4_4") (pintype "passive"))
    )
    (net (code "147") (name "Net-(C48-Pad1)") (class "Default")
      (node (ref "C48") (pin "1") (pinfunction "1_1") (pintype "passive"))
      (node (ref "CH2") (pin "1") (pinfunction "1_1") (pintype "passive"))
    )
    (net (code "148") (name "Net-(C49-Pad1)") (class "Default")
      (node (ref "C49") (pin "1") (pinfunction "1_1") (pintype "passive"))
      (node (ref "CH2") (pin "4") (pinfunction "4_4") (pintype "passive"))
    )
    (net (code "149") (name "Net-(CH1-Pad2)") (class "Default")
      (node (ref "CH1") (pin "2") (pinfunction "2_2") (pintype "passive"))
      (node (ref "U$3") (pin "15") (pinfunction "15_15") (pintype "bidirectional"))
    )
    (net (code "150") (name "Net-(CH1-Pad3)") (class "Default")
      (node (ref "CH1") (pin "3") (pinfunction "3_3") (pintype "passive"))
      (node (ref "U$3") (pin "16") (pinfunction "16_16") (pintype "bidirectional"))
    )
    (net (code "151") (name "Net-(CH2-Pad2)") (class "Default")
      (node (ref "CH2") (pin "2") (pinfunction "2_2") (pintype "passive"))
      (node (ref "U$3") (pin "18") (pinfunction "18_18") (pintype "bidirectional"))
    )
    (net (code "152") (name "Net-(CH2-Pad3)") (class "Default")
      (node (ref "CH2") (pin "3") (pinfunction "3_3") (pintype "passive"))
      (node (ref "U$3") (pin "19") (pinfunction "19_19") (pintype "bidirectional"))
    )
    (net (code "153") (name "Net-(IC1-1Y)") (class "Default")
      (node (ref "IC1") (pin "7") (pinfunction "1Y_7") (pintype "bidirectional"))
      (node (ref "RA2") (pin "3") (pinfunction "1_3") (pintype "passive"))
    )
    (net (code "154") (name "Net-(IC1-2Y)") (class "Default")
      (node (ref "IC1") (pin "5") (pinfunction "2Y_5") (pintype "bidirectional"))
      (node (ref "RA2") (pin "2") (pinfunction "1_2") (pintype "passive"))
    )
    (net (code "155") (name "Net-(IC1-3Y)") (class "Default")
      (node (ref "IC1") (pin "2") (pinfunction "3Y_2") (pintype "bidirectional"))
      (node (ref "RA2") (pin "1") (pinfunction "1_1") (pintype "passive"))
    )
    (net (code "156") (name "Net-(IC2-1Y)") (class "Default")
      (node (ref "IC2") (pin "7") (pinfunction "1Y_7") (pintype "bidirectional"))
      (node (ref "RA4") (pin "3") (pinfunction "1_3") (pintype "passive"))
    )
    (net (code "157") (name "Net-(IC2-2Y)") (class "Default")
      (node (ref "IC2") (pin "5") (pinfunction "2Y_5") (pintype "bidirectional"))
      (node (ref "RA4") (pin "2") (pinfunction "1_2") (pintype "passive"))
    )
    (net (code "158") (name "Net-(IC2-3Y)") (class "Default")
      (node (ref "IC2") (pin "2") (pinfunction "3Y_2") (pintype "bidirectional"))
      (node (ref "RA4") (pin "1") (pinfunction "1_1") (pintype "passive"))
    )
    (net (code "159") (name "Net-(IC3-1Y)") (class "Default")
      (node (ref "IC3") (pin "7") (pinfunction "1Y_7") (pintype "bidirectional"))
      (node (ref "RA6") (pin "3") (pinfunction "1_3") (pintype "passive"))
    )
    (net (code "160") (name "Net-(IC3-2Y)") (class "Default")
      (node (ref "IC3") (pin "5") (pinfunction "2Y_5") (pintype "bidirectional"))
      (node (ref "RA6") (pin "2") (pinfunction "1_2") (pintype "passive"))
    )
    (net (code "161") (name "Net-(IC3-3Y)") (class "Default")
      (node (ref "IC3") (pin "2") (pinfunction "3Y_2") (pintype "bidirectional"))
      (node (ref "RA6") (pin "1") (pinfunction "1_1") (pintype "passive"))
    )
    (net (code "162") (name "Net-(IC4-1Y)") (class "Default")
      (node (ref "IC4") (pin "7") (pinfunction "1Y_7") (pintype "bidirectional"))
      (node (ref "RA8") (pin "3") (pinfunction "1_3") (pintype "passive"))
    )
    (net (code "163") (name "Net-(IC4-2Y)") (class "Default")
      (node (ref "IC4") (pin "5") (pinfunction "2Y_5") (pintype "bidirectional"))
      (node (ref "RA8") (pin "2") (pinfunction "1_2") (pintype "passive"))
    )
    (net (code "164") (name "Net-(IC4-3Y)") (class "Default")
      (node (ref "IC4") (pin "2") (pinfunction "3Y_2") (pintype "bidirectional"))
      (node (ref "RA8") (pin "1") (pinfunction "1_1") (pintype "passive"))
    )
    (net (code "165") (name "Net-(IC5-1Y)") (class "Default")
      (node (ref "IC5") (pin "7") (pinfunction "1Y_7") (pintype "bidirectional"))
      (node (ref "RA10") (pin "3") (pinfunction "1_3") (pintype "passive"))
    )
    (net (code "166") (name "Net-(IC5-2Y)") (class "Default")
      (node (ref "IC5") (pin "5") (pinfunction "2Y_5") (pintype "bidirectional"))
      (node (ref "RA10") (pin "2") (pinfunction "1_2") (pintype "passive"))
    )
    (net (code "167") (name "Net-(IC5-3Y)") (class "Default")
      (node (ref "IC5") (pin "2") (pinfunction "3Y_2") (pintype "bidirectional"))
      (node (ref "RA10") (pin "1") (pinfunction "1_1") (pintype "passive"))
    )
    (net (code "168") (name "Net-(LED0_1-PadC)") (class "Default")
      (node (ref "LED0_1") (pin "C") (pinfunction "C_C") (pintype "passive"))
      (node (ref "R17") (pin "2") (pinfunction "2_2") (pintype "passive"))
    )
    (net (code "169") (name "Net-(LED1_1-PadC)") (class "Default")
      (node (ref "LED1_1") (pin "C") (pinfunction "C_C") (pintype "passive"))
      (node (ref "R19") (pin "2") (pinfunction "2_2") (pintype "passive"))
    )
    (net (code "170") (name "Net-(LED2_1-PadC)") (class "Default")
      (node (ref "LED2_1") (pin "C") (pinfunction "C_C") (pintype "passive"))
      (node (ref "R21") (pin "2") (pinfunction "2_2") (pintype "passive"))
    )
    (net (code "171") (name "Net-(LED3_1-PadC)") (class "Default")
      (node (ref "LED3_1") (pin "C") (pinfunction "C_C") (pintype "passive"))
      (node (ref "R23") (pin "2") (pinfunction "2_2") (pintype "passive"))
    )
    (net (code "172") (name "Net-(LED4_1-PadC)") (class "Default")
      (node (ref "LED4_1") (pin "C") (pinfunction "C_C") (pintype "passive"))
      (node (ref "R18") (pin "2") (pinfunction "2_2") (pintype "passive"))
    )
    (net (code "173") (name "Net-(R24-Pad1)") (class "Default")
      (node (ref "R24") (pin "1") (pinfunction "1_1") (pintype "passive"))
      (node (ref "U$11") (pin "PLED+") (pinfunction "PLED+_PLED+") (pintype "bidirectional"))
    )
    (net (code "174") (name "Net-(RA2A-2)") (class "Default")
      (node (ref "LRST_0") (pin "C") (pinfunction "C_C") (pintype "passive"))
      (node (ref "RA2") (pin "8") (pinfunction "2_8") (pintype "passive"))
    )
    (net (code "175") (name "Net-(RA2B-2)") (class "Default")
      (node (ref "LPRSNT_0") (pin "C") (pinfunction "C_C") (pintype "passive"))
      (node (ref "RA2") (pin "7") (pinfunction "2_7") (pintype "passive"))
    )
    (net (code "176") (name "Net-(RA2C-2)") (class "Default")
      (node (ref "LPWR_ON_0") (pin "C") (pinfunction "C_C") (pintype "passive"))
      (node (ref "RA2") (pin "6") (pinfunction "2_6") (pintype "passive"))
    )
    (net (code "177") (name "Net-(RA2D-2)") (class "Default")
      (node (ref "LED0_2") (pin "C") (pinfunction "C_C") (pintype "passive"))
      (node (ref "RA2") (pin "5") (pinfunction "2_5") (pintype "passive"))
    )
    (net (code "178") (name "Net-(RA4A-2)") (class "Default")
      (node (ref "LRST_1") (pin "C") (pinfunction "C_C") (pintype "passive"))
      (node (ref "RA4") (pin "8") (pinfunction "2_8") (pintype "passive"))
    )
    (net (code "179") (name "Net-(RA4B-2)") (class "Default")
      (node (ref "LPRSNT_1") (pin "C") (pinfunction "C_C") (pintype "passive"))
      (node (ref "RA4") (pin "7") (pinfunction "2_7") (pintype "passive"))
    )
    (net (code "180") (name "Net-(RA4C-2)") (class "Default")
      (node (ref "LPWR_ON_1") (pin "C") (pinfunction "C_C") (pintype "passive"))
      (node (ref "RA4") (pin "6") (pinfunction "2_6") (pintype "passive"))
    )
    (net (code "181") (name "Net-(RA4D-1)") (class "Default")
      (node (ref "LED1_2") (pin "C") (pinfunction "C_C") (pintype "passive"))
      (node (ref "RA4") (pin "4") (pinfunction "1_4") (pintype "passive"))
    )
    (net (code "182") (name "Net-(RA6A-2)") (class "Default")
      (node (ref "LRST_2") (pin "C") (pinfunction "C_C") (pintype "passive"))
      (node (ref "RA6") (pin "8") (pinfunction "2_8") (pintype "passive"))
    )
    (net (code "183") (name "Net-(RA6B-2)") (class "Default")
      (node (ref "LPRSNT_2") (pin "C") (pinfunction "C_C") (pintype "passive"))
      (node (ref "RA6") (pin "7") (pinfunction "2_7") (pintype "passive"))
    )
    (net (code "184") (name "Net-(RA6C-2)") (class "Default")
      (node (ref "LPWR_ON_2") (pin "C") (pinfunction "C_C") (pintype "passive"))
      (node (ref "RA6") (pin "6") (pinfunction "2_6") (pintype "passive"))
    )
    (net (code "185") (name "Net-(RA6D-1)") (class "Default")
      (node (ref "LED2_2") (pin "C") (pinfunction "C_C") (pintype "passive"))
      (node (ref "RA6") (pin "4") (pinfunction "1_4") (pintype "passive"))
    )
    (net (code "186") (name "Net-(RA8A-2)") (class "Default")
      (node (ref "LRST_3") (pin "C") (pinfunction "C_C") (pintype "passive"))
      (node (ref "RA8") (pin "8") (pinfunction "2_8") (pintype "passive"))
    )
    (net (code "187") (name "Net-(RA8B-2)") (class "Default")
      (node (ref "LPRSNT_3") (pin "C") (pinfunction "C_C") (pintype "passive"))
      (node (ref "RA8") (pin "7") (pinfunction "2_7") (pintype "passive"))
    )
    (net (code "188") (name "Net-(RA8C-2)") (class "Default")
      (node (ref "LPWR_ON_3") (pin "C") (pinfunction "C_C") (pintype "passive"))
      (node (ref "RA8") (pin "6") (pinfunction "2_6") (pintype "passive"))
    )
    (net (code "189") (name "Net-(RA8D-1)") (class "Default")
      (node (ref "LED3_2") (pin "C") (pinfunction "C_C") (pintype "passive"))
      (node (ref "RA8") (pin "4") (pinfunction "1_4") (pintype "passive"))
    )
    (net (code "190") (name "Net-(RA10A-2)") (class "Default")
      (node (ref "LRST_4") (pin "C") (pinfunction "C_C") (pintype "passive"))
      (node (ref "RA10") (pin "8") (pinfunction "2_8") (pintype "passive"))
    )
    (net (code "191") (name "Net-(RA10B-2)") (class "Default")
      (node (ref "LPRSNT_4") (pin "C") (pinfunction "C_C") (pintype "passive"))
      (node (ref "RA10") (pin "7") (pinfunction "2_7") (pintype "passive"))
    )
    (net (code "192") (name "Net-(RA10C-2)") (class "Default")
      (node (ref "LPWR_ON_4") (pin "C") (pinfunction "C_C") (pintype "passive"))
      (node (ref "RA10") (pin "6") (pinfunction "2_6") (pintype "passive"))
    )
    (net (code "193") (name "Net-(RA10D-1)") (class "Default")
      (node (ref "LED4_2") (pin "C") (pinfunction "C_C") (pintype "passive"))
      (node (ref "RA10") (pin "4") (pinfunction "1_4") (pintype "passive"))
    )
    (net (code "194") (name "Net-(SOCKET2-SVR_ID0)") (class "Default")
      (node (ref "SB9") (pin "L1") (pinfunction "P$1_L1") (pintype "passive"))
      (node (ref "SB9") (pin "L2") (pinfunction "P$1_L2") (pintype "passive"))
      (node (ref "SOCKET2") (pin "A5") (pinfunction "SVR_ID0_A5") (pintype "bidirectional"))
    )
    (net (code "195") (name "Net-(SOCKET3-SVR_ID1)") (class "Default")
      (node (ref "SB10") (pin "L1") (pinfunction "P$1_L1") (pintype "passive"))
      (node (ref "SB10") (pin "L2") (pinfunction "P$1_L2") (pintype "passive"))
      (node (ref "SOCKET3") (pin "A6") (pinfunction "SVR_ID1_A6") (pintype "bidirectional"))
    )
    (net (code "196") (name "Net-(SOCKET4-SVR_ID0)") (class "Default")
      (node (ref "SB11") (pin "L1") (pinfunction "P$1_L1") (pintype "passive"))
      (node (ref "SB11") (pin "L2") (pinfunction "P$1_L2") (pintype "passive"))
      (node (ref "SOCKET4") (pin "A5") (pinfunction "SVR_ID0_A5") (pintype "bidirectional"))
      (node (ref "SOCKET4") (pin "A6") (pinfunction "SVR_ID1_A6") (pintype "bidirectional"))
    )
    (net (code "197") (name "Net-(SOCKET5-SVR_ID2)") (class "Default")
      (node (ref "SB16") (pin "L1") (pinfunction "P$1_L1") (pintype "passive"))
      (node (ref "SB16") (pin "L2") (pinfunction "P$1_L2") (pintype "passive"))
      (node (ref "SOCKET5") (pin "A9") (pinfunction "SVR_ID2_A9") (pintype "bidirectional"))
    )
    (net (code "198") (name "Net-(U$6-ISET)") (class "Default")
      (node (ref "R10") (pin "2") (pinfunction "2_2") (pintype "passive"))
      (node (ref "U$6") (pin "3") (pinfunction "ISET_3") (pintype "bidirectional"))
    )
    (net (code "199") (name "Net-(U$6-OUT)") (class "Default")
      (node (ref "C8") (pin "1") (pinfunction "1_1") (pintype "passive"))
      (node (ref "SB12") (pin "L1") (pinfunction "P$1_L1") (pintype "passive"))
      (node (ref "SB12") (pin "L2") (pinfunction "P$1_L2") (pintype "passive"))
      (node (ref "U$6") (pin "1") (pinfunction "OUT_1") (pintype "bidirectional"))
    )
    (net (code "200") (name "Net-(U$11-HLED+)") (class "Default")
      (node (ref "R25") (pin "2") (pinfunction "2_2") (pintype "passive"))
      (node (ref "U$11") (pin "HDLED+") (pinfunction "HLED+_HDLED+") (pintype "bidirectional"))
    )
    (net (code "201") (name "Net-(U$12-ISET)") (class "Default")
      (node (ref "R12") (pin "2") (pinfunction "2_2") (pintype "passive"))
      (node (ref "U$12") (pin "3") (pinfunction "ISET_3") (pintype "bidirectional"))
    )
    (net (code "202") (name "Net-(U$12-OUT)") (class "Default")
      (node (ref "C2") (pin "1") (pinfunction "1_1") (pintype "passive"))
      (node (ref "SB13") (pin "L1") (pinfunction "P$1_L1") (pintype "passive"))
      (node (ref "SB13") (pin "L2") (pinfunction "P$1_L2") (pintype "passive"))
      (node (ref "U$12") (pin "1") (pinfunction "OUT_1") (pintype "bidirectional"))
    )
    (net (code "203") (name "Net-(U$15A-LGP)") (class "Default")
      (node (ref "R16") (pin "2") (pinfunction "2_2") (pintype "passive"))
      (node (ref "U$15") (pin "R10") (pinfunction "LGP_R10") (pintype "bidirectional"))
    )
    (net (code "204") (name "Net-(U$15A-LYP)") (class "Default")
      (node (ref "R15") (pin "2") (pinfunction "2_2") (pintype "passive"))
      (node (ref "U$15") (pin "R8") (pinfunction "LYP_R8") (pintype "bidirectional"))
    )
    (net (code "205") (name "Net-(U$15A-RCT)") (class "Default")
      (node (ref "C4") (pin "2") (pinfunction "2_2") (pintype "passive"))
      (node (ref "U$15") (pin "R6") (pinfunction "RCT_R6") (pintype "bidirectional"))
    )
    (net (code "206") (name "Net-(U$15A-TCT)") (class "Default")
      (node (ref "C5") (pin "2") (pinfunction "2_2") (pintype "passive"))
      (node (ref "U$15") (pin "R1") (pinfunction "TCT_R1") (pintype "bidirectional"))
    )
    (net (code "207") (name "unconnected-(C12-PadTACH)") (class "Default")
      (node (ref "C12") (pin "TACH") (pinfunction "TACH_TACH") (pintype "bidirectional"))
    )
    (net (code "208") (name "unconnected-(RA1-Pad1)") (class "Default")
      (node (ref "RA1") (pin "1") (pinfunction "1_1") (pintype "passive"))
    )
    (net (code "209") (name "unconnected-(RA3-Pad1)") (class "Default")
      (node (ref "RA3") (pin "1") (pinfunction "1_1") (pintype "passive"))
    )
    (net (code "210") (name "unconnected-(RA5-Pad1)") (class "Default")
      (node (ref "RA5") (pin "1") (pinfunction "1_1") (pintype "passive"))
    )
    (net (code "211") (name "unconnected-(RA7-Pad1)") (class "Default")
      (node (ref "RA7") (pin "1") (pinfunction "1_1") (pintype "passive"))
    )
    (net (code "212") (name "unconnected-(RA9-Pad1)") (class "Default")
      (node (ref "RA9") (pin "1") (pinfunction "1_1") (pintype "passive"))
    )
    (net (code "213") (name "unconnected-(RA11-Pad1)") (class "Default")
      (node (ref "RA11") (pin "1") (pinfunction "1_1") (pintype "passive"))
    )
    (net (code "214") (name "unconnected-(S1-Pad2)") (class "Default")
      (node (ref "S1") (pin "2") (pinfunction "2_2") (pintype "passive"))
    )
    (net (code "215") (name "unconnected-(S1-Pad3)") (class "Default")
      (node (ref "S1") (pin "3") (pinfunction "3_3") (pintype "passive"))
    )
    (net (code "216") (name "unconnected-(S2-Pad2)") (class "Default")
      (node (ref "S2") (pin "2") (pinfunction "2_2") (pintype "passive"))
    )
    (net (code "217") (name "unconnected-(S2-Pad3)") (class "Default")
      (node (ref "S2") (pin "3") (pinfunction "3_3") (pintype "passive"))
    )
    (net (code "218") (name "unconnected-(SOCKET1-GND{slash}SVR_ID4-PadA12)") (class "Default")
      (node (ref "SOCKET1") (pin "A12") (pinfunction "GND/SVR_ID4_A12") (pintype "bidirectional"))
    )
    (net (code "219") (name "unconnected-(SOCKET1-I2C_ALERT#-PadB12)") (class "Default")
      (node (ref "SOCKET1") (pin "B12") (pinfunction "I2C_ALERT#_B12") (pintype "bidirectional"))
    )
    (net (code "220") (name "unconnected-(SOCKET1-L0_N-PadA14)") (class "Default")
      (node (ref "SOCKET1") (pin "A14") (pinfunction "L0_N_A14") (pintype "bidirectional"))
    )
    (net (code "221") (name "unconnected-(SOCKET1-L1_N-PadB16)") (class "Default")
      (node (ref "SOCKET1") (pin "B16") (pinfunction "L1_N_B16") (pintype "bidirectional"))
    )
    (net (code "222") (name "unconnected-(SOCKET1-L1_P-PadB15)") (class "Default")
      (node (ref "SOCKET1") (pin "B15") (pinfunction "L1_P_B15") (pintype "bidirectional"))
    )
    (net (code "223") (name "unconnected-(SOCKET1-L2_N-PadA18)") (class "Default")
      (node (ref "SOCKET1") (pin "A18") (pinfunction "L2_N_A18") (pintype "bidirectional"))
    )
    (net (code "224") (name "unconnected-(SOCKET1-L2_P-PadA17)") (class "Default")
      (node (ref "SOCKET1") (pin "A17") (pinfunction "L2_P_A17") (pintype "bidirectional"))
    )
    (net (code "225") (name "unconnected-(SOCKET1-L3_N-PadB20)") (class "Default")
      (node (ref "SOCKET1") (pin "B20") (pinfunction "L3_N_B20") (pintype "bidirectional"))
    )
    (net (code "226") (name "unconnected-(SOCKET1-L3_P-PadB19)") (class "Default")
      (node (ref "SOCKET1") (pin "B19") (pinfunction "L3_P_B19") (pintype "bidirectional"))
    )
    (net (code "227") (name "unconnected-(SOCKET1-L4_N-PadA22)") (class "Default")
      (node (ref "SOCKET1") (pin "A22") (pinfunction "L4_N_A22") (pintype "bidirectional"))
    )
    (net (code "228") (name "unconnected-(SOCKET1-L4_P-PadA21)") (class "Default")
      (node (ref "SOCKET1") (pin "A21") (pinfunction "L4_P_A21") (pintype "bidirectional"))
    )
    (net (code "229") (name "unconnected-(SOCKET1-L6_N-PadA26)") (class "Default")
      (node (ref "SOCKET1") (pin "A26") (pinfunction "L6_N_A26") (pintype "bidirectional"))
    )
    (net (code "230") (name "unconnected-(SOCKET1-L6_P-PadA25)") (class "Default")
      (node (ref "SOCKET1") (pin "A25") (pinfunction "L6_P_A25") (pintype "bidirectional"))
    )
    (net (code "231") (name "unconnected-(SOCKET1-L8_N-PadA30)") (class "Default")
      (node (ref "SOCKET1") (pin "A30") (pinfunction "L8_N_A30") (pintype "bidirectional"))
    )
    (net (code "232") (name "unconnected-(SOCKET1-L8_P-PadA29)") (class "Default")
      (node (ref "SOCKET1") (pin "A29") (pinfunction "L8_P_A29") (pintype "bidirectional"))
    )
    (net (code "233") (name "unconnected-(SOCKET1-L9_N-PadB32)") (class "Default")
      (node (ref "SOCKET1") (pin "B32") (pinfunction "L9_N_B32") (pintype "bidirectional"))
    )
    (net (code "234") (name "unconnected-(SOCKET1-L9_P-PadB31)") (class "Default")
      (node (ref "SOCKET1") (pin "B31") (pinfunction "L9_P_B31") (pintype "bidirectional"))
    )
    (net (code "235") (name "unconnected-(SOCKET1-L10_N-PadA34)") (class "Default")
      (node (ref "SOCKET1") (pin "A34") (pinfunction "L10_N_A34") (pintype "bidirectional"))
    )
    (net (code "236") (name "unconnected-(SOCKET1-L10_P-PadA33)") (class "Default")
      (node (ref "SOCKET1") (pin "A33") (pinfunction "L10_P_A33") (pintype "bidirectional"))
    )
    (net (code "237") (name "unconnected-(SOCKET1-L11_N-PadB36)") (class "Default")
      (node (ref "SOCKET1") (pin "B36") (pinfunction "L11_N_B36") (pintype "bidirectional"))
    )
    (net (code "238") (name "unconnected-(SOCKET1-L11_P-PadB35)") (class "Default")
      (node (ref "SOCKET1") (pin "B35") (pinfunction "L11_P_B35") (pintype "bidirectional"))
    )
    (net (code "239") (name "unconnected-(SOCKET1-L12_N-PadA38)") (class "Default")
      (node (ref "SOCKET1") (pin "A38") (pinfunction "L12_N_A38") (pintype "bidirectional"))
    )
    (net (code "240") (name "unconnected-(SOCKET1-L12_P-PadA37)") (class "Default")
      (node (ref "SOCKET1") (pin "A37") (pinfunction "L12_P_A37") (pintype "bidirectional"))
    )
    (net (code "241") (name "unconnected-(SOCKET1-L13_N-PadA42)") (class "Default")
      (node (ref "SOCKET1") (pin "A42") (pinfunction "L13_N_A42") (pintype "bidirectional"))
    )
    (net (code "242") (name "unconnected-(SOCKET1-L13_P-PadA41)") (class "Default")
      (node (ref "SOCKET1") (pin "A41") (pinfunction "L13_P_A41") (pintype "bidirectional"))
    )
    (net (code "243") (name "unconnected-(SOCKET1-L14_N-PadA46)") (class "Default")
      (node (ref "SOCKET1") (pin "A46") (pinfunction "L14_N_A46") (pintype "bidirectional"))
    )
    (net (code "244") (name "unconnected-(SOCKET1-L14_P-PadA45)") (class "Default")
      (node (ref "SOCKET1") (pin "A45") (pinfunction "L14_P_A45") (pintype "bidirectional"))
    )
    (net (code "245") (name "unconnected-(SOCKET1-PCIE_RESET#-PadA11)") (class "Default")
      (node (ref "SOCKET1") (pin "A11") (pinfunction "PCIE_RESET#_A11") (pintype "bidirectional"))
    )
    (net (code "246") (name "unconnected-(SOCKET1-RFU-PadA49)") (class "Default")
      (node (ref "SOCKET1") (pin "A49") (pinfunction "RFU_A49") (pintype "no_connect"))
    )
    (net (code "247") (name "unconnected-(SOCKET1-RFU-PadB39)") (class "Default")
      (node (ref "SOCKET1") (pin "B39") (pinfunction "RFU_B39") (pintype "no_connect"))
    )
    (net (code "248") (name "unconnected-(SOCKET1-RFU-PadB40)") (class "Default")
      (node (ref "SOCKET1") (pin "B40") (pinfunction "RFU_B40") (pintype "no_connect"))
    )
    (net (code "249") (name "unconnected-(SOCKET1-SVR_ID0-PadA5)") (class "Default")
      (node (ref "SOCKET1") (pin "A5") (pinfunction "SVR_ID0_A5") (pintype "bidirectional"))
    )
    (net (code "250") (name "unconnected-(SOCKET1-SVR_ID1-PadA6)") (class "Default")
      (node (ref "SOCKET1") (pin "A6") (pinfunction "SVR_ID1_A6") (pintype "bidirectional"))
    )
    (net (code "251") (name "unconnected-(SOCKET1-SVR_ID2-PadA9)") (class "Default")
      (node (ref "SOCKET1") (pin "A9") (pinfunction "SVR_ID2_A9") (pintype "bidirectional"))
    )
    (net (code "252") (name "unconnected-(SOCKET1-SVR_ID3-PadA10)") (class "Default")
      (node (ref "SOCKET1") (pin "A10") (pinfunction "SVR_ID3_A10") (pintype "bidirectional"))
    )
    (net (code "253") (name "unconnected-(SOCKET2-GND{slash}SVR_ID4-PadA12)") (class "Default")
      (node (ref "SOCKET2") (pin "A12") (pinfunction "GND/SVR_ID4_A12") (pintype "bidirectional"))
    )
    (net (code "254") (name "unconnected-(SOCKET2-I2C_ALERT#-PadB12)") (class "Default")
      (node (ref "SOCKET2") (pin "B12") (pinfunction "I2C_ALERT#_B12") (pintype "bidirectional"))
    )
    (net (code "255") (name "unconnected-(SOCKET2-L0_N-PadA14)") (class "Default")
      (node (ref "SOCKET2") (pin "A14") (pinfunction "L0_N_A14") (pintype "bidirectional"))
    )
    (net (code "256") (name "unconnected-(SOCKET2-L1_N-PadB16)") (class "Default")
      (node (ref "SOCKET2") (pin "B16") (pinfunction "L1_N_B16") (pintype "bidirectional"))
    )
    (net (code "257") (name "unconnected-(SOCKET2-L1_P-PadB15)") (class "Default")
      (node (ref "SOCKET2") (pin "B15") (pinfunction "L1_P_B15") (pintype "bidirectional"))
    )
    (net (code "258") (name "unconnected-(SOCKET2-L2_N-PadA18)") (class "Default")
      (node (ref "SOCKET2") (pin "A18") (pinfunction "L2_N_A18") (pintype "bidirectional"))
    )
    (net (code "259") (name "unconnected-(SOCKET2-L2_P-PadA17)") (class "Default")
      (node (ref "SOCKET2") (pin "A17") (pinfunction "L2_P_A17") (pintype "bidirectional"))
    )
    (net (code "260") (name "unconnected-(SOCKET2-L3_N-PadB20)") (class "Default")
      (node (ref "SOCKET2") (pin "B20") (pinfunction "L3_N_B20") (pintype "bidirectional"))
    )
    (net (code "261") (name "unconnected-(SOCKET2-L3_P-PadB19)") (class "Default")
      (node (ref "SOCKET2") (pin "B19") (pinfunction "L3_P_B19") (pintype "bidirectional"))
    )
    (net (code "262") (name "unconnected-(SOCKET2-L4_N-PadA22)") (class "Default")
      (node (ref "SOCKET2") (pin "A22") (pinfunction "L4_N_A22") (pintype "bidirectional"))
    )
    (net (code "263") (name "unconnected-(SOCKET2-L4_P-PadA21)") (class "Default")
      (node (ref "SOCKET2") (pin "A21") (pinfunction "L4_P_A21") (pintype "bidirectional"))
    )
    (net (code "264") (name "unconnected-(SOCKET2-L6_N-PadA26)") (class "Default")
      (node (ref "SOCKET2") (pin "A26") (pinfunction "L6_N_A26") (pintype "bidirectional"))
    )
    (net (code "265") (name "unconnected-(SOCKET2-L6_P-PadA25)") (class "Default")
      (node (ref "SOCKET2") (pin "A25") (pinfunction "L6_P_A25") (pintype "bidirectional"))
    )
    (net (code "266") (name "unconnected-(SOCKET2-L8_N-PadA30)") (class "Default")
      (node (ref "SOCKET2") (pin "A30") (pinfunction "L8_N_A30") (pintype "bidirectional"))
    )
    (net (code "267") (name "unconnected-(SOCKET2-L8_P-PadA29)") (class "Default")
      (node (ref "SOCKET2") (pin "A29") (pinfunction "L8_P_A29") (pintype "bidirectional"))
    )
    (net (code "268") (name "unconnected-(SOCKET2-L9_N-PadB32)") (class "Default")
      (node (ref "SOCKET2") (pin "B32") (pinfunction "L9_N_B32") (pintype "bidirectional"))
    )
    (net (code "269") (name "unconnected-(SOCKET2-L9_P-PadB31)") (class "Default")
      (node (ref "SOCKET2") (pin "B31") (pinfunction "L9_P_B31") (pintype "bidirectional"))
    )
    (net (code "270") (name "unconnected-(SOCKET2-L10_N-PadA34)") (class "Default")
      (node (ref "SOCKET2") (pin "A34") (pinfunction "L10_N_A34") (pintype "bidirectional"))
    )
    (net (code "271") (name "unconnected-(SOCKET2-L10_P-PadA33)") (class "Default")
      (node (ref "SOCKET2") (pin "A33") (pinfunction "L10_P_A33") (pintype "bidirectional"))
    )
    (net (code "272") (name "unconnected-(SOCKET2-L11_N-PadB36)") (class "Default")
      (node (ref "SOCKET2") (pin "B36") (pinfunction "L11_N_B36") (pintype "bidirectional"))
    )
    (net (code "273") (name "unconnected-(SOCKET2-L11_P-PadB35)") (class "Default")
      (node (ref "SOCKET2") (pin "B35") (pinfunction "L11_P_B35") (pintype "bidirectional"))
    )
    (net (code "274") (name "unconnected-(SOCKET2-L12_N-PadA38)") (class "Default")
      (node (ref "SOCKET2") (pin "A38") (pinfunction "L12_N_A38") (pintype "bidirectional"))
    )
    (net (code "275") (name "unconnected-(SOCKET2-L12_P-PadA37)") (class "Default")
      (node (ref "SOCKET2") (pin "A37") (pinfunction "L12_P_A37") (pintype "bidirectional"))
    )
    (net (code "276") (name "unconnected-(SOCKET2-L13_N-PadA42)") (class "Default")
      (node (ref "SOCKET2") (pin "A42") (pinfunction "L13_N_A42") (pintype "bidirectional"))
    )
    (net (code "277") (name "unconnected-(SOCKET2-L13_P-PadA41)") (class "Default")
      (node (ref "SOCKET2") (pin "A41") (pinfunction "L13_P_A41") (pintype "bidirectional"))
    )
    (net (code "278") (name "unconnected-(SOCKET2-L14_N-PadA46)") (class "Default")
      (node (ref "SOCKET2") (pin "A46") (pinfunction "L14_N_A46") (pintype "bidirectional"))
    )
    (net (code "279") (name "unconnected-(SOCKET2-L14_P-PadA45)") (class "Default")
      (node (ref "SOCKET2") (pin "A45") (pinfunction "L14_P_A45") (pintype "bidirectional"))
    )
    (net (code "280") (name "unconnected-(SOCKET2-PCIE_RESET#-PadA11)") (class "Default")
      (node (ref "SOCKET2") (pin "A11") (pinfunction "PCIE_RESET#_A11") (pintype "bidirectional"))
    )
    (net (code "281") (name "unconnected-(SOCKET2-RFU-PadA49)") (class "Default")
      (node (ref "SOCKET2") (pin "A49") (pinfunction "RFU_A49") (pintype "no_connect"))
    )
    (net (code "282") (name "unconnected-(SOCKET2-RFU-PadB39)") (class "Default")
      (node (ref "SOCKET2") (pin "B39") (pinfunction "RFU_B39") (pintype "no_connect"))
    )
    (net (code "283") (name "unconnected-(SOCKET2-RFU-PadB40)") (class "Default")
      (node (ref "SOCKET2") (pin "B40") (pinfunction "RFU_B40") (pintype "no_connect"))
    )
    (net (code "284") (name "unconnected-(SOCKET2-SVR_ID1-PadA6)") (class "Default")
      (node (ref "SOCKET2") (pin "A6") (pinfunction "SVR_ID1_A6") (pintype "bidirectional"))
    )
    (net (code "285") (name "unconnected-(SOCKET2-SVR_ID2-PadA9)") (class "Default")
      (node (ref "SOCKET2") (pin "A9") (pinfunction "SVR_ID2_A9") (pintype "bidirectional"))
    )
    (net (code "286") (name "unconnected-(SOCKET2-SVR_ID3-PadA10)") (class "Default")
      (node (ref "SOCKET2") (pin "A10") (pinfunction "SVR_ID3_A10") (pintype "bidirectional"))
    )
    (net (code "287") (name "unconnected-(SOCKET2-USB_N-PadB10)") (class "Default")
      (node (ref "SOCKET2") (pin "B10") (pinfunction "USB_N_B10") (pintype "bidirectional"))
    )
    (net (code "288") (name "unconnected-(SOCKET2-USB_P-PadB9)") (class "Default")
      (node (ref "SOCKET2") (pin "B9") (pinfunction "USB_P_B9") (pintype "bidirectional"))
    )
    (net (code "289") (name "unconnected-(SOCKET3-GND{slash}SVR_ID4-PadA12)") (class "Default")
      (node (ref "SOCKET3") (pin "A12") (pinfunction "GND/SVR_ID4_A12") (pintype "bidirectional"))
    )
    (net (code "290") (name "unconnected-(SOCKET3-I2C_ALERT#-PadB12)") (class "Default")
      (node (ref "SOCKET3") (pin "B12") (pinfunction "I2C_ALERT#_B12") (pintype "bidirectional"))
    )
    (net (code "291") (name "unconnected-(SOCKET3-L0_N-PadA14)") (class "Default")
      (node (ref "SOCKET3") (pin "A14") (pinfunction "L0_N_A14") (pintype "bidirectional"))
    )
    (net (code "292") (name "unconnected-(SOCKET3-L1_N-PadB16)") (class "Default")
      (node (ref "SOCKET3") (pin "B16") (pinfunction "L1_N_B16") (pintype "bidirectional"))
    )
    (net (code "293") (name "unconnected-(SOCKET3-L1_P-PadB15)") (class "Default")
      (node (ref "SOCKET3") (pin "B15") (pinfunction "L1_P_B15") (pintype "bidirectional"))
    )
    (net (code "294") (name "unconnected-(SOCKET3-L2_N-PadA18)") (class "Default")
      (node (ref "SOCKET3") (pin "A18") (pinfunction "L2_N_A18") (pintype "bidirectional"))
    )
    (net (code "295") (name "unconnected-(SOCKET3-L2_P-PadA17)") (class "Default")
      (node (ref "SOCKET3") (pin "A17") (pinfunction "L2_P_A17") (pintype "bidirectional"))
    )
    (net (code "296") (name "unconnected-(SOCKET3-L3_N-PadB20)") (class "Default")
      (node (ref "SOCKET3") (pin "B20") (pinfunction "L3_N_B20") (pintype "bidirectional"))
    )
    (net (code "297") (name "unconnected-(SOCKET3-L3_P-PadB19)") (class "Default")
      (node (ref "SOCKET3") (pin "B19") (pinfunction "L3_P_B19") (pintype "bidirectional"))
    )
    (net (code "298") (name "unconnected-(SOCKET3-L4_N-PadA22)") (class "Default")
      (node (ref "SOCKET3") (pin "A22") (pinfunction "L4_N_A22") (pintype "bidirectional"))
    )
    (net (code "299") (name "unconnected-(SOCKET3-L4_P-PadA21)") (class "Default")
      (node (ref "SOCKET3") (pin "A21") (pinfunction "L4_P_A21") (pintype "bidirectional"))
    )
    (net (code "300") (name "unconnected-(SOCKET3-L6_N-PadA26)") (class "Default")
      (node (ref "SOCKET3") (pin "A26") (pinfunction "L6_N_A26") (pintype "bidirectional"))
    )
    (net (code "301") (name "unconnected-(SOCKET3-L6_P-PadA25)") (class "Default")
      (node (ref "SOCKET3") (pin "A25") (pinfunction "L6_P_A25") (pintype "bidirectional"))
    )
    (net (code "302") (name "unconnected-(SOCKET3-L8_N-PadA30)") (class "Default")
      (node (ref "SOCKET3") (pin "A30") (pinfunction "L8_N_A30") (pintype "bidirectional"))
    )
    (net (code "303") (name "unconnected-(SOCKET3-L8_P-PadA29)") (class "Default")
      (node (ref "SOCKET3") (pin "A29") (pinfunction "L8_P_A29") (pintype "bidirectional"))
    )
    (net (code "304") (name "unconnected-(SOCKET3-L9_N-PadB32)") (class "Default")
      (node (ref "SOCKET3") (pin "B32") (pinfunction "L9_N_B32") (pintype "bidirectional"))
    )
    (net (code "305") (name "unconnected-(SOCKET3-L9_P-PadB31)") (class "Default")
      (node (ref "SOCKET3") (pin "B31") (pinfunction "L9_P_B31") (pintype "bidirectional"))
    )
    (net (code "306") (name "unconnected-(SOCKET3-L10_N-PadA34)") (class "Default")
      (node (ref "SOCKET3") (pin "A34") (pinfunction "L10_N_A34") (pintype "bidirectional"))
    )
    (net (code "307") (name "unconnected-(SOCKET3-L10_P-PadA33)") (class "Default")
      (node (ref "SOCKET3") (pin "A33") (pinfunction "L10_P_A33") (pintype "bidirectional"))
    )
    (net (code "308") (name "unconnected-(SOCKET3-L11_N-PadB36)") (class "Default")
      (node (ref "SOCKET3") (pin "B36") (pinfunction "L11_N_B36") (pintype "bidirectional"))
    )
    (net (code "309") (name "unconnected-(SOCKET3-L11_P-PadB35)") (class "Default")
      (node (ref "SOCKET3") (pin "B35") (pinfunction "L11_P_B35") (pintype "bidirectional"))
    )
    (net (code "310") (name "unconnected-(SOCKET3-L12_N-PadA38)") (class "Default")
      (node (ref "SOCKET3") (pin "A38") (pinfunction "L12_N_A38") (pintype "bidirectional"))
    )
    (net (code "311") (name "unconnected-(SOCKET3-L12_P-PadA37)") (class "Default")
      (node (ref "SOCKET3") (pin "A37") (pinfunction "L12_P_A37") (pintype "bidirectional"))
    )
    (net (code "312") (name "unconnected-(SOCKET3-L13_N-PadA42)") (class "Default")
      (node (ref "SOCKET3") (pin "A42") (pinfunction "L13_N_A42") (pintype "bidirectional"))
    )
    (net (code "313") (name "unconnected-(SOCKET3-L13_P-PadA41)") (class "Default")
      (node (ref "SOCKET3") (pin "A41") (pinfunction "L13_P_A41") (pintype "bidirectional"))
    )
    (net (code "314") (name "unconnected-(SOCKET3-L14_N-PadA46)") (class "Default")
      (node (ref "SOCKET3") (pin "A46") (pinfunction "L14_N_A46") (pintype "bidirectional"))
    )
    (net (code "315") (name "unconnected-(SOCKET3-L14_P-PadA45)") (class "Default")
      (node (ref "SOCKET3") (pin "A45") (pinfunction "L14_P_A45") (pintype "bidirectional"))
    )
    (net (code "316") (name "unconnected-(SOCKET3-PCIE_RESET#-PadA11)") (class "Default")
      (node (ref "SOCKET3") (pin "A11") (pinfunction "PCIE_RESET#_A11") (pintype "bidirectional"))
    )
    (net (code "317") (name "unconnected-(SOCKET3-RFU-PadA49)") (class "Default")
      (node (ref "SOCKET3") (pin "A49") (pinfunction "RFU_A49") (pintype "no_connect"))
    )
    (net (code "318") (name "unconnected-(SOCKET3-RFU-PadB39)") (class "Default")
      (node (ref "SOCKET3") (pin "B39") (pinfunction "RFU_B39") (pintype "no_connect"))
    )
    (net (code "319") (name "unconnected-(SOCKET3-RFU-PadB40)") (class "Default")
      (node (ref "SOCKET3") (pin "B40") (pinfunction "RFU_B40") (pintype "no_connect"))
    )
    (net (code "320") (name "unconnected-(SOCKET3-SVR_ID0-PadA5)") (class "Default")
      (node (ref "SOCKET3") (pin "A5") (pinfunction "SVR_ID0_A5") (pintype "bidirectional"))
    )
    (net (code "321") (name "unconnected-(SOCKET3-SVR_ID2-PadA9)") (class "Default")
      (node (ref "SOCKET3") (pin "A9") (pinfunction "SVR_ID2_A9") (pintype "bidirectional"))
    )
    (net (code "322") (name "unconnected-(SOCKET3-SVR_ID3-PadA10)") (class "Default")
      (node (ref "SOCKET3") (pin "A10") (pinfunction "SVR_ID3_A10") (pintype "bidirectional"))
    )
    (net (code "323") (name "unconnected-(SOCKET3-USB_N-PadB10)") (class "Default")
      (node (ref "SOCKET3") (pin "B10") (pinfunction "USB_N_B10") (pintype "bidirectional"))
    )
    (net (code "324") (name "unconnected-(SOCKET3-USB_P-PadB9)") (class "Default")
      (node (ref "SOCKET3") (pin "B9") (pinfunction "USB_P_B9") (pintype "bidirectional"))
    )
    (net (code "325") (name "unconnected-(SOCKET4-GND{slash}SVR_ID4-PadA12)") (class "Default")
      (node (ref "SOCKET4") (pin "A12") (pinfunction "GND/SVR_ID4_A12") (pintype "bidirectional"))
    )
    (net (code "326") (name "unconnected-(SOCKET4-I2C_ALERT#-PadB12)") (class "Default")
      (node (ref "SOCKET4") (pin "B12") (pinfunction "I2C_ALERT#_B12") (pintype "bidirectional"))
    )
    (net (code "327") (name "unconnected-(SOCKET4-L0_N-PadA14)") (class "Default")
      (node (ref "SOCKET4") (pin "A14") (pinfunction "L0_N_A14") (pintype "bidirectional"))
    )
    (net (code "328") (name "unconnected-(SOCKET4-L1_N-PadB16)") (class "Default")
      (node (ref "SOCKET4") (pin "B16") (pinfunction "L1_N_B16") (pintype "bidirectional"))
    )
    (net (code "329") (name "unconnected-(SOCKET4-L1_P-PadB15)") (class "Default")
      (node (ref "SOCKET4") (pin "B15") (pinfunction "L1_P_B15") (pintype "bidirectional"))
    )
    (net (code "330") (name "unconnected-(SOCKET4-L2_N-PadA18)") (class "Default")
      (node (ref "SOCKET4") (pin "A18") (pinfunction "L2_N_A18") (pintype "bidirectional"))
    )
    (net (code "331") (name "unconnected-(SOCKET4-L2_P-PadA17)") (class "Default")
      (node (ref "SOCKET4") (pin "A17") (pinfunction "L2_P_A17") (pintype "bidirectional"))
    )
    (net (code "332") (name "unconnected-(SOCKET4-L3_N-PadB20)") (class "Default")
      (node (ref "SOCKET4") (pin "B20") (pinfunction "L3_N_B20") (pintype "bidirectional"))
    )
    (net (code "333") (name "unconnected-(SOCKET4-L3_P-PadB19)") (class "Default")
      (node (ref "SOCKET4") (pin "B19") (pinfunction "L3_P_B19") (pintype "bidirectional"))
    )
    (net (code "334") (name "unconnected-(SOCKET4-L4_N-PadA22)") (class "Default")
      (node (ref "SOCKET4") (pin "A22") (pinfunction "L4_N_A22") (pintype "bidirectional"))
    )
    (net (code "335") (name "unconnected-(SOCKET4-L4_P-PadA21)") (class "Default")
      (node (ref "SOCKET4") (pin "A21") (pinfunction "L4_P_A21") (pintype "bidirectional"))
    )
    (net (code "336") (name "unconnected-(SOCKET4-L6_N-PadA26)") (class "Default")
      (node (ref "SOCKET4") (pin "A26") (pinfunction "L6_N_A26") (pintype "bidirectional"))
    )
    (net (code "337") (name "unconnected-(SOCKET4-L6_P-PadA25)") (class "Default")
      (node (ref "SOCKET4") (pin "A25") (pinfunction "L6_P_A25") (pintype "bidirectional"))
    )
    (net (code "338") (name "unconnected-(SOCKET4-L8_N-PadA30)") (class "Default")
      (node (ref "SOCKET4") (pin "A30") (pinfunction "L8_N_A30") (pintype "bidirectional"))
    )
    (net (code "339") (name "unconnected-(SOCKET4-L8_P-PadA29)") (class "Default")
      (node (ref "SOCKET4") (pin "A29") (pinfunction "L8_P_A29") (pintype "bidirectional"))
    )
    (net (code "340") (name "unconnected-(SOCKET4-L9_N-PadB32)") (class "Default")
      (node (ref "SOCKET4") (pin "B32") (pinfunction "L9_N_B32") (pintype "bidirectional"))
    )
    (net (code "341") (name "unconnected-(SOCKET4-L9_P-PadB31)") (class "Default")
      (node (ref "SOCKET4") (pin "B31") (pinfunction "L9_P_B31") (pintype "bidirectional"))
    )
    (net (code "342") (name "unconnected-(SOCKET4-L10_N-PadA34)") (class "Default")
      (node (ref "SOCKET4") (pin "A34") (pinfunction "L10_N_A34") (pintype "bidirectional"))
    )
    (net (code "343") (name "unconnected-(SOCKET4-L10_P-PadA33)") (class "Default")
      (node (ref "SOCKET4") (pin "A33") (pinfunction "L10_P_A33") (pintype "bidirectional"))
    )
    (net (code "344") (name "unconnected-(SOCKET4-L11_N-PadB36)") (class "Default")
      (node (ref "SOCKET4") (pin "B36") (pinfunction "L11_N_B36") (pintype "bidirectional"))
    )
    (net (code "345") (name "unconnected-(SOCKET4-L11_P-PadB35)") (class "Default")
      (node (ref "SOCKET4") (pin "B35") (pinfunction "L11_P_B35") (pintype "bidirectional"))
    )
    (net (code "346") (name "unconnected-(SOCKET4-L12_N-PadA38)") (class "Default")
      (node (ref "SOCKET4") (pin "A38") (pinfunction "L12_N_A38") (pintype "bidirectional"))
    )
    (net (code "347") (name "unconnected-(SOCKET4-L12_P-PadA37)") (class "Default")
      (node (ref "SOCKET4") (pin "A37") (pinfunction "L12_P_A37") (pintype "bidirectional"))
    )
    (net (code "348") (name "unconnected-(SOCKET4-L13_N-PadA42)") (class "Default")
      (node (ref "SOCKET4") (pin "A42") (pinfunction "L13_N_A42") (pintype "bidirectional"))
    )
    (net (code "349") (name "unconnected-(SOCKET4-L13_P-PadA41)") (class "Default")
      (node (ref "SOCKET4") (pin "A41") (pinfunction "L13_P_A41") (pintype "bidirectional"))
    )
    (net (code "350") (name "unconnected-(SOCKET4-L14_N-PadA46)") (class "Default")
      (node (ref "SOCKET4") (pin "A46") (pinfunction "L14_N_A46") (pintype "bidirectional"))
    )
    (net (code "351") (name "unconnected-(SOCKET4-L14_P-PadA45)") (class "Default")
      (node (ref "SOCKET4") (pin "A45") (pinfunction "L14_P_A45") (pintype "bidirectional"))
    )
    (net (code "352") (name "unconnected-(SOCKET4-PCIE_RESET#-PadA11)") (class "Default")
      (node (ref "SOCKET4") (pin "A11") (pinfunction "PCIE_RESET#_A11") (pintype "bidirectional"))
    )
    (net (code "353") (name "unconnected-(SOCKET4-RFU-PadA49)") (class "Default")
      (node (ref "SOCKET4") (pin "A49") (pinfunction "RFU_A49") (pintype "no_connect"))
    )
    (net (code "354") (name "unconnected-(SOCKET4-RFU-PadB39)") (class "Default")
      (node (ref "SOCKET4") (pin "B39") (pinfunction "RFU_B39") (pintype "no_connect"))
    )
    (net (code "355") (name "unconnected-(SOCKET4-RFU-PadB40)") (class "Default")
      (node (ref "SOCKET4") (pin "B40") (pinfunction "RFU_B40") (pintype "no_connect"))
    )
    (net (code "356") (name "unconnected-(SOCKET4-SVR_ID2-PadA9)") (class "Default")
      (node (ref "SOCKET4") (pin "A9") (pinfunction "SVR_ID2_A9") (pintype "bidirectional"))
    )
    (net (code "357") (name "unconnected-(SOCKET4-SVR_ID3-PadA10)") (class "Default")
      (node (ref "SOCKET4") (pin "A10") (pinfunction "SVR_ID3_A10") (pintype "bidirectional"))
    )
    (net (code "358") (name "unconnected-(SOCKET4-USB_N-PadB10)") (class "Default")
      (node (ref "SOCKET4") (pin "B10") (pinfunction "USB_N_B10") (pintype "bidirectional"))
    )
    (net (code "359") (name "unconnected-(SOCKET4-USB_P-PadB9)") (class "Default")
      (node (ref "SOCKET4") (pin "B9") (pinfunction "USB_P_B9") (pintype "bidirectional"))
    )
    (net (code "360") (name "unconnected-(SOCKET5-GND{slash}SVR_ID4-PadA12)") (class "Default")
      (node (ref "SOCKET5") (pin "A12") (pinfunction "GND/SVR_ID4_A12") (pintype "bidirectional"))
    )
    (net (code "361") (name "unconnected-(SOCKET5-I2C_ALERT#-PadB12)") (class "Default")
      (node (ref "SOCKET5") (pin "B12") (pinfunction "I2C_ALERT#_B12") (pintype "bidirectional"))
    )
    (net (code "362") (name "unconnected-(SOCKET5-L0_N-PadA14)") (class "Default")
      (node (ref "SOCKET5") (pin "A14") (pinfunction "L0_N_A14") (pintype "bidirectional"))
    )
    (net (code "363") (name "unconnected-(SOCKET5-L1_N-PadB16)") (class "Default")
      (node (ref "SOCKET5") (pin "B16") (pinfunction "L1_N_B16") (pintype "bidirectional"))
    )
    (net (code "364") (name "unconnected-(SOCKET5-L1_P-PadB15)") (class "Default")
      (node (ref "SOCKET5") (pin "B15") (pinfunction "L1_P_B15") (pintype "bidirectional"))
    )
    (net (code "365") (name "unconnected-(SOCKET5-L2_N-PadA18)") (class "Default")
      (node (ref "SOCKET5") (pin "A18") (pinfunction "L2_N_A18") (pintype "bidirectional"))
    )
    (net (code "366") (name "unconnected-(SOCKET5-L2_P-PadA17)") (class "Default")
      (node (ref "SOCKET5") (pin "A17") (pinfunction "L2_P_A17") (pintype "bidirectional"))
    )
    (net (code "367") (name "unconnected-(SOCKET5-L3_N-PadB20)") (class "Default")
      (node (ref "SOCKET5") (pin "B20") (pinfunction "L3_N_B20") (pintype "bidirectional"))
    )
    (net (code "368") (name "unconnected-(SOCKET5-L3_P-PadB19)") (class "Default")
      (node (ref "SOCKET5") (pin "B19") (pinfunction "L3_P_B19") (pintype "bidirectional"))
    )
    (net (code "369") (name "unconnected-(SOCKET5-L4_N-PadA22)") (class "Default")
      (node (ref "SOCKET5") (pin "A22") (pinfunction "L4_N_A22") (pintype "bidirectional"))
    )
    (net (code "370") (name "unconnected-(SOCKET5-L4_P-PadA21)") (class "Default")
      (node (ref "SOCKET5") (pin "A21") (pinfunction "L4_P_A21") (pintype "bidirectional"))
    )
    (net (code "371") (name "unconnected-(SOCKET5-L6_N-PadA26)") (class "Default")
      (node (ref "SOCKET5") (pin "A26") (pinfunction "L6_N_A26") (pintype "bidirectional"))
    )
    (net (code "372") (name "unconnected-(SOCKET5-L6_P-PadA25)") (class "Default")
      (node (ref "SOCKET5") (pin "A25") (pinfunction "L6_P_A25") (pintype "bidirectional"))
    )
    (net (code "373") (name "unconnected-(SOCKET5-L8_N-PadA30)") (class "Default")
      (node (ref "SOCKET5") (pin "A30") (pinfunction "L8_N_A30") (pintype "bidirectional"))
    )
    (net (code "374") (name "unconnected-(SOCKET5-L8_P-PadA29)") (class "Default")
      (node (ref "SOCKET5") (pin "A29") (pinfunction "L8_P_A29") (pintype "bidirectional"))
    )
    (net (code "375") (name "unconnected-(SOCKET5-L9_N-PadB32)") (class "Default")
      (node (ref "SOCKET5") (pin "B32") (pinfunction "L9_N_B32") (pintype "bidirectional"))
    )
    (net (code "376") (name "unconnected-(SOCKET5-L9_P-PadB31)") (class "Default")
      (node (ref "SOCKET5") (pin "B31") (pinfunction "L9_P_B31") (pintype "bidirectional"))
    )
    (net (code "377") (name "unconnected-(SOCKET5-L10_N-PadA34)") (class "Default")
      (node (ref "SOCKET5") (pin "A34") (pinfunction "L10_N_A34") (pintype "bidirectional"))
    )
    (net (code "378") (name "unconnected-(SOCKET5-L10_P-PadA33)") (class "Default")
      (node (ref "SOCKET5") (pin "A33") (pinfunction "L10_P_A33") (pintype "bidirectional"))
    )
    (net (code "379") (name "unconnected-(SOCKET5-L11_N-PadB36)") (class "Default")
      (node (ref "SOCKET5") (pin "B36") (pinfunction "L11_N_B36") (pintype "bidirectional"))
    )
    (net (code "380") (name "unconnected-(SOCKET5-L11_P-PadB35)") (class "Default")
      (node (ref "SOCKET5") (pin "B35") (pinfunction "L11_P_B35") (pintype "bidirectional"))
    )
    (net (code "381") (name "unconnected-(SOCKET5-L12_N-PadA38)") (class "Default")
      (node (ref "SOCKET5") (pin "A38") (pinfunction "L12_N_A38") (pintype "bidirectional"))
    )
    (net (code "382") (name "unconnected-(SOCKET5-L12_P-PadA37)") (class "Default")
      (node (ref "SOCKET5") (pin "A37") (pinfunction "L12_P_A37") (pintype "bidirectional"))
    )
    (net (code "383") (name "unconnected-(SOCKET5-L13_N-PadA42)") (class "Default")
      (node (ref "SOCKET5") (pin "A42") (pinfunction "L13_N_A42") (pintype "bidirectional"))
    )
    (net (code "384") (name "unconnected-(SOCKET5-L13_P-PadA41)") (class "Default")
      (node (ref "SOCKET5") (pin "A41") (pinfunction "L13_P_A41") (pintype "bidirectional"))
    )
    (net (code "385") (name "unconnected-(SOCKET5-L14_N-PadA46)") (class "Default")
      (node (ref "SOCKET5") (pin "A46") (pinfunction "L14_N_A46") (pintype "bidirectional"))
    )
    (net (code "386") (name "unconnected-(SOCKET5-L14_P-PadA45)") (class "Default")
      (node (ref "SOCKET5") (pin "A45") (pinfunction "L14_P_A45") (pintype "bidirectional"))
    )
    (net (code "387") (name "unconnected-(SOCKET5-PCIE_RESET#-PadA11)") (class "Default")
      (node (ref "SOCKET5") (pin "A11") (pinfunction "PCIE_RESET#_A11") (pintype "bidirectional"))
    )
    (net (code "388") (name "unconnected-(SOCKET5-RFU-PadA49)") (class "Default")
      (node (ref "SOCKET5") (pin "A49") (pinfunction "RFU_A49") (pintype "no_connect"))
    )
    (net (code "389") (name "unconnected-(SOCKET5-RFU-PadB39)") (class "Default")
      (node (ref "SOCKET5") (pin "B39") (pinfunction "RFU_B39") (pintype "no_connect"))
    )
    (net (code "390") (name "unconnected-(SOCKET5-RFU-PadB40)") (class "Default")
      (node (ref "SOCKET5") (pin "B40") (pinfunction "RFU_B40") (pintype "no_connect"))
    )
    (net (code "391") (name "unconnected-(SOCKET5-SVR_ID0-PadA5)") (class "Default")
      (node (ref "SOCKET5") (pin "A5") (pinfunction "SVR_ID0_A5") (pintype "bidirectional"))
    )
    (net (code "392") (name "unconnected-(SOCKET5-SVR_ID1-PadA6)") (class "Default")
      (node (ref "SOCKET5") (pin "A6") (pinfunction "SVR_ID1_A6") (pintype "bidirectional"))
    )
    (net (code "393") (name "unconnected-(SOCKET5-SVR_ID3-PadA10)") (class "Default")
      (node (ref "SOCKET5") (pin "A10") (pinfunction "SVR_ID3_A10") (pintype "bidirectional"))
    )
    (net (code "394") (name "unconnected-(U$2-Pad3)") (class "Default")
      (node (ref "U$2") (pin "3") (pinfunction "3_3") (pintype "bidirectional"))
    )
    (net (code "395") (name "unconnected-(U$2-Pad4)") (class "Default")
      (node (ref "U$2") (pin "4") (pinfunction "4_4") (pintype "bidirectional"))
    )
    (net (code "396") (name "unconnected-(U$2-Pad8)") (class "Default")
      (node (ref "U$2") (pin "8") (pinfunction "8_8") (pintype "bidirectional"))
    )
    (net (code "397") (name "unconnected-(U$2-Pad9)") (class "Default")
      (node (ref "U$2") (pin "9") (pinfunction "9_9") (pintype "bidirectional"))
    )
    (net (code "398") (name "unconnected-(U$2-Pad10)") (class "Default")
      (node (ref "U$2") (pin "10") (pinfunction "10_10") (pintype "bidirectional"))
    )
    (net (code "399") (name "unconnected-(U$2-Pad11)") (class "Default")
      (node (ref "U$2") (pin "11") (pinfunction "11_11") (pintype "bidirectional"))
    )
    (net (code "400") (name "unconnected-(U$2-Pad13)") (class "Default")
      (node (ref "U$2") (pin "13") (pinfunction "13_13") (pintype "bidirectional"))
    )
    (net (code "401") (name "unconnected-(U$2-Pad14)") (class "Default")
      (node (ref "U$2") (pin "14") (pinfunction "14_14") (pintype "bidirectional"))
    )
    (net (code "402") (name "unconnected-(U$2-Pad16)") (class "Default")
      (node (ref "U$2") (pin "16") (pinfunction "16_16") (pintype "bidirectional"))
    )
    (net (code "403") (name "unconnected-(U$2-Pad17)") (class "Default")
      (node (ref "U$2") (pin "17") (pinfunction "17_17") (pintype "bidirectional"))
    )
    (net (code "404") (name "unconnected-(U$2-Pad18)") (class "Default")
      (node (ref "U$2") (pin "18") (pinfunction "18_18") (pintype "bidirectional"))
    )
    (net (code "405") (name "unconnected-(U$2-Pad20)") (class "Default")
      (node (ref "U$2") (pin "20") (pinfunction "20_20") (pintype "bidirectional"))
    )
    (net (code "406") (name "unconnected-(U$2-Pad21)") (class "Default")
      (node (ref "U$2") (pin "21") (pinfunction "21_21") (pintype "bidirectional"))
    )
    (net (code "407") (name "unconnected-(U$2-Pad23)") (class "Default")
      (node (ref "U$2") (pin "23") (pinfunction "23_23") (pintype "bidirectional"))
    )
    (net (code "408") (name "unconnected-(U$2-Pad24)") (class "Default")
      (node (ref "U$2") (pin "24") (pinfunction "24_24") (pintype "bidirectional"))
    )
    (net (code "409") (name "unconnected-(U$2-Pad25)") (class "Default")
      (node (ref "U$2") (pin "25") (pinfunction "25_25") (pintype "bidirectional"))
    )
    (net (code "410") (name "unconnected-(U$2-Pad27)") (class "Default")
      (node (ref "U$2") (pin "27") (pinfunction "27_27") (pintype "bidirectional"))
    )
    (net (code "411") (name "unconnected-(U$2-Pad28)") (class "Default")
      (node (ref "U$2") (pin "28") (pinfunction "28_28") (pintype "bidirectional"))
    )
    (net (code "412") (name "unconnected-(U$2-Pad30)") (class "Default")
      (node (ref "U$2") (pin "30") (pinfunction "30_30") (pintype "bidirectional"))
    )
    (net (code "413") (name "unconnected-(U$2-Pad37)") (class "Default")
      (node (ref "U$2") (pin "37") (pinfunction "37_37") (pintype "bidirectional"))
    )
    (net (code "414") (name "unconnected-(U$2-Pad38)") (class "Default")
      (node (ref "U$2") (pin "38") (pinfunction "38_38") (pintype "bidirectional"))
    )
    (net (code "415") (name "unconnected-(U$2-Pad39)") (class "Default")
      (node (ref "U$2") (pin "39") (pinfunction "39_39") (pintype "bidirectional"))
    )
    (net (code "416") (name "unconnected-(U$2-Pad40)") (class "Default")
      (node (ref "U$2") (pin "40") (pinfunction "40_40") (pintype "bidirectional"))
    )
    (net (code "417") (name "unconnected-(U$2-Pad41)") (class "Default")
      (node (ref "U$2") (pin "41") (pinfunction "41_41") (pintype "bidirectional"))
    )
    (net (code "418") (name "unconnected-(U$2-Pad42)") (class "Default")
      (node (ref "U$2") (pin "42") (pinfunction "42_42") (pintype "bidirectional"))
    )
    (net (code "419") (name "unconnected-(U$2-Pad43)") (class "Default")
      (node (ref "U$2") (pin "43") (pinfunction "43_43") (pintype "bidirectional"))
    )
    (net (code "420") (name "unconnected-(U$2-Pad44)") (class "Default")
      (node (ref "U$2") (pin "44") (pinfunction "44_44") (pintype "bidirectional"))
    )
    (net (code "421") (name "unconnected-(U$2-Pad51)") (class "Default")
      (node (ref "U$2") (pin "51") (pinfunction "51_51") (pintype "bidirectional"))
    )
    (net (code "422") (name "unconnected-(U$2-Pad58)") (class "Default")
      (node (ref "U$2") (pin "58") (pinfunction "58_58") (pintype "bidirectional"))
    )
    (net (code "423") (name "unconnected-(U$2-Pad65)") (class "Default")
      (node (ref "U$2") (pin "65") (pinfunction "65_65") (pintype "bidirectional"))
    )
    (net (code "424") (name "unconnected-(U$2-Pad72)") (class "Default")
      (node (ref "U$2") (pin "72") (pinfunction "72_72") (pintype "bidirectional"))
    )
    (net (code "425") (name "unconnected-(U$2-Pad77)") (class "Default")
      (node (ref "U$2") (pin "77") (pinfunction "77_77") (pintype "bidirectional"))
    )
    (net (code "426") (name "unconnected-(U$3-Pad3)") (class "Default")
      (node (ref "U$3") (pin "3") (pinfunction "3_3") (pintype "bidirectional"))
    )
    (net (code "427") (name "unconnected-(U$3-Pad13)") (class "Default")
      (node (ref "U$3") (pin "13") (pinfunction "13_13") (pintype "bidirectional"))
    )
    (net (code "428") (name "unconnected-(U$3-Pad23)") (class "Default")
      (node (ref "U$3") (pin "23") (pinfunction "23_23") (pintype "bidirectional"))
    )
    (net (code "429") (name "unconnected-(U$3-Pad33)") (class "Default")
      (node (ref "U$3") (pin "33") (pinfunction "33_33") (pintype "bidirectional"))
    )
    (net (code "430") (name "unconnected-(U$3-Pad35)") (class "Default")
      (node (ref "U$3") (pin "35") (pinfunction "35_35") (pintype "bidirectional"))
    )
    (net (code "431") (name "unconnected-(U$3-Pad36)") (class "Default")
      (node (ref "U$3") (pin "36") (pinfunction "36_36") (pintype "bidirectional"))
    )
    (net (code "432") (name "unconnected-(U$3-Pad38)") (class "Default")
      (node (ref "U$3") (pin "38") (pinfunction "38_38") (pintype "bidirectional"))
    )
    (net (code "433") (name "unconnected-(U$3-Pad39)") (class "Default")
      (node (ref "U$3") (pin "39") (pinfunction "39_39") (pintype "bidirectional"))
    )
    (net (code "434") (name "unconnected-(U$3-Pad41)") (class "Default")
      (node (ref "U$3") (pin "41") (pinfunction "41_41") (pintype "bidirectional"))
    )
    (net (code "435") (name "unconnected-(U$3-Pad42)") (class "Default")
      (node (ref "U$3") (pin "42") (pinfunction "42_42") (pintype "bidirectional"))
    )
    (net (code "436") (name "unconnected-(U$3-Pad43)") (class "Default")
      (node (ref "U$3") (pin "43") (pinfunction "43_43") (pintype "bidirectional"))
    )
    (net (code "437") (name "unconnected-(U$3-Pad44)") (class "Default")
      (node (ref "U$3") (pin "44") (pinfunction "44_44") (pintype "bidirectional"))
    )
    (net (code "438") (name "unconnected-(U$3-Pad45)") (class "Default")
      (node (ref "U$3") (pin "45") (pinfunction "45_45") (pintype "bidirectional"))
    )
    (net (code "439") (name "unconnected-(U$3-Pad46)") (class "Default")
      (node (ref "U$3") (pin "46") (pinfunction "46_46") (pintype "bidirectional"))
    )
    (net (code "440") (name "unconnected-(U$3-Pad47)") (class "Default")
      (node (ref "U$3") (pin "47") (pinfunction "47_47") (pintype "bidirectional"))
    )
    (net (code "441") (name "unconnected-(U$3-Pad48)") (class "Default")
      (node (ref "U$3") (pin "48") (pinfunction "48_48") (pintype "bidirectional"))
    )
    (net (code "442") (name "unconnected-(U$3-Pad49)") (class "Default")
      (node (ref "U$3") (pin "49") (pinfunction "49_49") (pintype "bidirectional"))
    )
    (net (code "443") (name "unconnected-(U$3-Pad50)") (class "Default")
      (node (ref "U$3") (pin "50") (pinfunction "50_50") (pintype "bidirectional"))
    )
    (net (code "444") (name "unconnected-(U$3-Pad52)") (class "Default")
      (node (ref "U$3") (pin "52") (pinfunction "52_52") (pintype "bidirectional"))
    )
    (net (code "445") (name "unconnected-(U$3-Pad53)") (class "Default")
      (node (ref "U$3") (pin "53") (pinfunction "53_53") (pintype "bidirectional"))
    )
    (net (code "446") (name "unconnected-(U$3-Pad55)") (class "Default")
      (node (ref "U$3") (pin "55") (pinfunction "55_55") (pintype "bidirectional"))
    )
    (net (code "447") (name "unconnected-(U$3-Pad56)") (class "Default")
      (node (ref "U$3") (pin "56") (pinfunction "56_56") (pintype "bidirectional"))
    )
    (net (code "448") (name "unconnected-(U$3-Pad58)") (class "Default")
      (node (ref "U$3") (pin "58") (pinfunction "58_58") (pintype "bidirectional"))
    )
    (net (code "449") (name "unconnected-(U$3-Pad68)") (class "Default")
      (node (ref "U$3") (pin "68") (pinfunction "68_68") (pintype "bidirectional"))
    )
    (net (code "450") (name "unconnected-(U$3-Pad78)") (class "Default")
      (node (ref "U$3") (pin "78") (pinfunction "78_78") (pintype "bidirectional"))
    )
    (net (code "451") (name "unconnected-(U$3-Pad88)") (class "Default")
      (node (ref "U$3") (pin "88") (pinfunction "88_88") (pintype "bidirectional"))
    )
    (net (code "452") (name "unconnected-(U$13--12V-Pad14)") (class "Default")
      (node (ref "U$13") (pin "14") (pinfunction "-12V_14") (pintype "bidirectional"))
    )
  )
)
